# BeagleBone_Black_egl.net
KiCad netlist of a schematic drawn in EAGLE
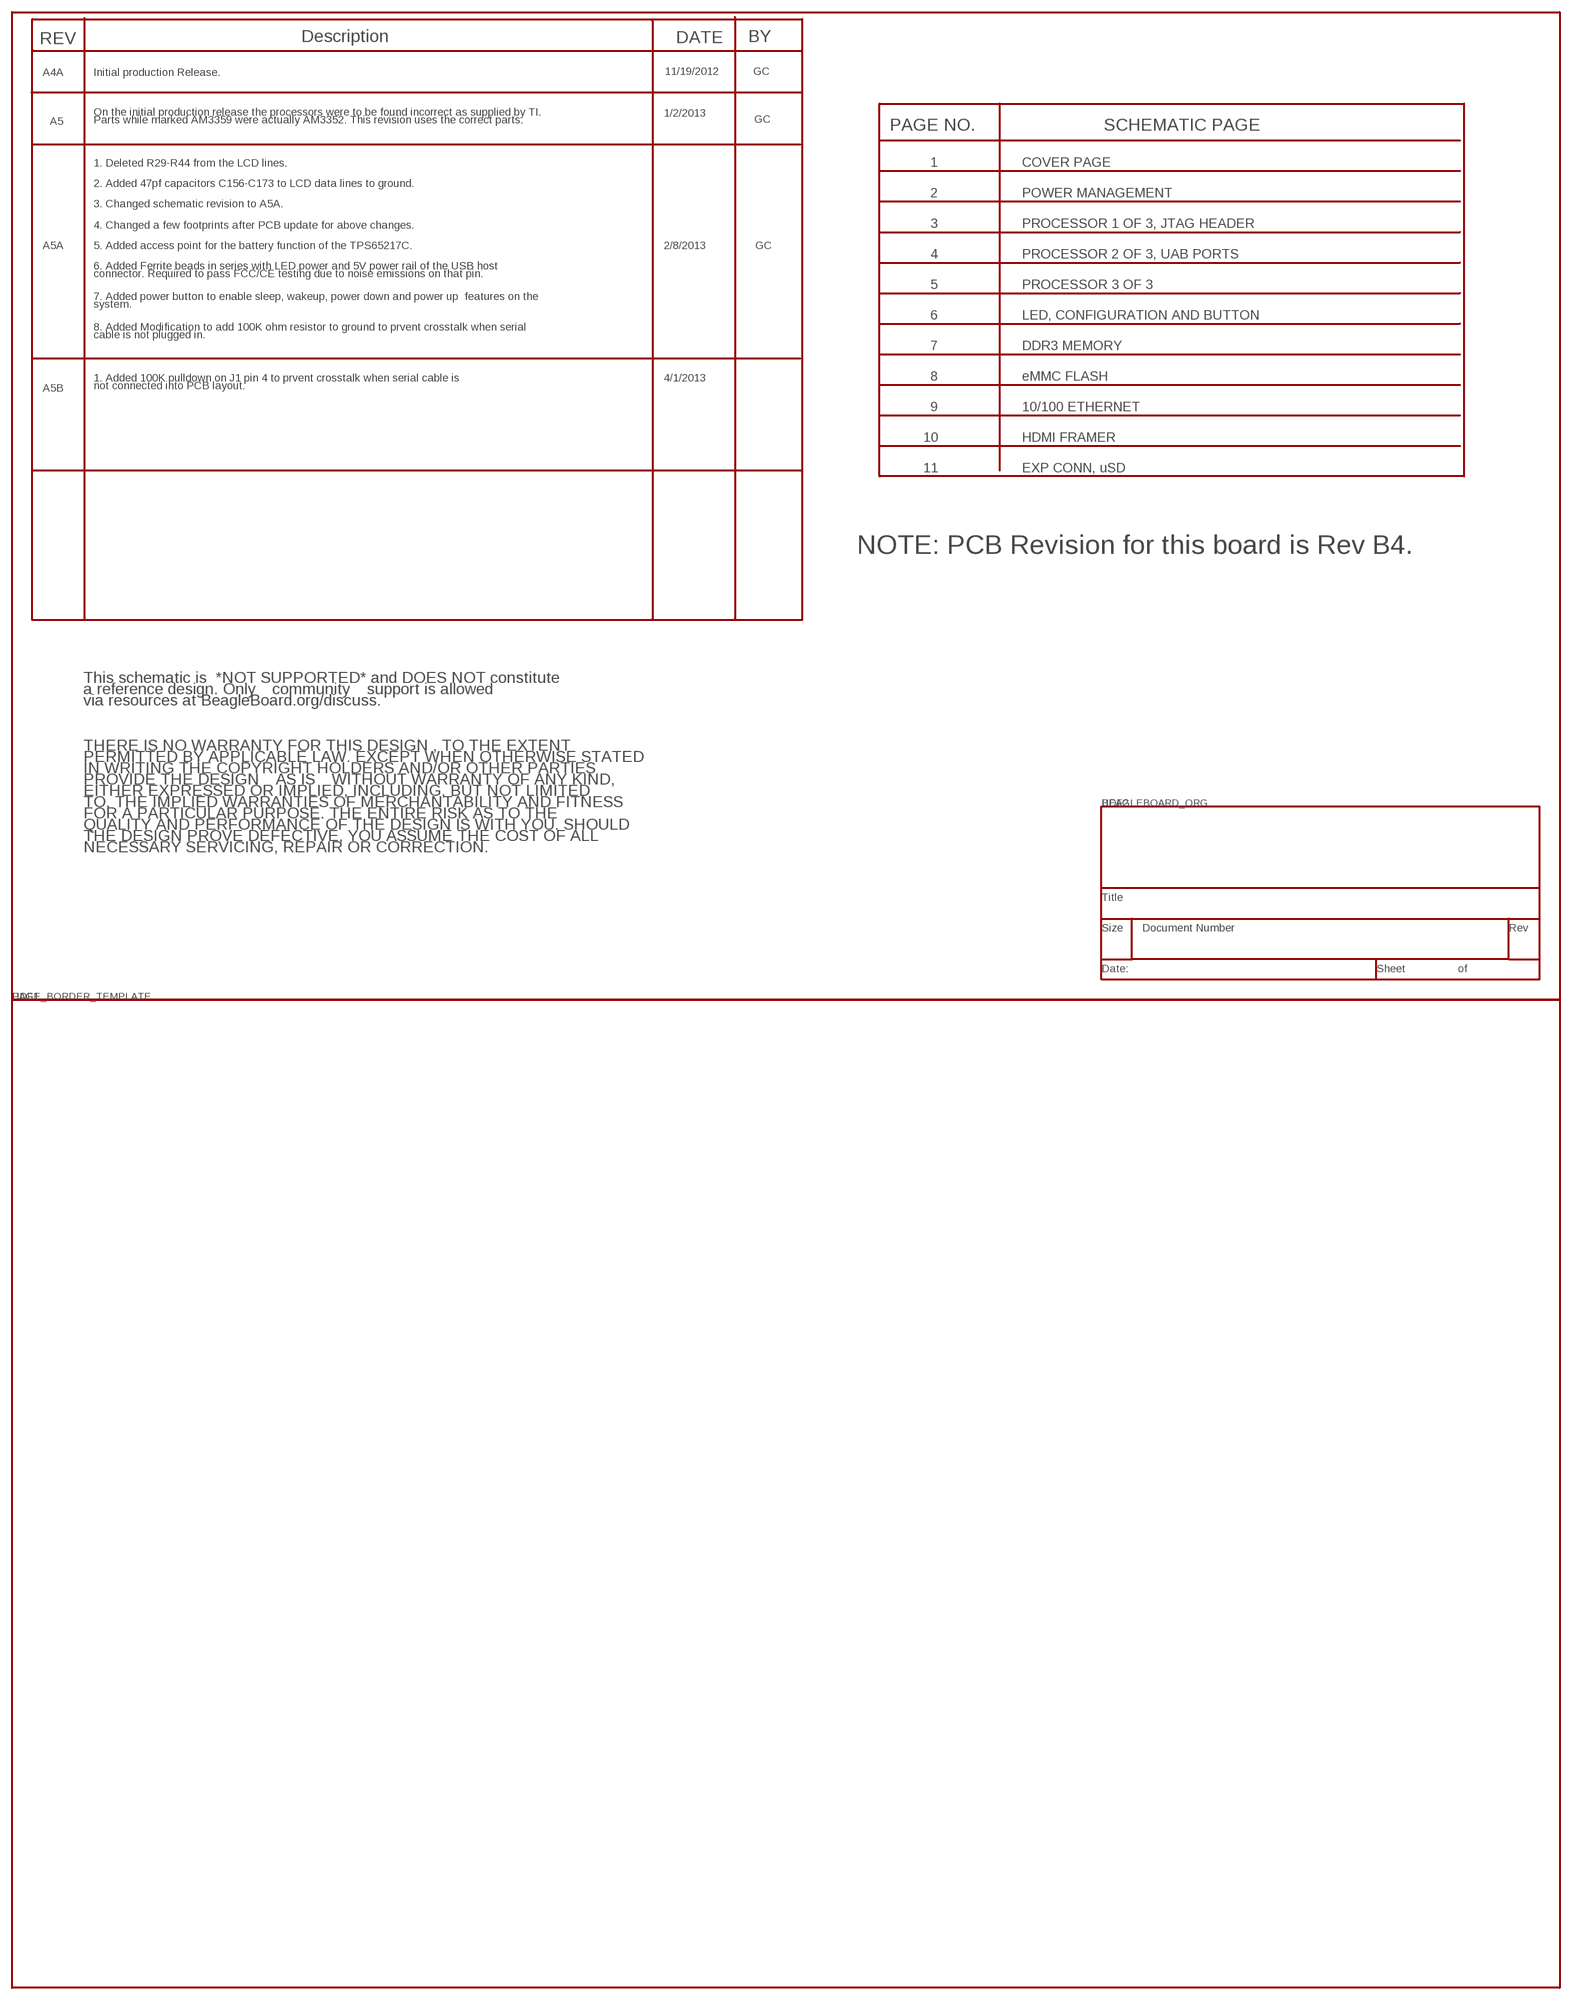
[diagram p0: schematic, sheet 1]
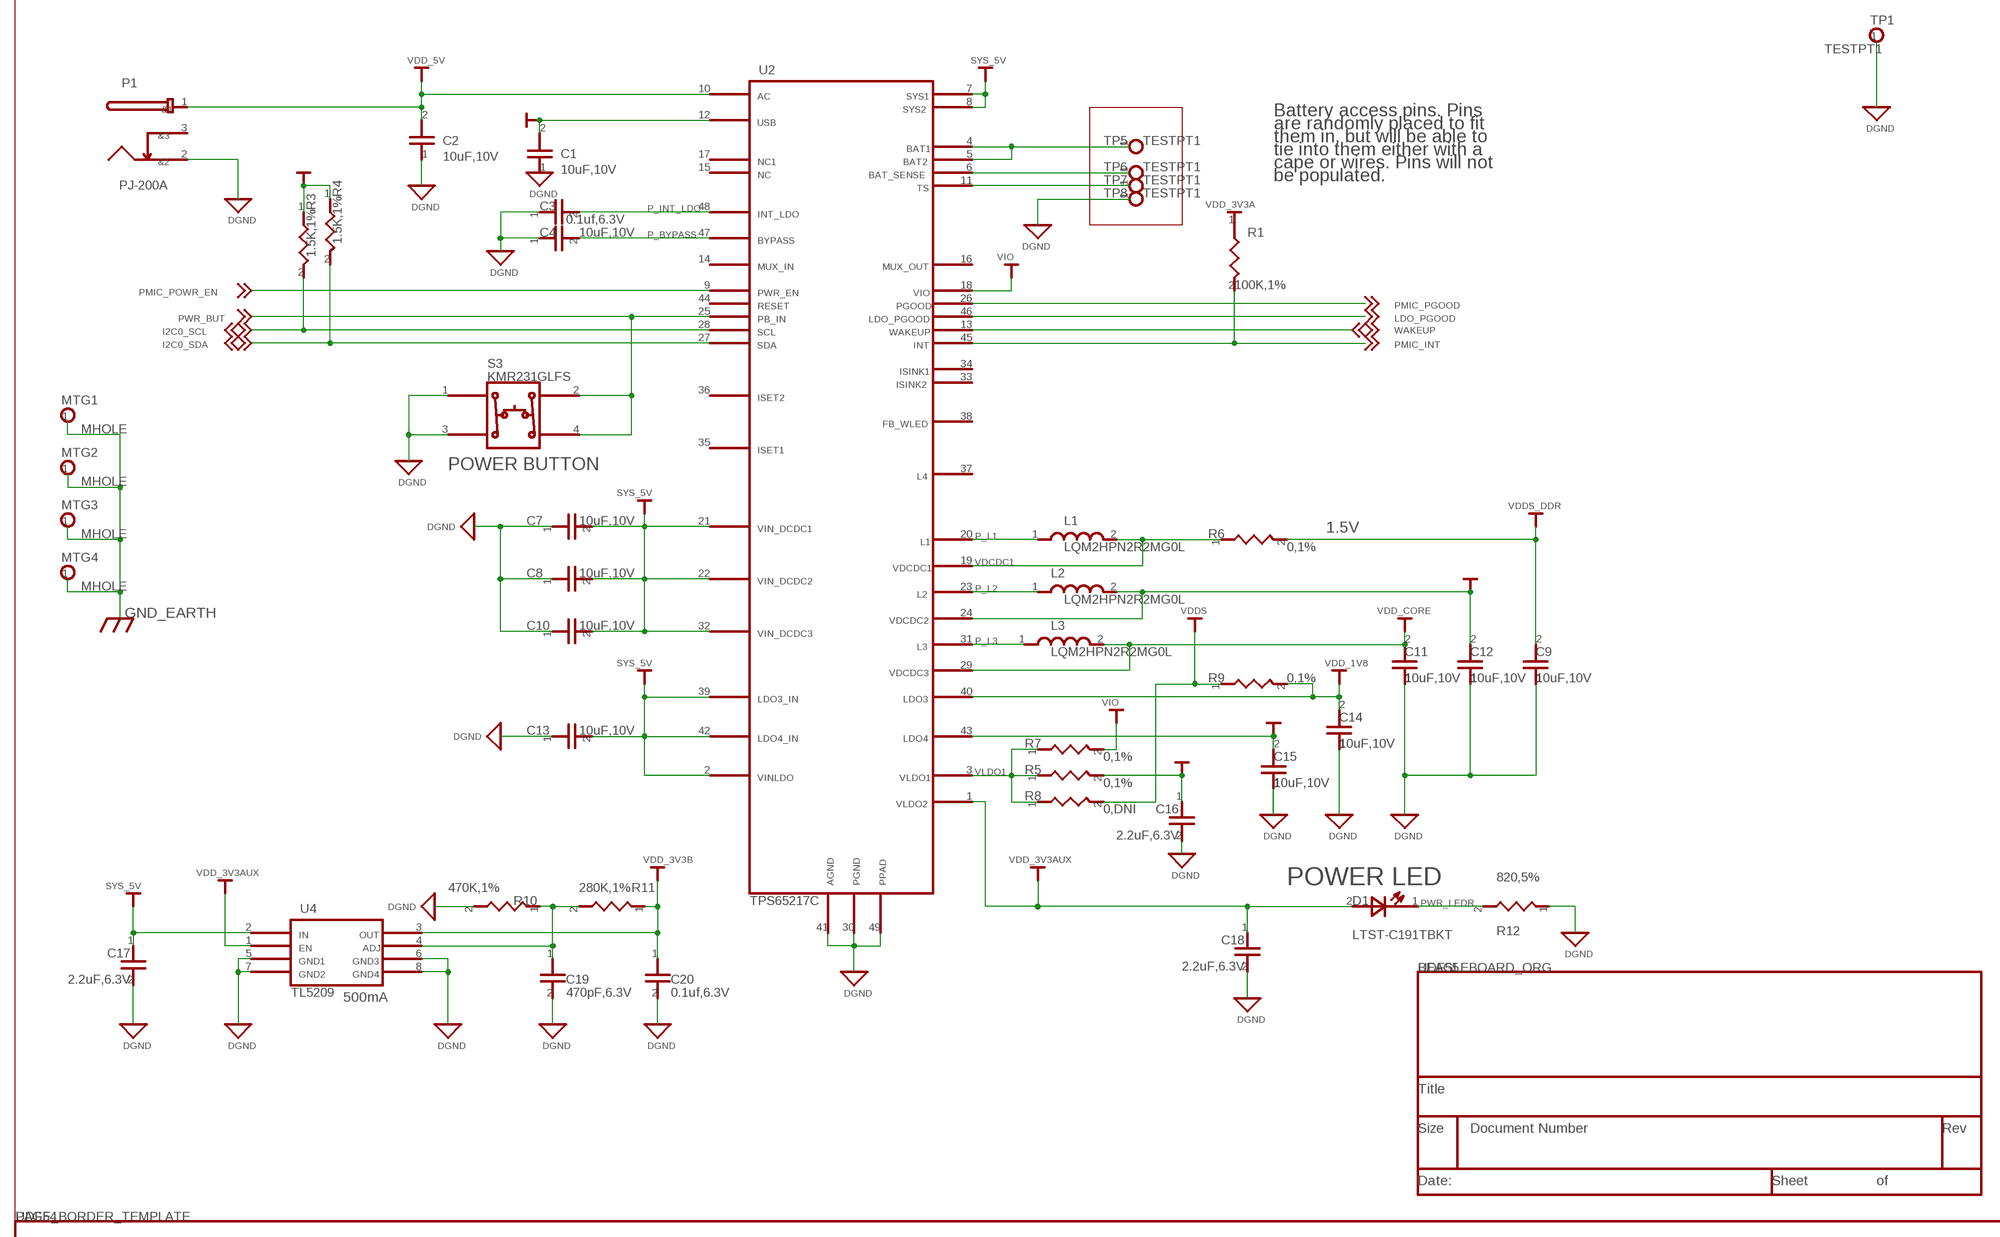
[diagram p1: schematic, sheet 2]
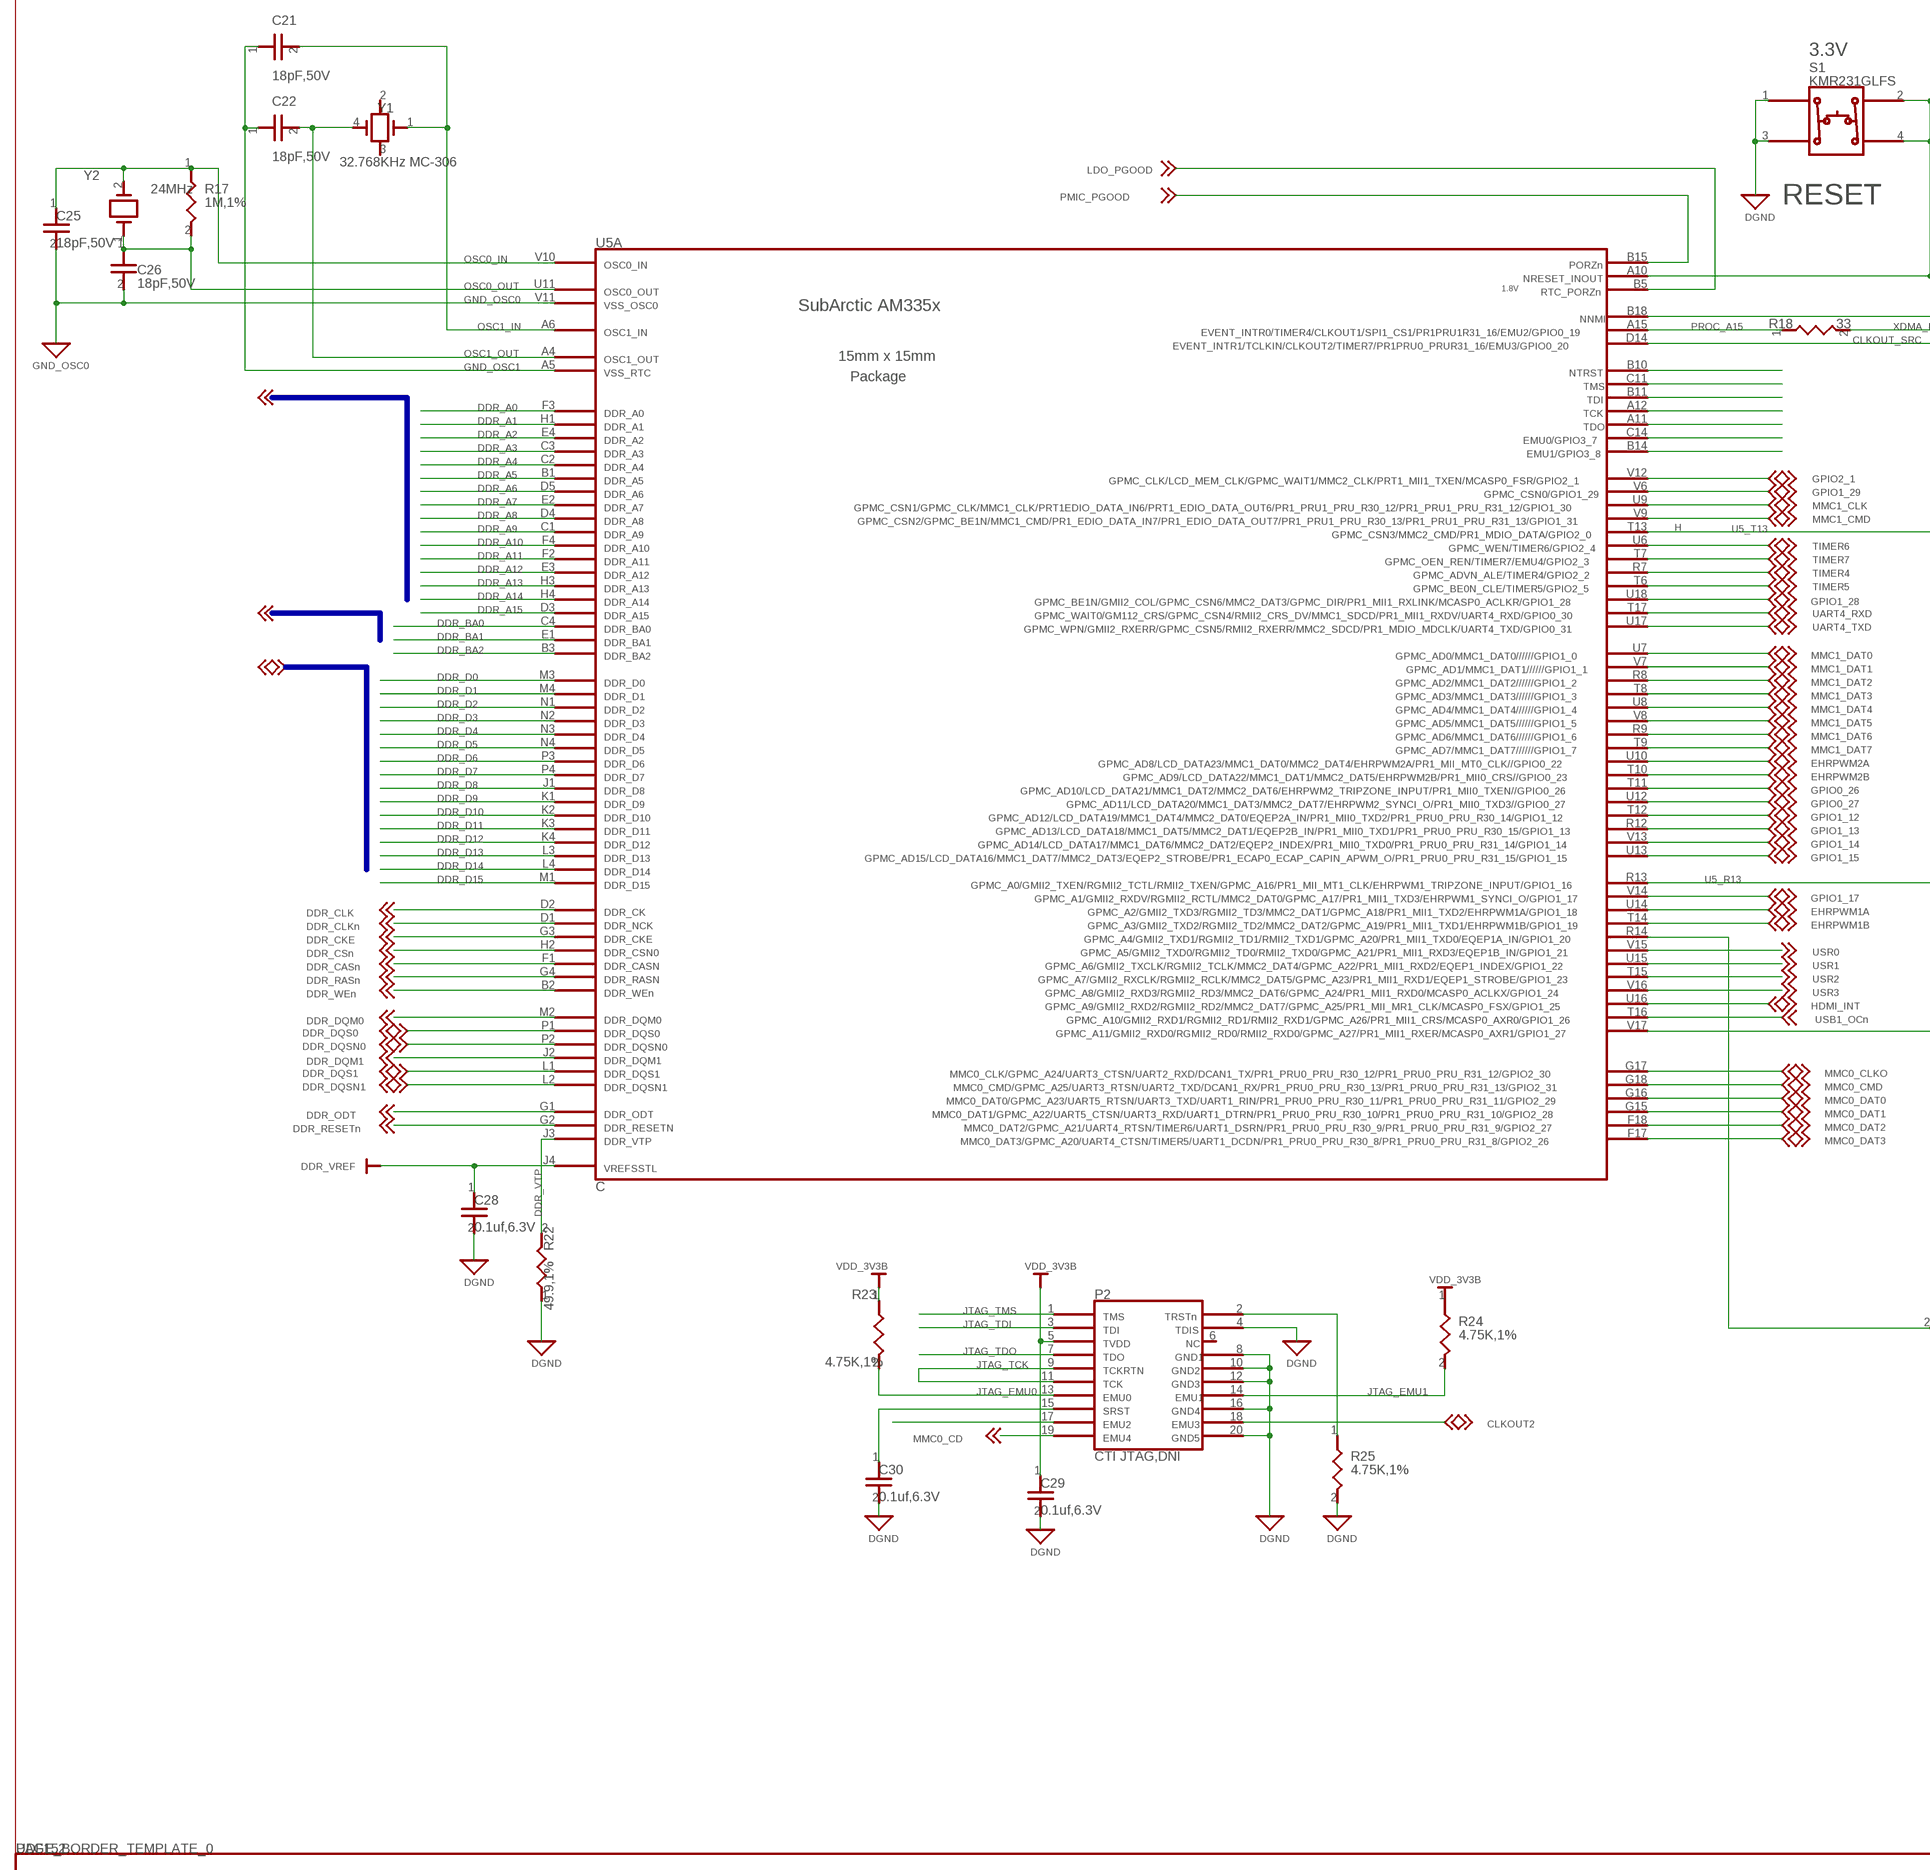
[diagram p2: schematic, sheet 3, part 1 of 2]
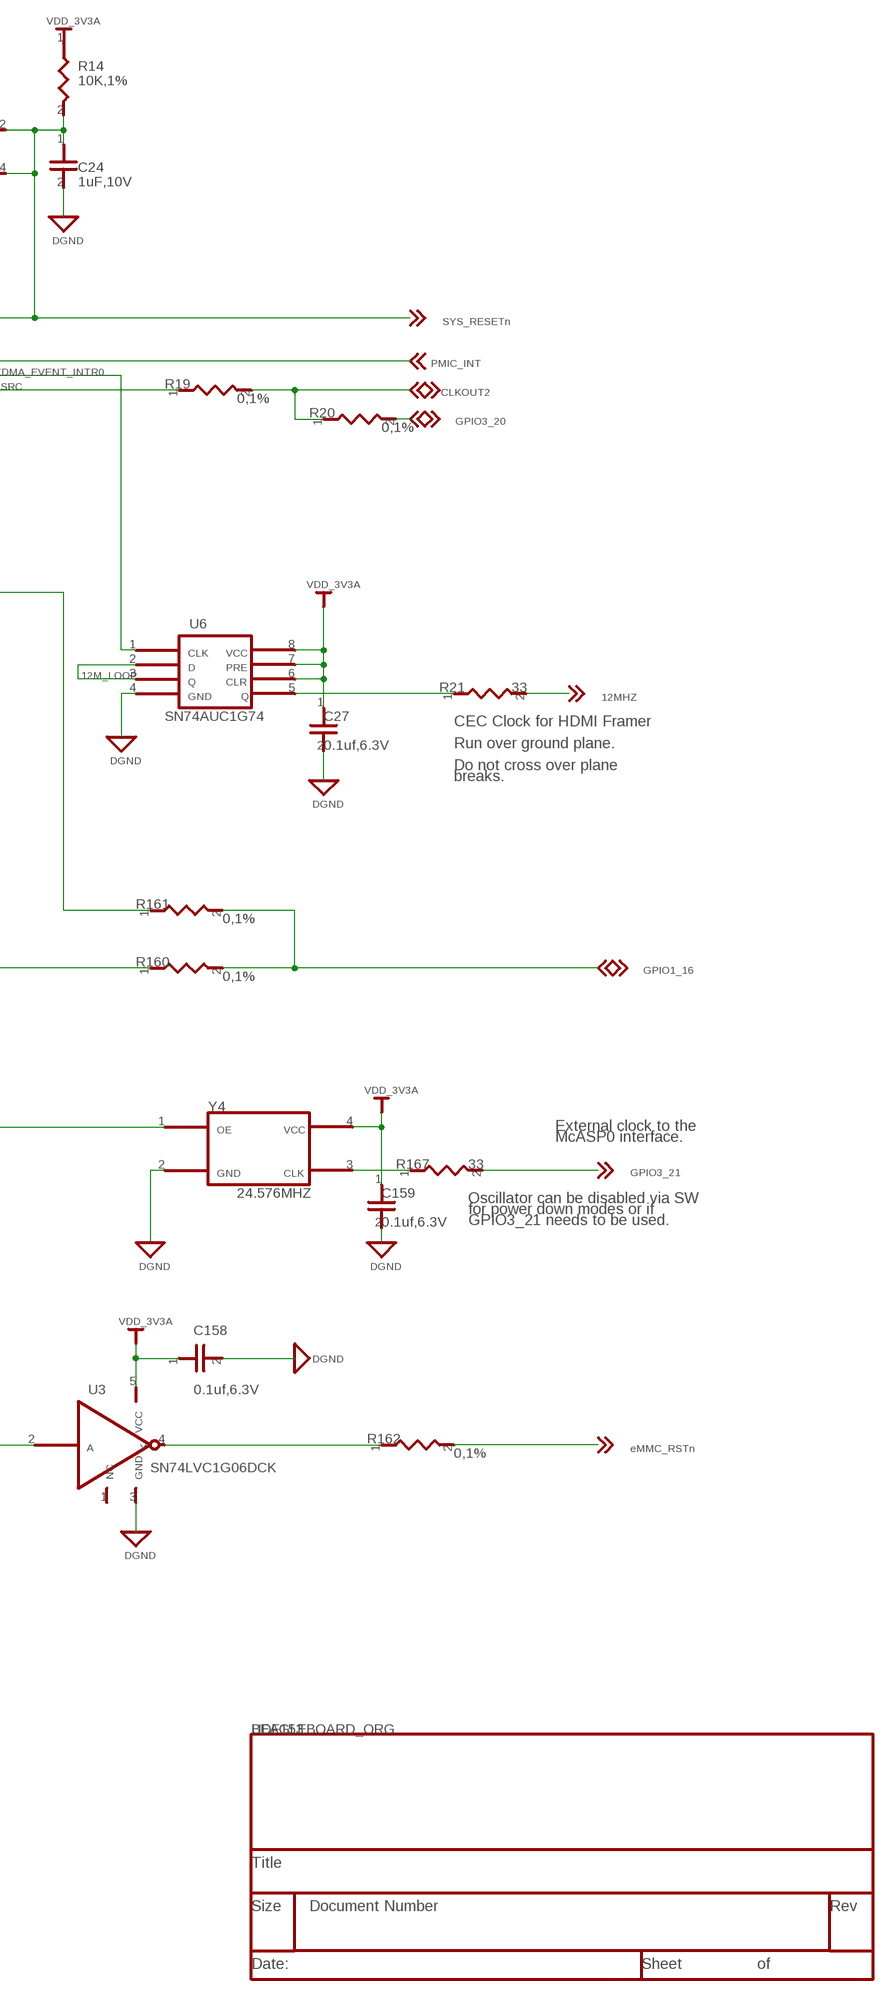
[diagram p3: schematic, sheet 3, part 2 of 2]
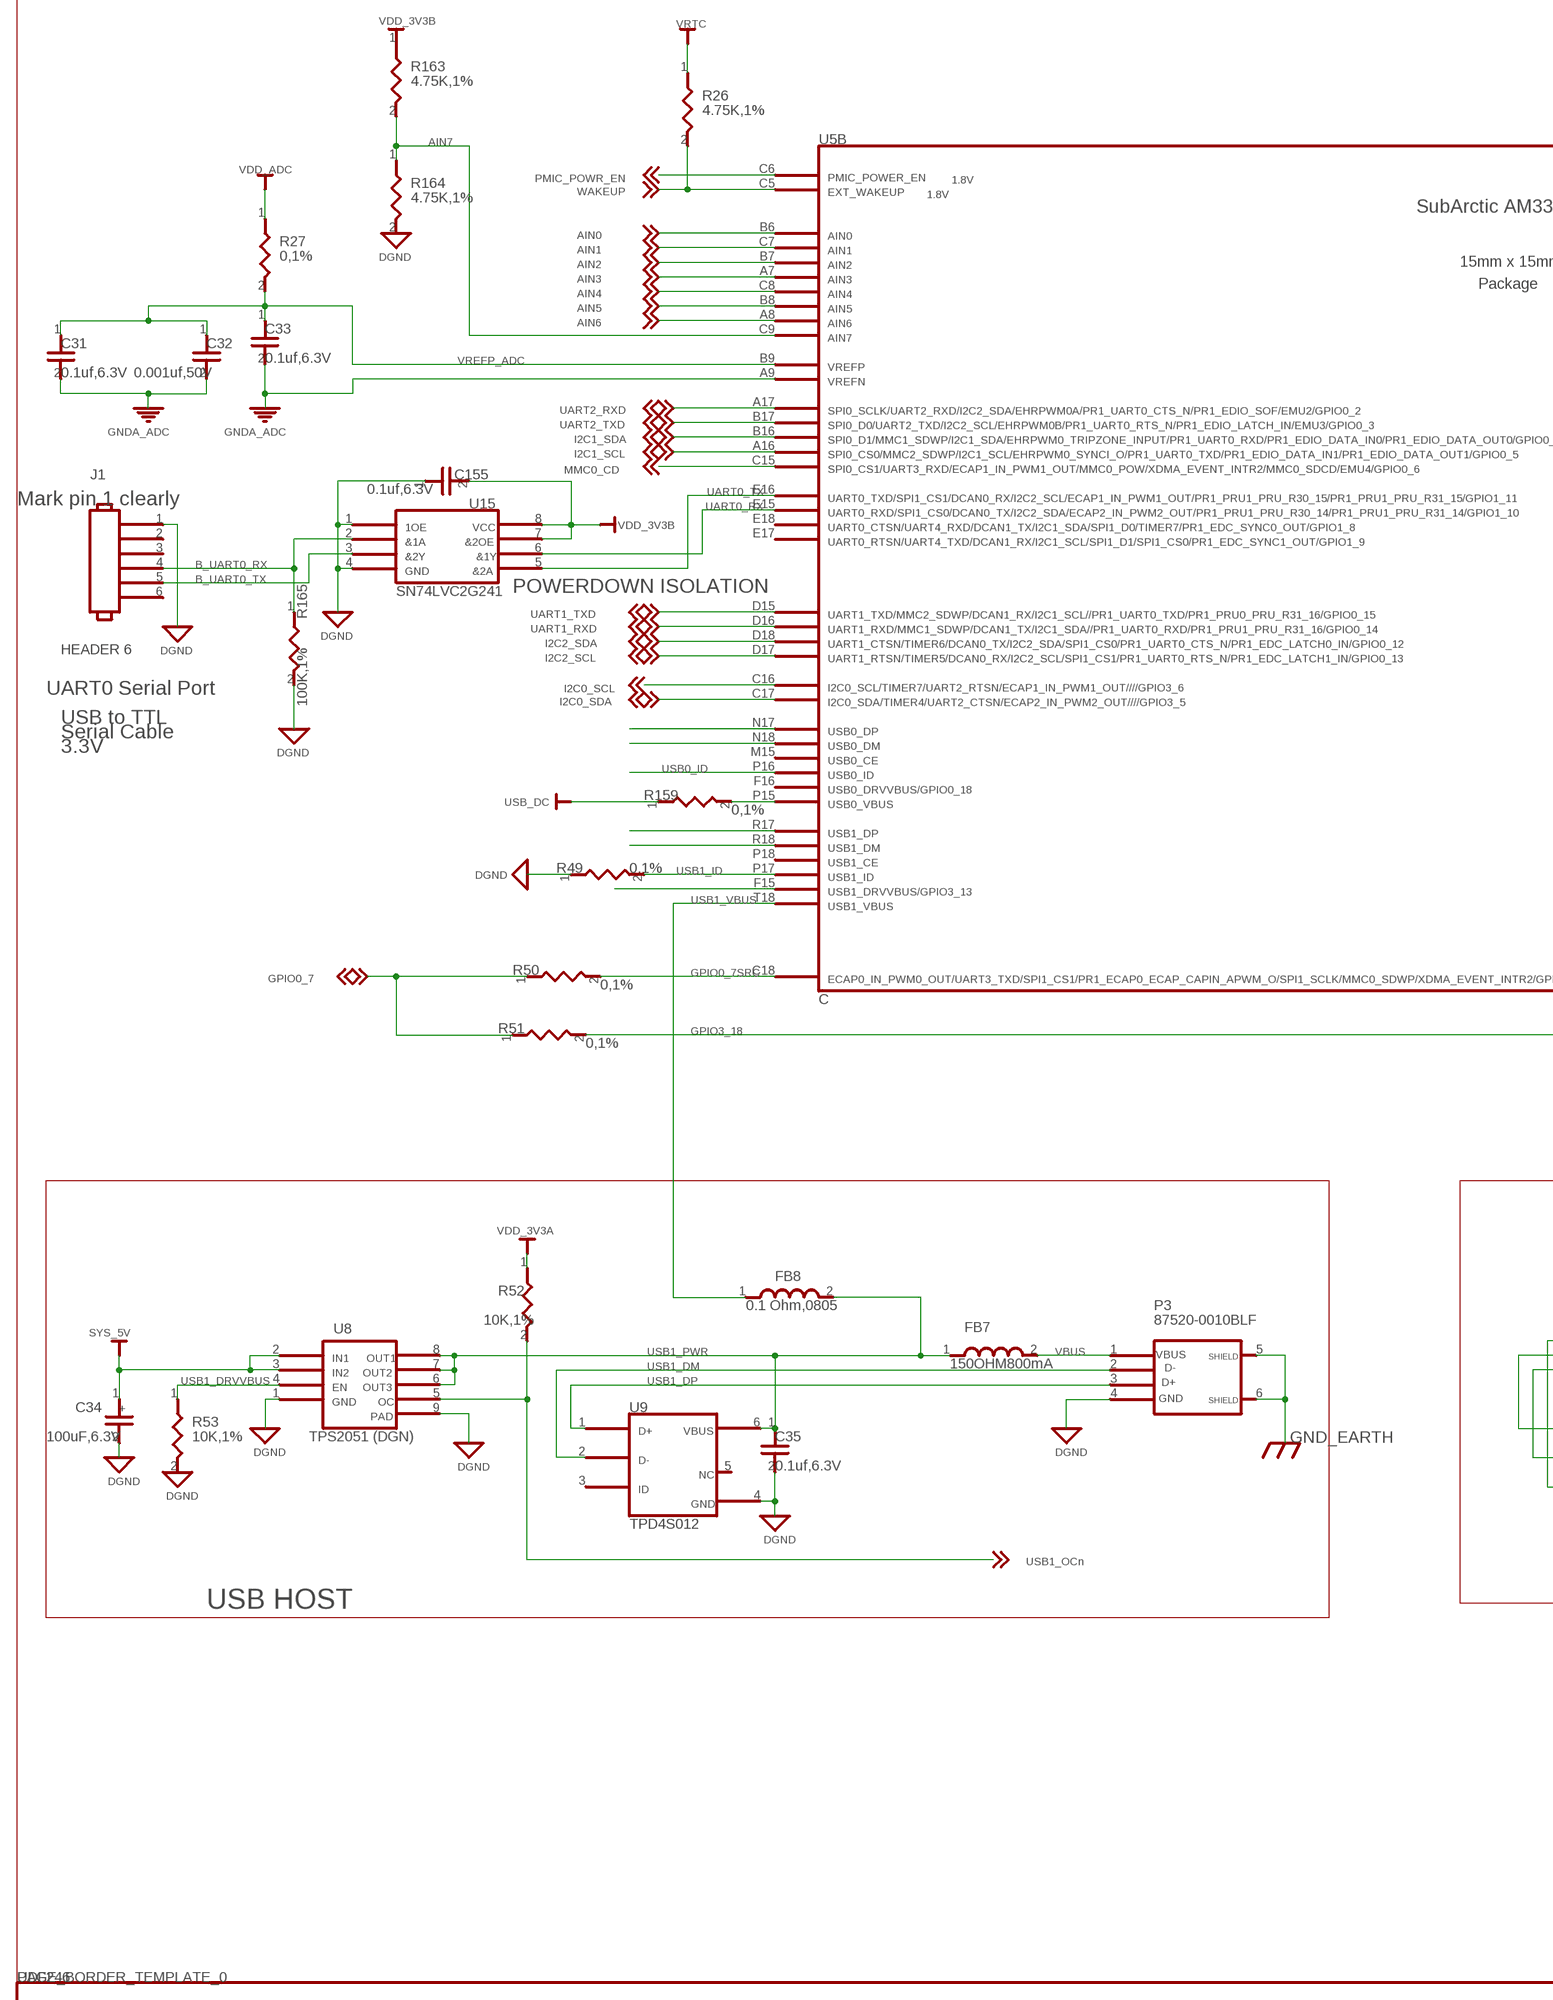
[diagram p4: schematic, sheet 4, part 1 of 2]
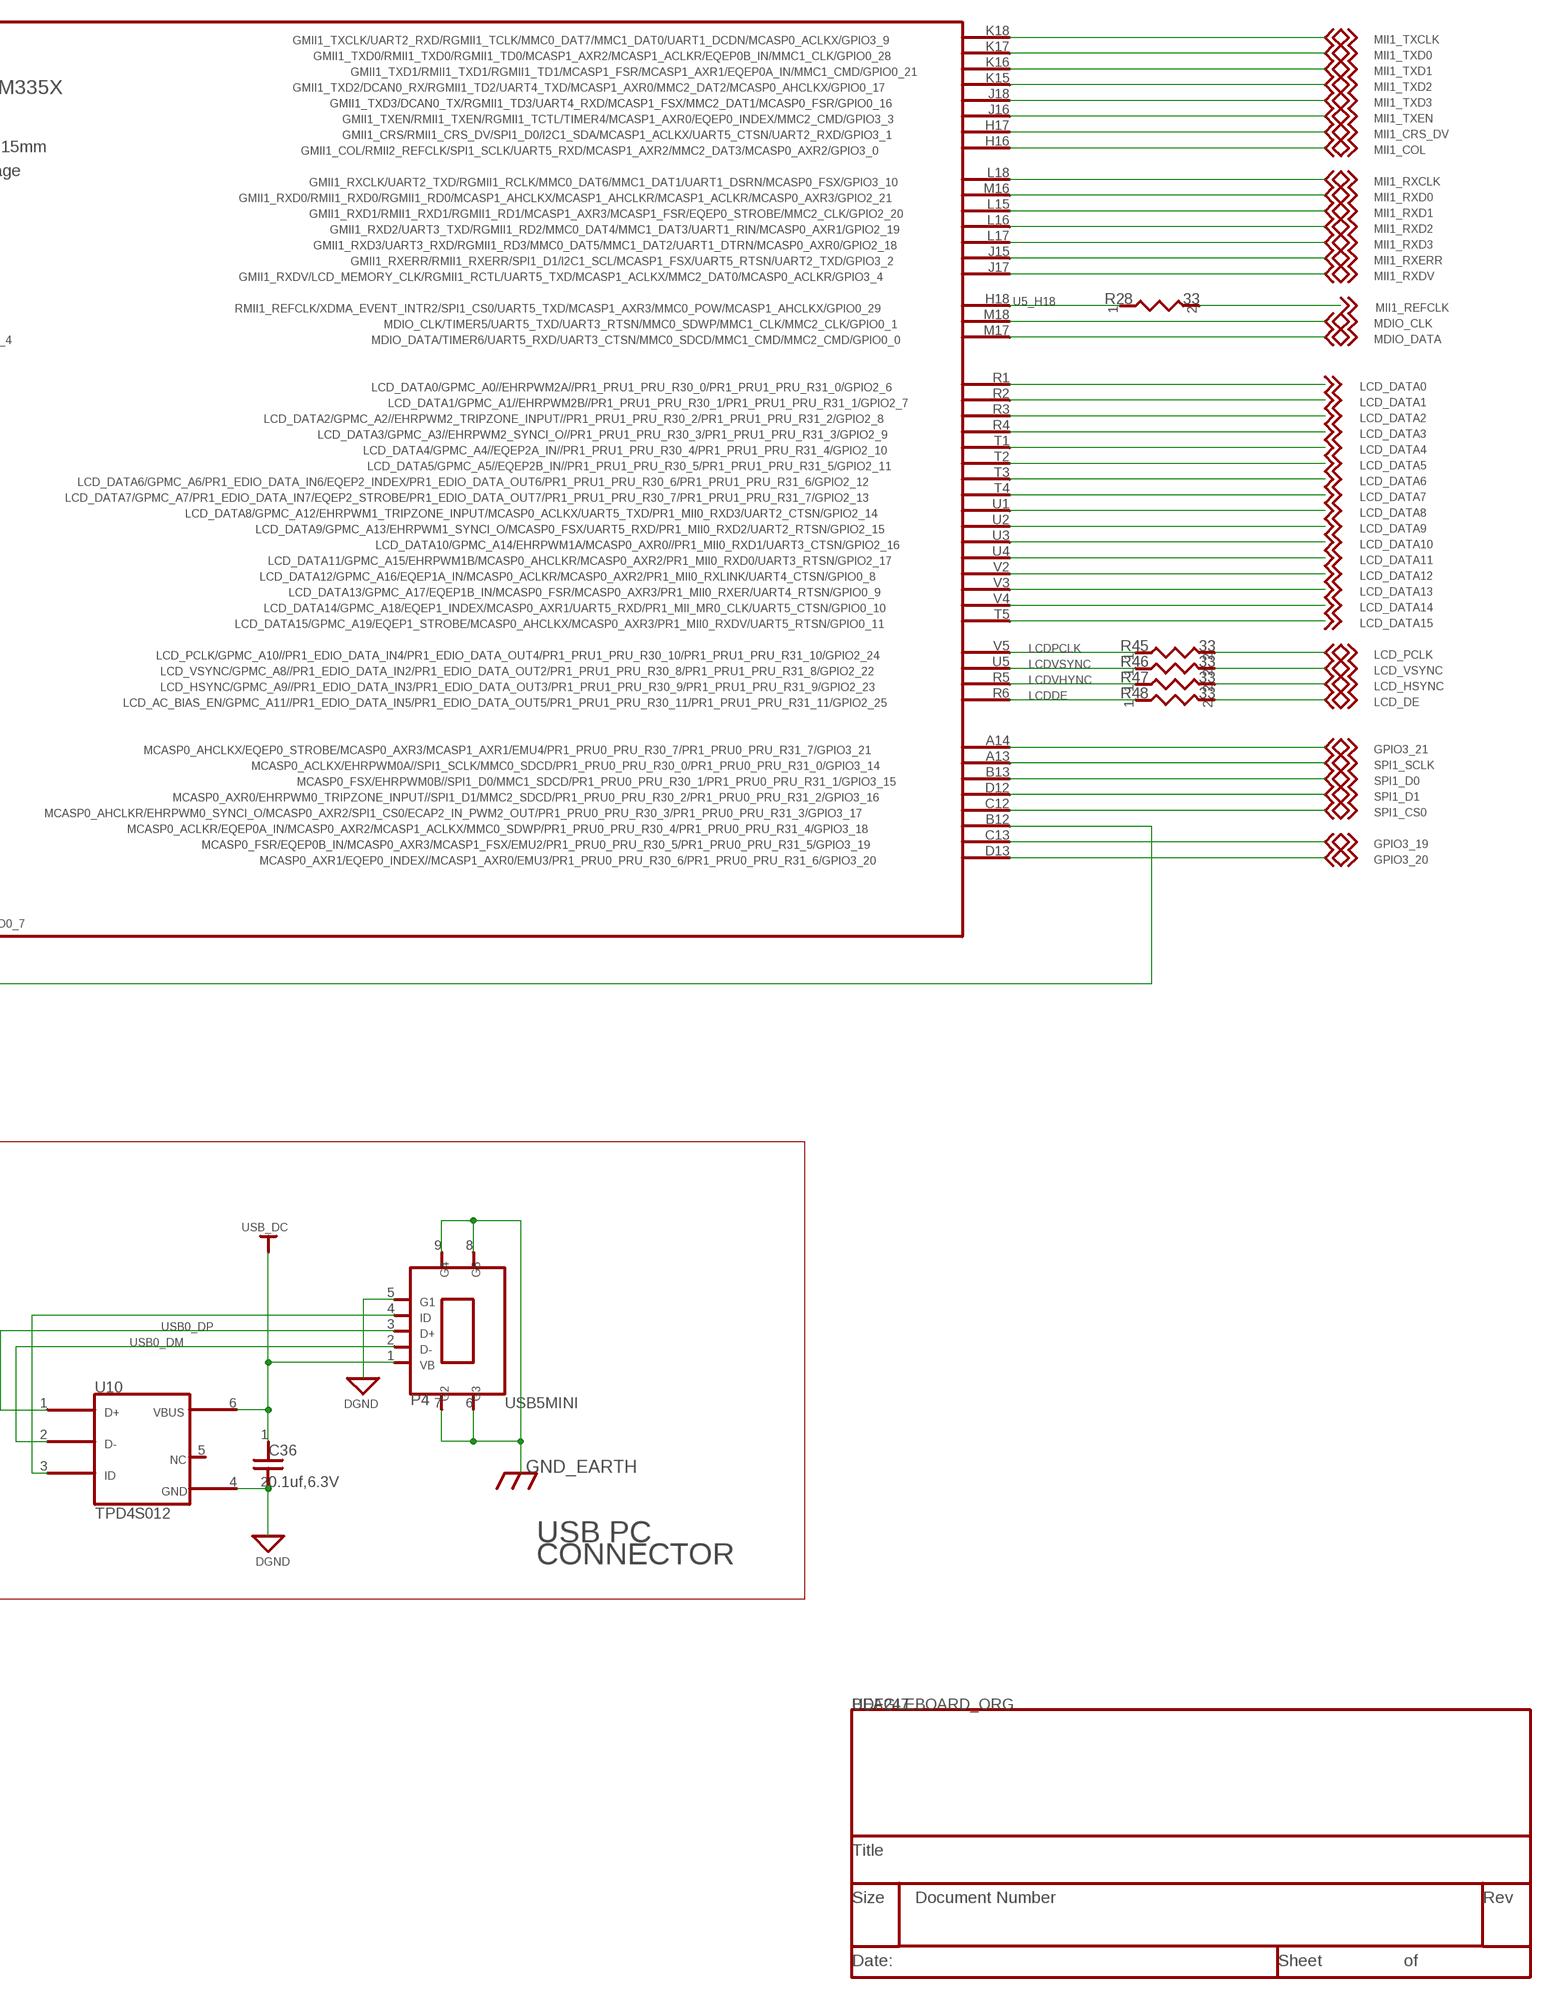
[diagram p5: schematic, sheet 4, part 2 of 2]
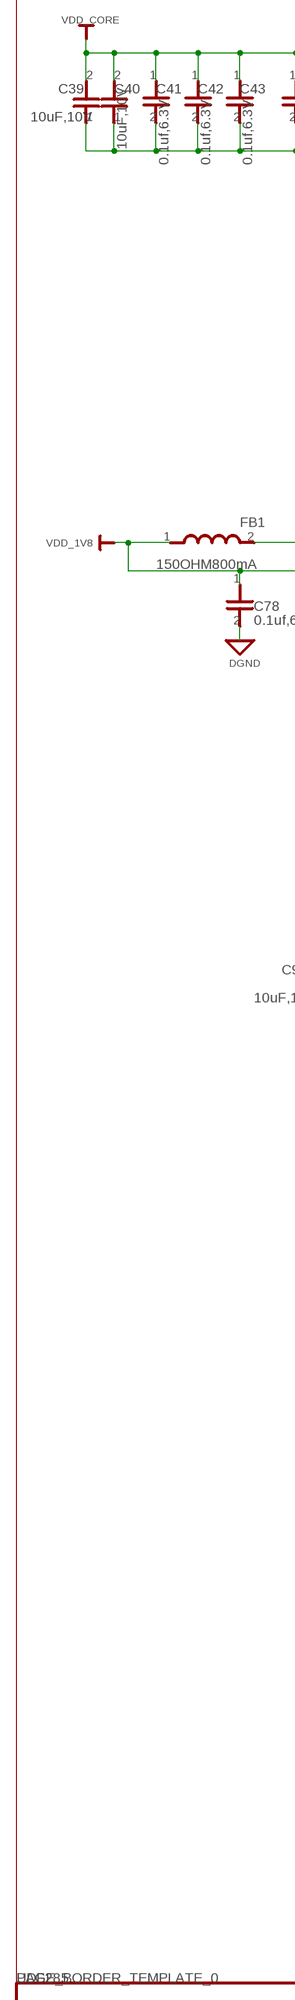
[diagram p6: schematic, sheet 5, part 1 of 2]
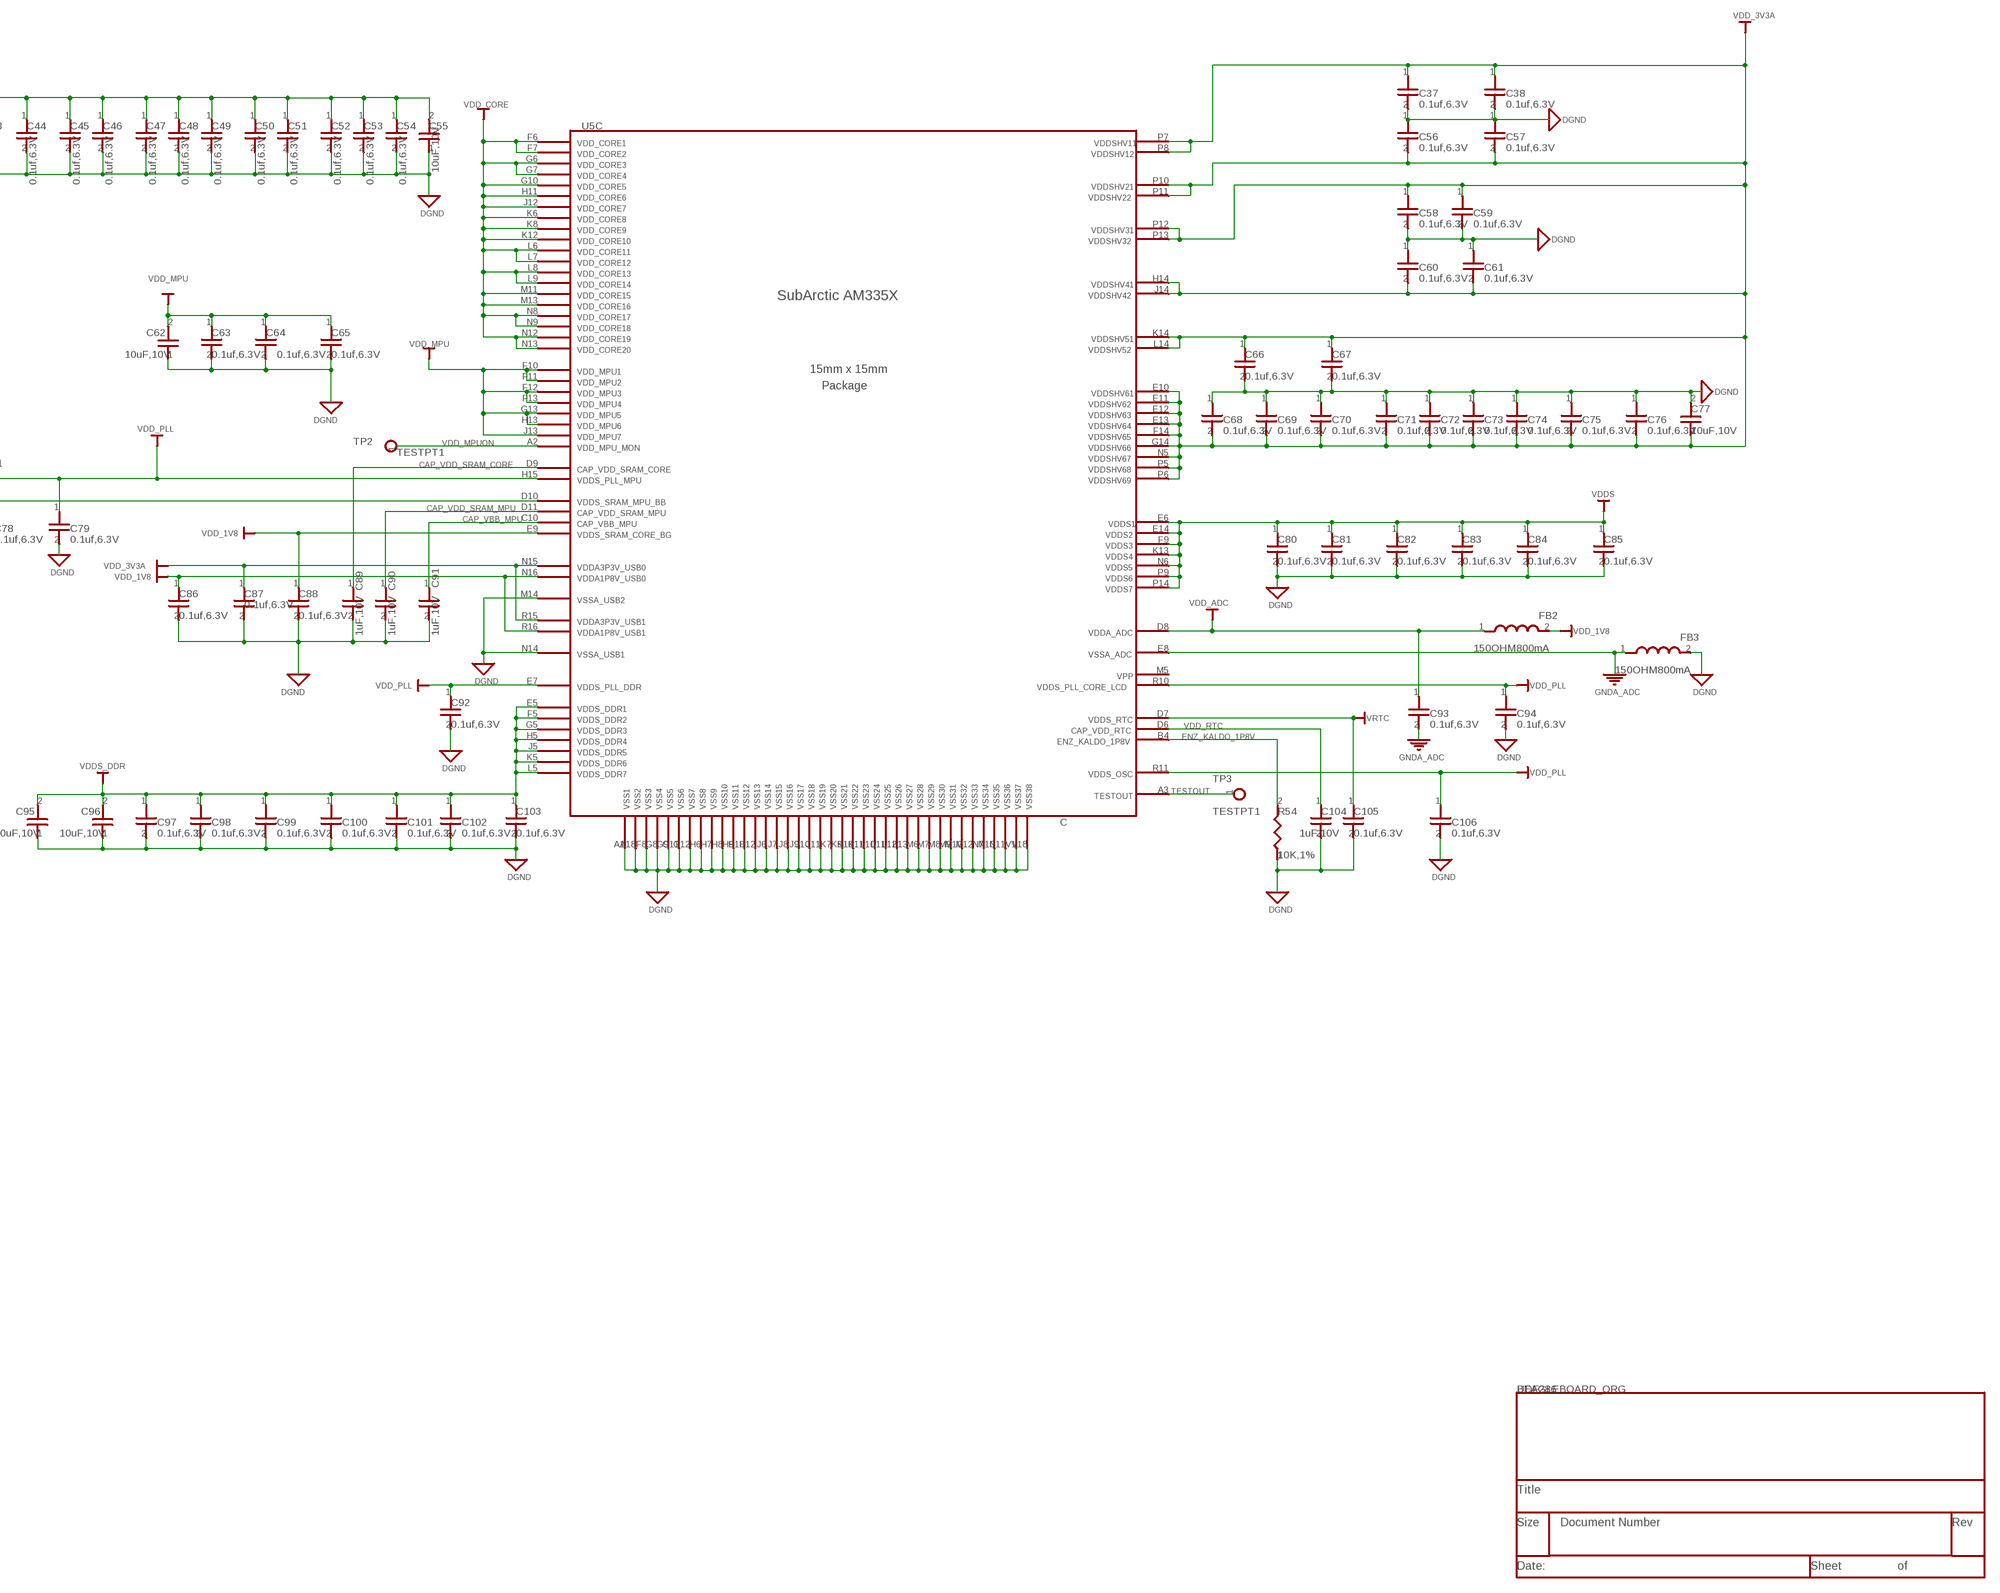
[diagram p7: schematic, sheet 5, part 2 of 2]
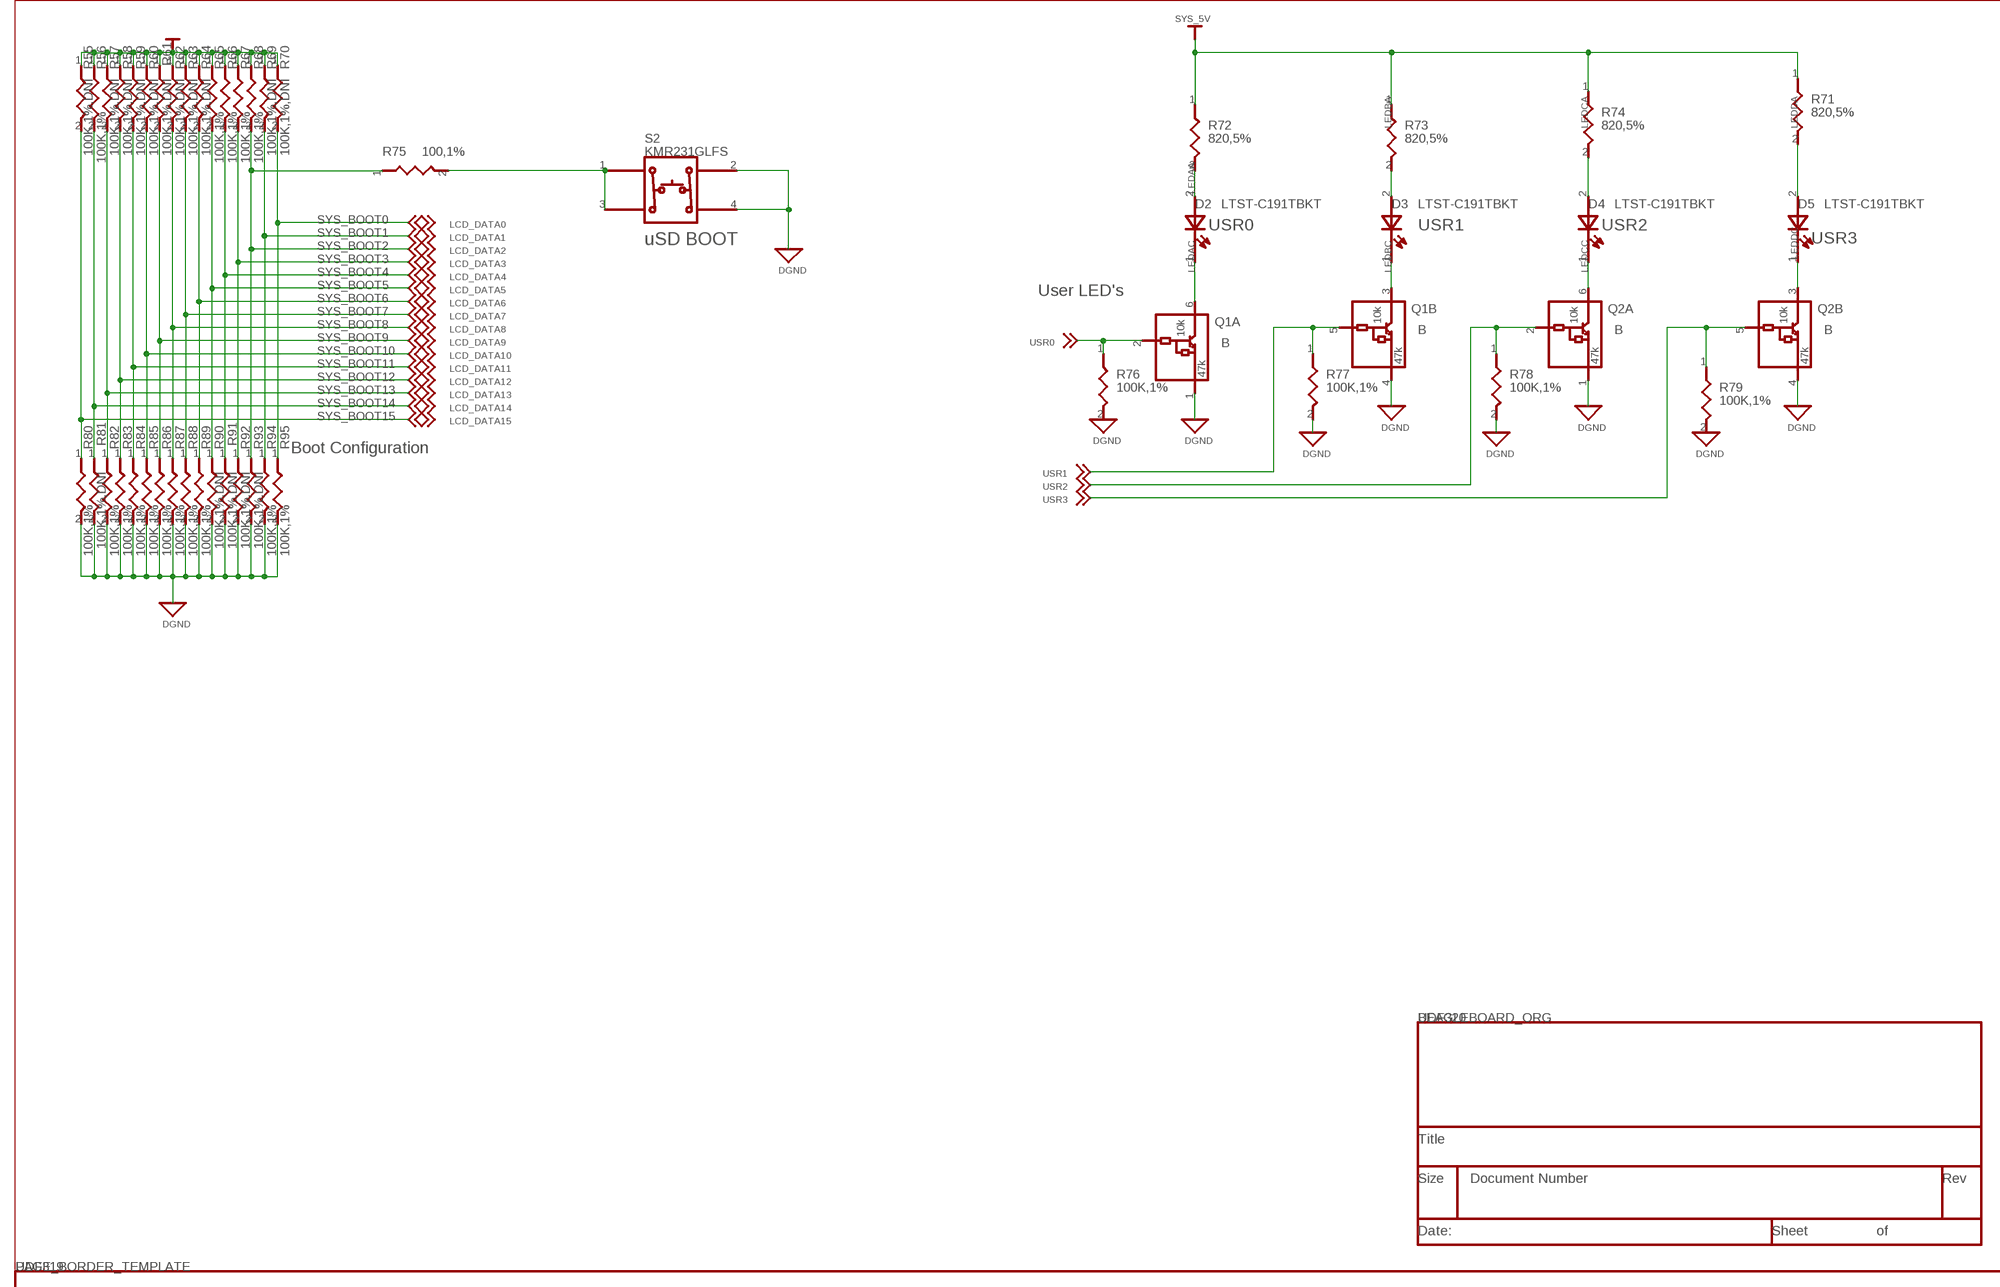
[diagram p8: schematic, sheet 6]
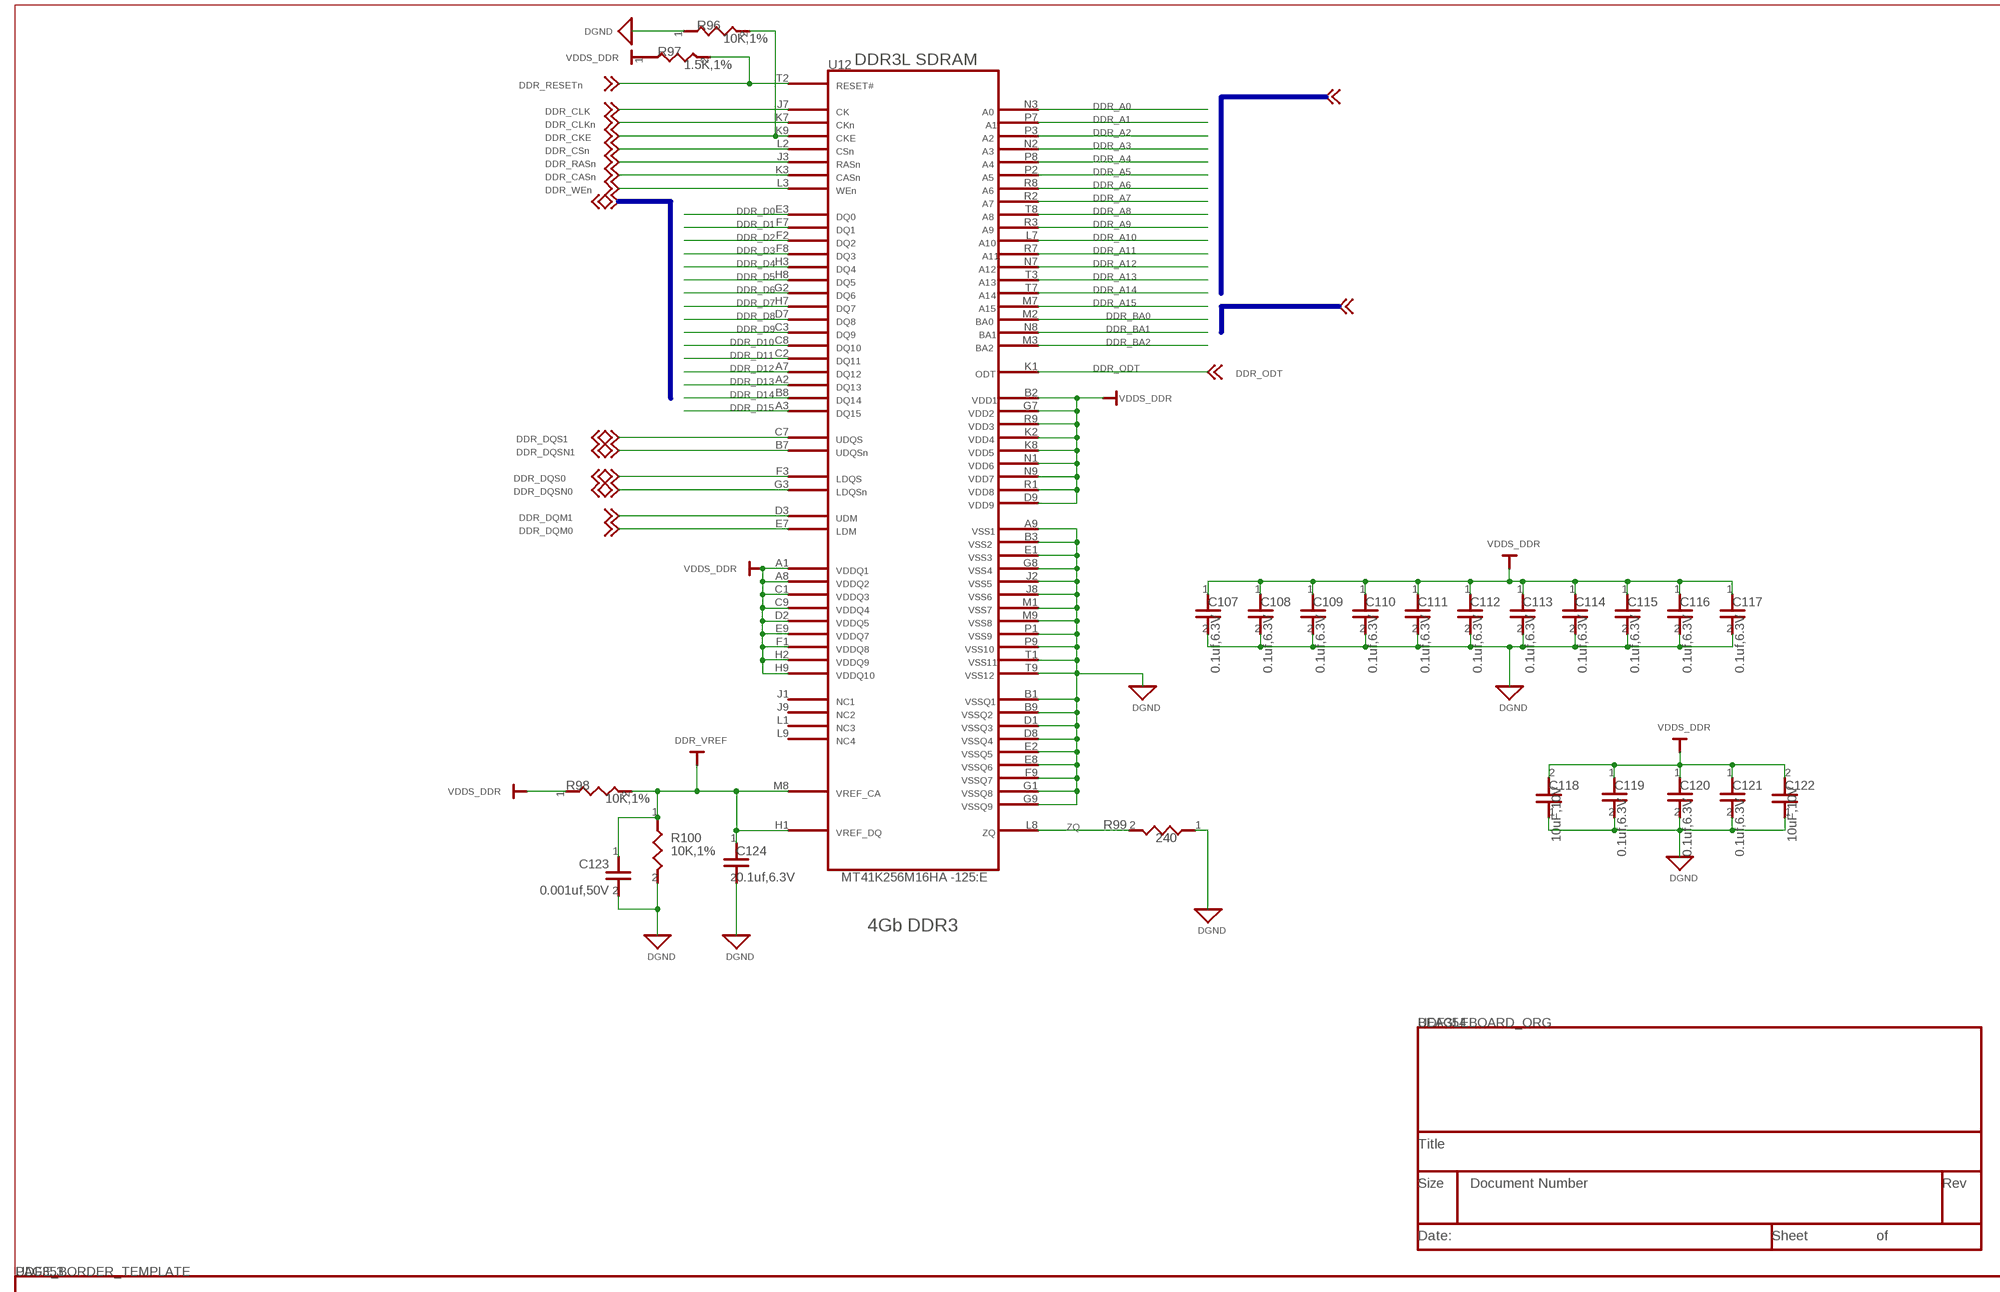
[diagram p9: schematic, sheet 7]
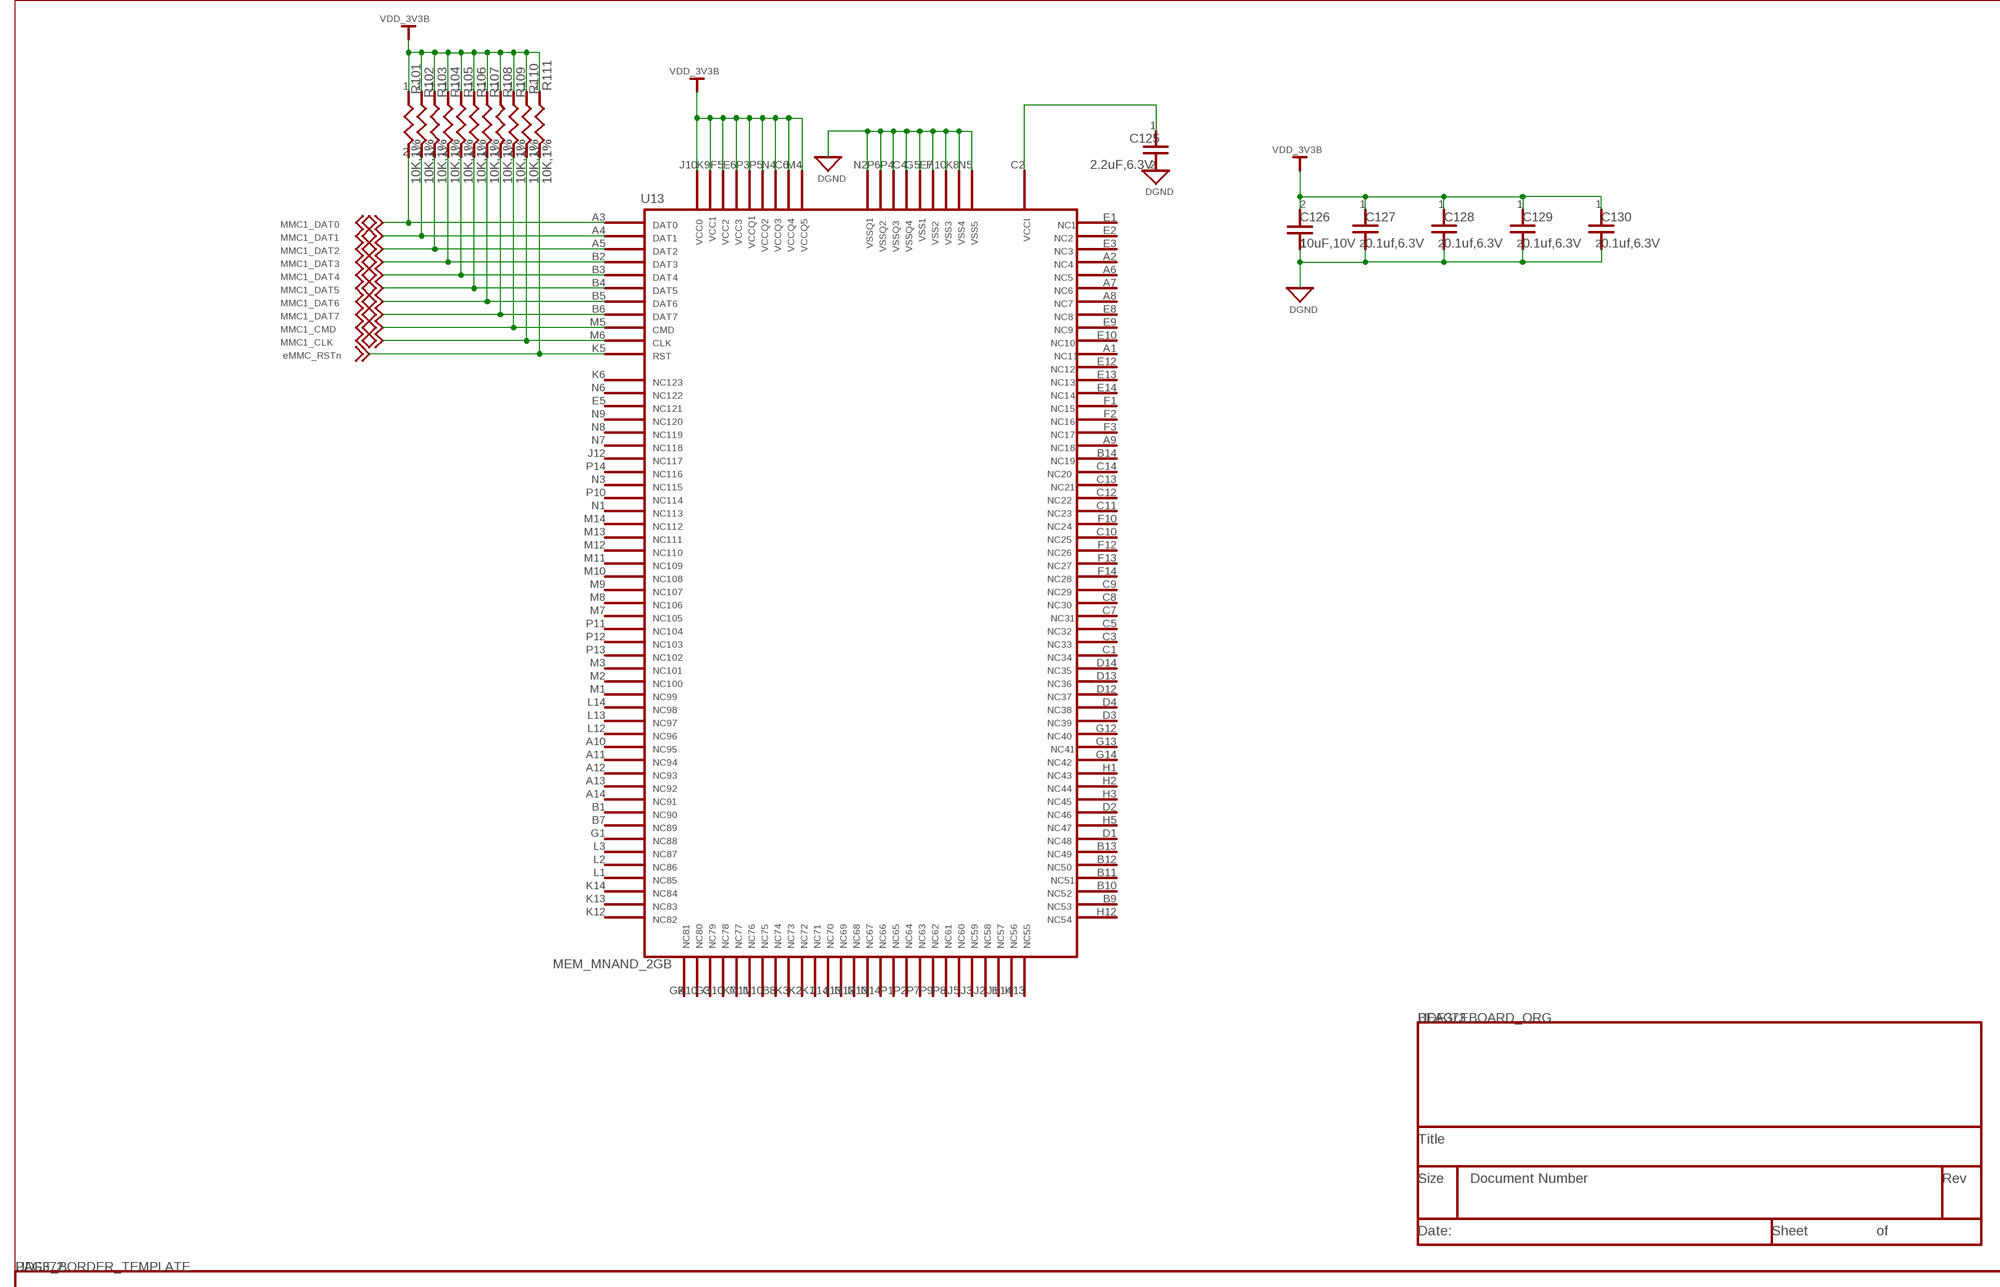
[diagram p10: schematic, sheet 8]
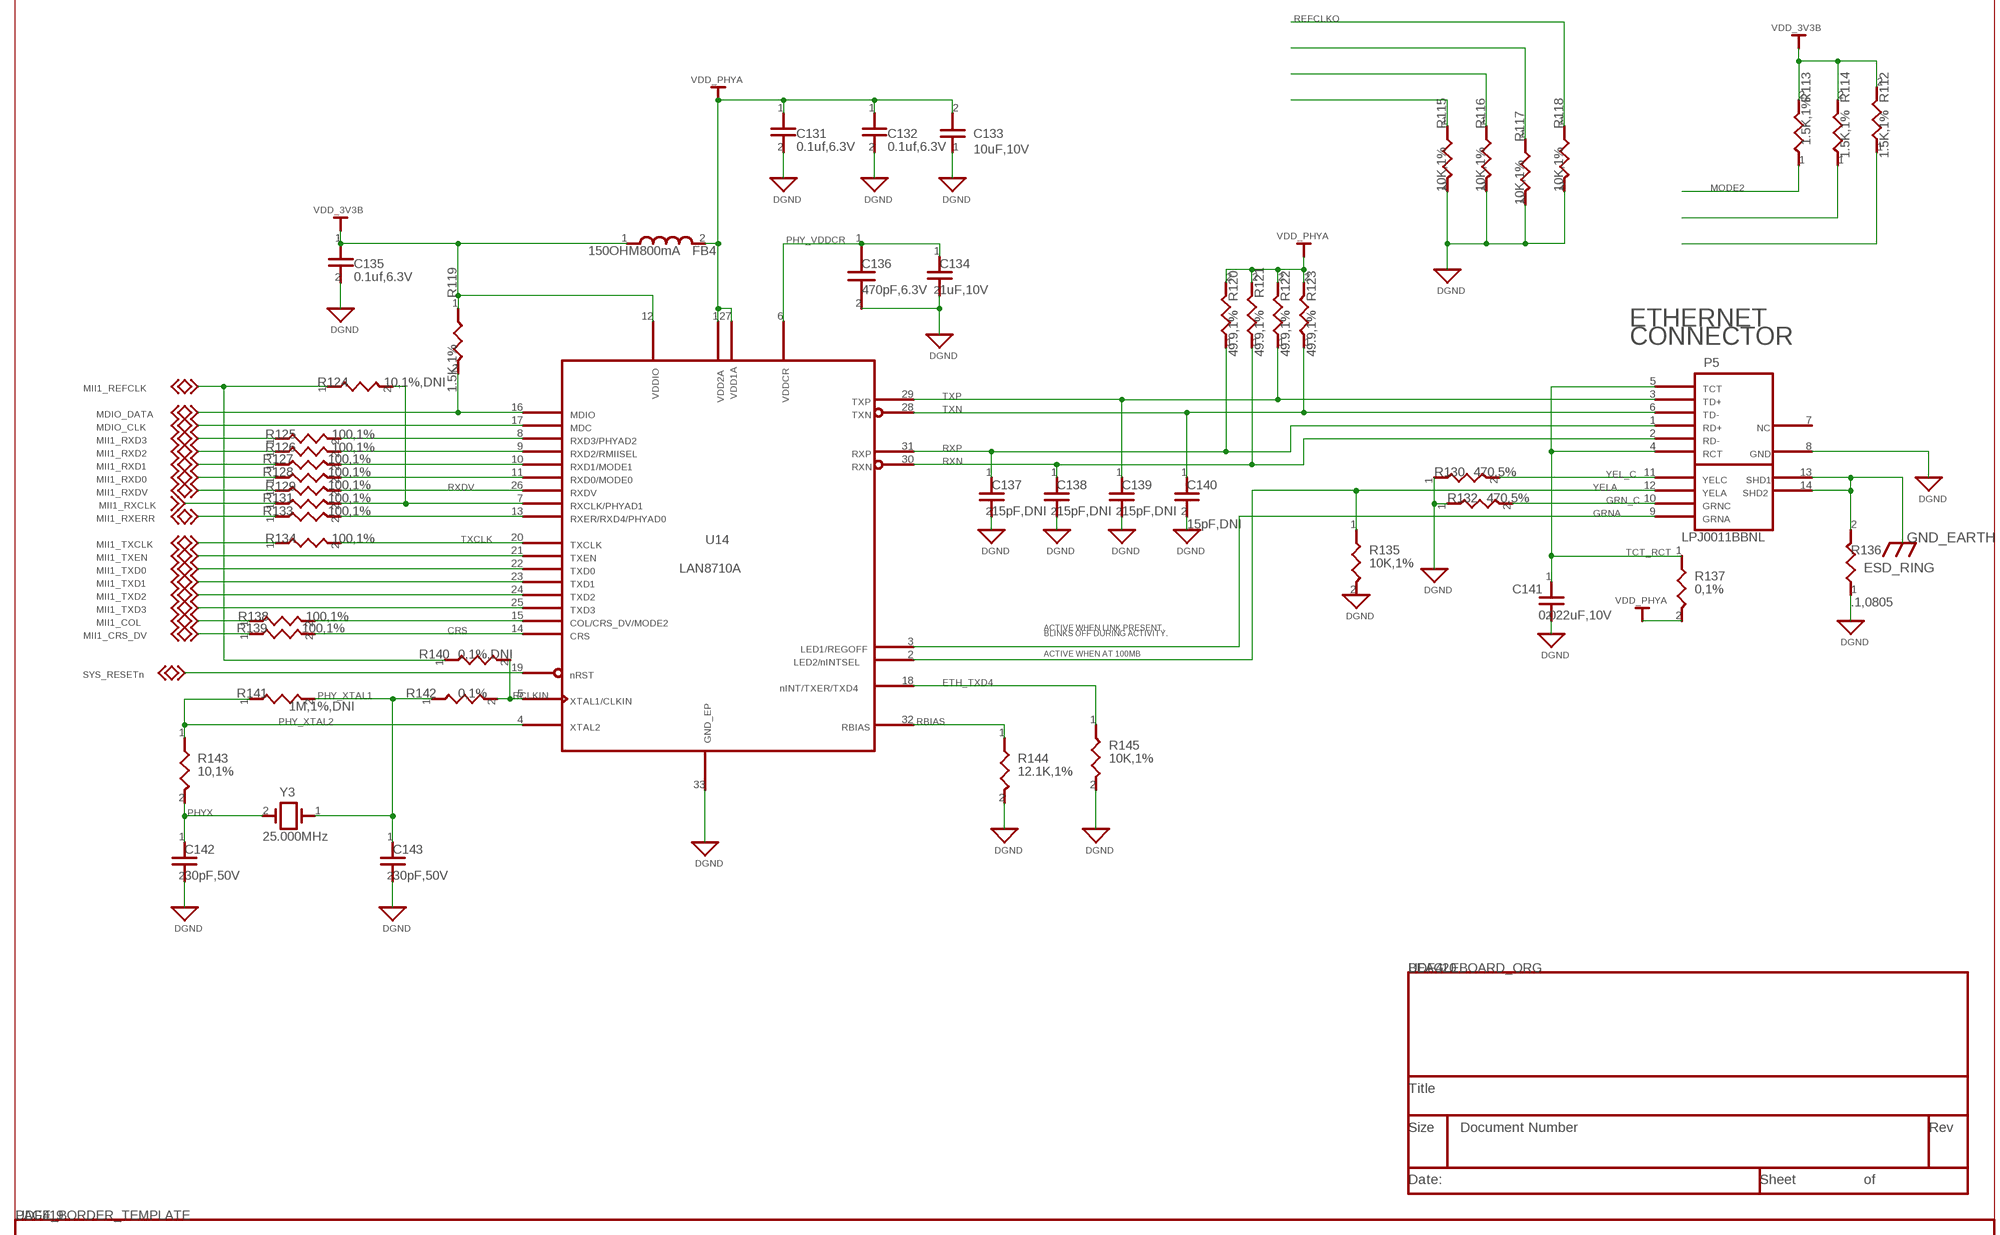
[diagram p11: schematic, sheet 9]
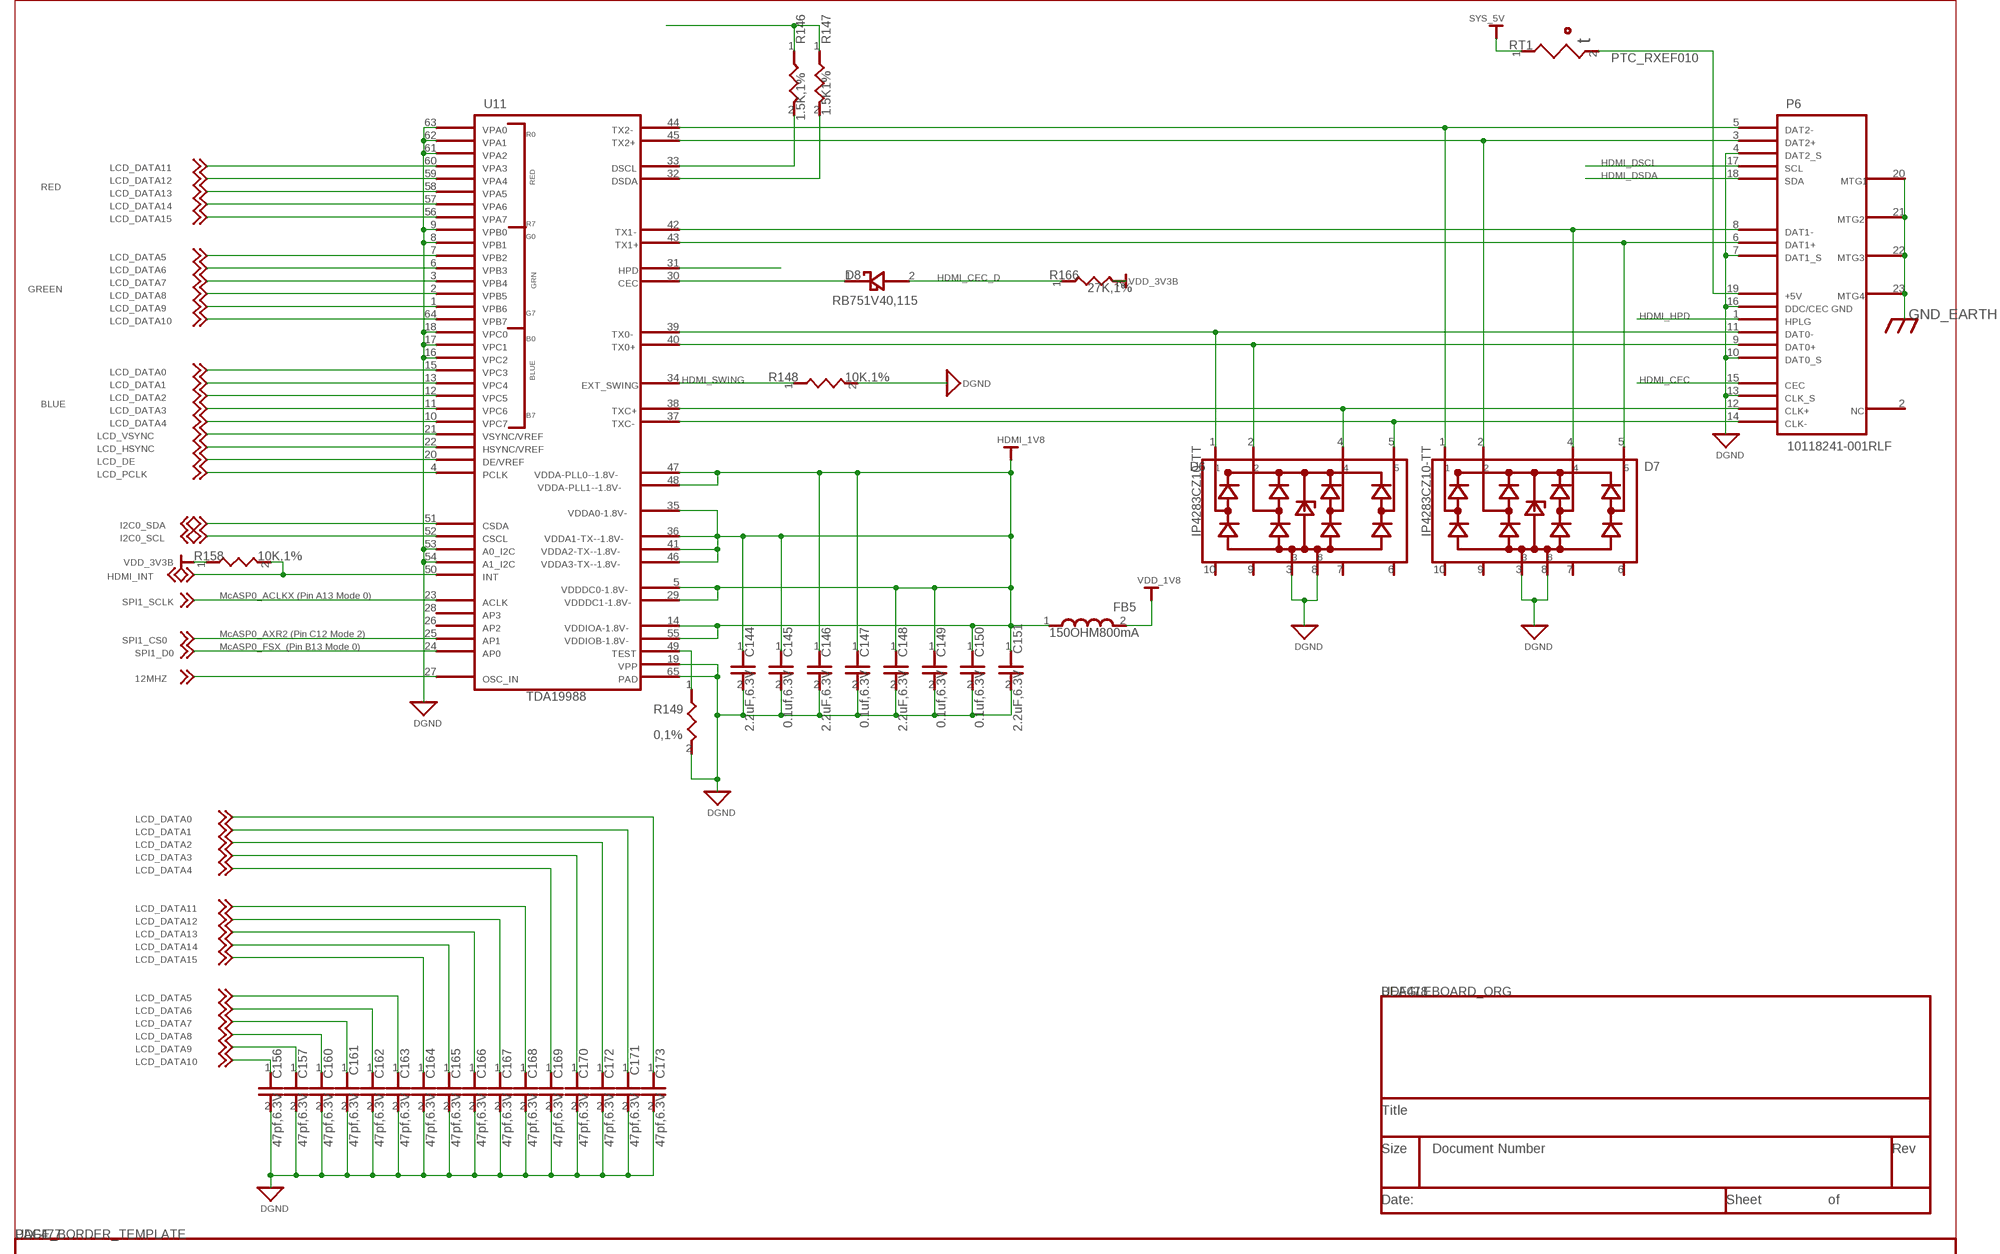
[diagram p12: schematic, sheet 10]
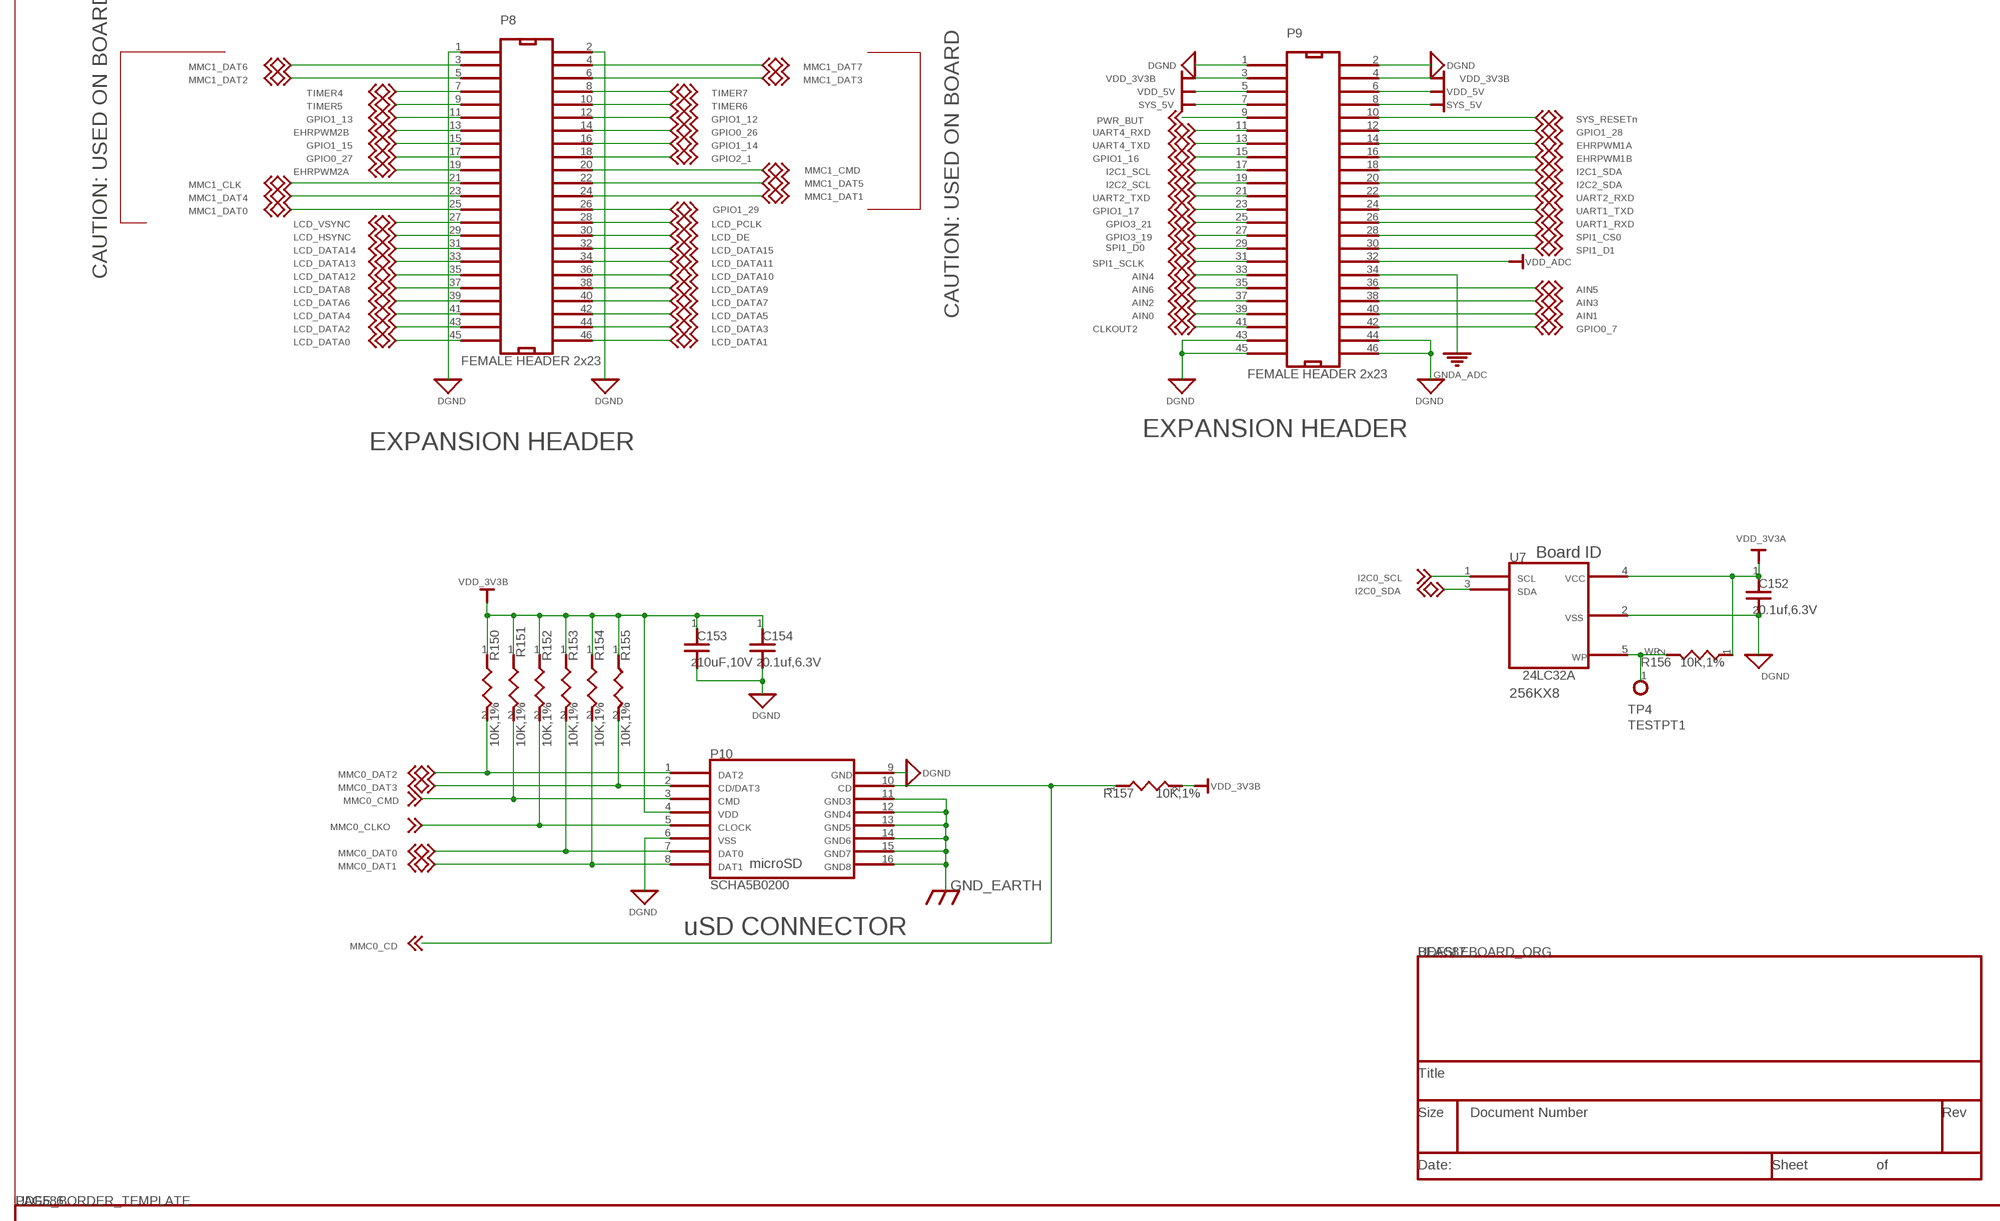
[diagram p13: schematic, sheet 11]

(export (version "E")
  (design (tool "Eeschema 10.0.6"))
  (components
    (comp (ref "C37")
      (value "0.1uf,6.3V")
      (footprint "eagle-import:402")
      (libsource (lib "eagle-import") (part "CAP_0.1UF_X5R_6.3V_20%_0201__40"))
    )
    (comp (ref "C38")
      (value "0.1uf,6.3V")
      (footprint "eagle-import:402")
      (libsource (lib "eagle-import") (part "CAP_0.1UF_X5R_6.3V_20%_0201__40"))
    )
    (comp (ref "C39")
      (value "10uF,10V")
      (footprint "eagle-import:805")
      (libsource (lib "eagle-import") (part "CAP_10UF_Y5V_10V_10%_0805_805_1"))
    )
    (comp (ref "C40")
      (value "10uF,10V")
      (footprint "eagle-import:805")
      (libsource (lib "eagle-import") (part "CAP_10UF_Y5V_10V_10%_0805_805_1"))
    )
    (comp (ref "C41")
      (value "0.1uf,6.3V")
      (footprint "eagle-import:402")
      (libsource (lib "eagle-import") (part "CAP_0.1UF_X5R_6.3V_20%_0201__40"))
    )
    (comp (ref "C42")
      (value "0.1uf,6.3V")
      (footprint "eagle-import:402")
      (libsource (lib "eagle-import") (part "CAP_0.1UF_X5R_6.3V_20%_0201__40"))
    )
    (comp (ref "C43")
      (value "0.1uf,6.3V")
      (footprint "eagle-import:402")
      (libsource (lib "eagle-import") (part "CAP_0.1UF_X5R_6.3V_20%_0201__40"))
    )
    (comp (ref "C44")
      (value "0.1uf,6.3V")
      (footprint "eagle-import:402")
      (libsource (lib "eagle-import") (part "CAP_0.1UF_X5R_6.3V_20%_0201__40"))
    )
    (comp (ref "C45")
      (value "0.1uf,6.3V")
      (footprint "eagle-import:402")
      (libsource (lib "eagle-import") (part "CAP_0.1UF_X5R_6.3V_20%_0201__40"))
    )
    (comp (ref "C46")
      (value "0.1uf,6.3V")
      (footprint "eagle-import:402")
      (libsource (lib "eagle-import") (part "CAP_0.1UF_X5R_6.3V_20%_0201__40"))
    )
    (comp (ref "C47")
      (value "0.1uf,6.3V")
      (footprint "eagle-import:402")
      (libsource (lib "eagle-import") (part "CAP_0.1UF_X5R_6.3V_20%_0201__40"))
    )
    (comp (ref "C48")
      (value "0.1uf,6.3V")
      (footprint "eagle-import:402")
      (libsource (lib "eagle-import") (part "CAP_0.1UF_X5R_6.3V_20%_0201__40"))
    )
    (comp (ref "C49")
      (value "0.1uf,6.3V")
      (footprint "eagle-import:402")
      (libsource (lib "eagle-import") (part "CAP_0.1UF_X5R_6.3V_20%_0201__40"))
    )
    (comp (ref "C50")
      (value "0.1uf,6.3V")
      (footprint "eagle-import:402")
      (libsource (lib "eagle-import") (part "CAP_0.1UF_X5R_6.3V_20%_0201__40"))
    )
    (comp (ref "C51")
      (value "0.1uf,6.3V")
      (footprint "eagle-import:402")
      (libsource (lib "eagle-import") (part "CAP_0.1UF_X5R_6.3V_20%_0201__40"))
    )
    (comp (ref "C52")
      (value "0.1uf,6.3V")
      (footprint "eagle-import:402")
      (libsource (lib "eagle-import") (part "CAP_0.1UF_X5R_6.3V_20%_0201__40"))
    )
    (comp (ref "C53")
      (value "0.1uf,6.3V")
      (footprint "eagle-import:402")
      (libsource (lib "eagle-import") (part "CAP_0.1UF_X5R_6.3V_20%_0201__40"))
    )
    (comp (ref "C54")
      (value "0.1uf,6.3V")
      (footprint "eagle-import:402")
      (libsource (lib "eagle-import") (part "CAP_0.1UF_X5R_6.3V_20%_0201__40"))
    )
    (comp (ref "C55")
      (value "10uF,10V")
      (footprint "eagle-import:805")
      (libsource (lib "eagle-import") (part "CAP_10UF_Y5V_10V_10%_0805_805_1"))
    )
    (comp (ref "C56")
      (value "0.1uf,6.3V")
      (footprint "eagle-import:402")
      (libsource (lib "eagle-import") (part "CAP_0.1UF_X5R_6.3V_20%_0201__40"))
    )
    (comp (ref "C57")
      (value "0.1uf,6.3V")
      (footprint "eagle-import:402")
      (libsource (lib "eagle-import") (part "CAP_0.1UF_X5R_6.3V_20%_0201__40"))
    )
    (comp (ref "C58")
      (value "0.1uf,6.3V")
      (footprint "eagle-import:402")
      (libsource (lib "eagle-import") (part "CAP_0.1UF_X5R_6.3V_20%_0201__40"))
    )
    (comp (ref "C59")
      (value "0.1uf,6.3V")
      (footprint "eagle-import:402")
      (libsource (lib "eagle-import") (part "CAP_0.1UF_X5R_6.3V_20%_0201__40"))
    )
    (comp (ref "C60")
      (value "0.1uf,6.3V")
      (footprint "eagle-import:402")
      (libsource (lib "eagle-import") (part "CAP_0.1UF_X5R_6.3V_20%_0201__40"))
    )
    (comp (ref "C61")
      (value "0.1uf,6.3V")
      (footprint "eagle-import:402")
      (libsource (lib "eagle-import") (part "CAP_0.1UF_X5R_6.3V_20%_0201__40"))
    )
    (comp (ref "C62")
      (value "10uF,10V")
      (footprint "eagle-import:805")
      (libsource (lib "eagle-import") (part "CAP_10UF_Y5V_10V_10%_0805_805_1"))
    )
    (comp (ref "C63")
      (value "0.1uf,6.3V")
      (footprint "eagle-import:402")
      (libsource (lib "eagle-import") (part "CAP_0.1UF_X5R_6.3V_20%_0201__40"))
    )
    (comp (ref "C64")
      (value "0.1uf,6.3V")
      (footprint "eagle-import:402")
      (libsource (lib "eagle-import") (part "CAP_0.1UF_X5R_6.3V_20%_0201__40"))
    )
    (comp (ref "C65")
      (value "0.1uf,6.3V")
      (footprint "eagle-import:402")
      (libsource (lib "eagle-import") (part "CAP_0.1UF_X5R_6.3V_20%_0201__40"))
    )
    (comp (ref "C66")
      (value "0.1uf,6.3V")
      (footprint "eagle-import:402")
      (libsource (lib "eagle-import") (part "CAP_0.1UF_X5R_6.3V_20%_0201__40"))
    )
    (comp (ref "C67")
      (value "0.1uf,6.3V")
      (footprint "eagle-import:402")
      (libsource (lib "eagle-import") (part "CAP_0.1UF_X5R_6.3V_20%_0201__40"))
    )
    (comp (ref "C68")
      (value "0.1uf,6.3V")
      (footprint "eagle-import:402")
      (libsource (lib "eagle-import") (part "CAP_0.1UF_X5R_6.3V_20%_0201__40"))
    )
    (comp (ref "C69")
      (value "0.1uf,6.3V")
      (footprint "eagle-import:402")
      (libsource (lib "eagle-import") (part "CAP_0.1UF_X5R_6.3V_20%_0201__40"))
    )
    (comp (ref "C70")
      (value "0.1uf,6.3V")
      (footprint "eagle-import:402")
      (libsource (lib "eagle-import") (part "CAP_0.1UF_X5R_6.3V_20%_0201__40"))
    )
    (comp (ref "C71")
      (value "0.1uf,6.3V")
      (footprint "eagle-import:402")
      (libsource (lib "eagle-import") (part "CAP_0.1UF_X5R_6.3V_20%_0201__40"))
    )
    (comp (ref "C72")
      (value "0.1uf,6.3V")
      (footprint "eagle-import:402")
      (libsource (lib "eagle-import") (part "CAP_0.1UF_X5R_6.3V_20%_0201__40"))
    )
    (comp (ref "C73")
      (value "0.1uf,6.3V")
      (footprint "eagle-import:402")
      (libsource (lib "eagle-import") (part "CAP_0.1UF_X5R_6.3V_20%_0201__40"))
    )
    (comp (ref "C74")
      (value "0.1uf,6.3V")
      (footprint "eagle-import:402")
      (libsource (lib "eagle-import") (part "CAP_0.1UF_X5R_6.3V_20%_0201__40"))
    )
    (comp (ref "C75")
      (value "0.1uf,6.3V")
      (footprint "eagle-import:402")
      (libsource (lib "eagle-import") (part "CAP_0.1UF_X5R_6.3V_20%_0201__40"))
    )
    (comp (ref "C76")
      (value "0.1uf,6.3V")
      (footprint "eagle-import:402")
      (libsource (lib "eagle-import") (part "CAP_0.1UF_X5R_6.3V_20%_0201__40"))
    )
    (comp (ref "C77")
      (value "10uF,10V")
      (footprint "eagle-import:805")
      (libsource (lib "eagle-import") (part "CAP_10UF_Y5V_10V_10%_0805_805_1"))
    )
    (comp (ref "C78")
      (value "0.1uf,6.3V")
      (footprint "eagle-import:402")
      (libsource (lib "eagle-import") (part "CAP_0.1UF_X5R_6.3V_20%_0201__40"))
    )
    (comp (ref "C79")
      (value "0.1uf,6.3V")
      (footprint "eagle-import:402")
      (libsource (lib "eagle-import") (part "CAP_0.1UF_X5R_6.3V_20%_0201__40"))
    )
    (comp (ref "C80")
      (value "0.1uf,6.3V")
      (footprint "eagle-import:402")
      (libsource (lib "eagle-import") (part "CAP_0.1UF_X5R_6.3V_20%_0201__40"))
    )
    (comp (ref "C81")
      (value "0.1uf,6.3V")
      (footprint "eagle-import:402")
      (libsource (lib "eagle-import") (part "CAP_0.1UF_X5R_6.3V_20%_0201__40"))
    )
    (comp (ref "C82")
      (value "0.1uf,6.3V")
      (footprint "eagle-import:402")
      (libsource (lib "eagle-import") (part "CAP_0.1UF_X5R_6.3V_20%_0201__40"))
    )
    (comp (ref "C83")
      (value "0.1uf,6.3V")
      (footprint "eagle-import:402")
      (libsource (lib "eagle-import") (part "CAP_0.1UF_X5R_6.3V_20%_0201__40"))
    )
    (comp (ref "C84")
      (value "0.1uf,6.3V")
      (footprint "eagle-import:402")
      (libsource (lib "eagle-import") (part "CAP_0.1UF_X5R_6.3V_20%_0201__40"))
    )
    (comp (ref "C85")
      (value "0.1uf,6.3V")
      (footprint "eagle-import:402")
      (libsource (lib "eagle-import") (part "CAP_0.1UF_X5R_6.3V_20%_0201__40"))
    )
    (comp (ref "C86")
      (value "0.1uf,6.3V")
      (footprint "eagle-import:402")
      (libsource (lib "eagle-import") (part "CAP_0.1UF_X5R_6.3V_20%_0201__40"))
    )
    (comp (ref "C87")
      (value "0.1uf,6.3V")
      (footprint "eagle-import:402")
      (libsource (lib "eagle-import") (part "CAP_0.1UF_X5R_6.3V_20%_0201__40"))
    )
    (comp (ref "C88")
      (value "0.1uf,6.3V")
      (footprint "eagle-import:402")
      (libsource (lib "eagle-import") (part "CAP_0.1UF_X5R_6.3V_20%_0201__40"))
    )
    (comp (ref "C89")
      (value "1uF,10V")
      (footprint "eagle-import:402")
      (libsource (lib "eagle-import") (part "CAP_1.0UF_X5R_10V_10%_0402_402_"))
    )
    (comp (ref "C90")
      (value "1uF,10V")
      (footprint "eagle-import:402")
      (libsource (lib "eagle-import") (part "CAP_1.0UF_X5R_10V_10%_0402_402_"))
    )
    (comp (ref "C91")
      (value "1uF,10V")
      (footprint "eagle-import:402")
      (libsource (lib "eagle-import") (part "CAP_1.0UF_X5R_10V_10%_0402_402_"))
    )
    (comp (ref "C92")
      (value "0.1uf,6.3V")
      (footprint "eagle-import:402")
      (libsource (lib "eagle-import") (part "CAP_0.1UF_X5R_6.3V_20%_0201__40"))
    )
    (comp (ref "C93")
      (value "0.1uf,6.3V")
      (footprint "eagle-import:402")
      (libsource (lib "eagle-import") (part "CAP_0.1UF_X5R_6.3V_20%_0201__40"))
    )
    (comp (ref "C94")
      (value "0.1uf,6.3V")
      (footprint "eagle-import:402")
      (libsource (lib "eagle-import") (part "CAP_0.1UF_X5R_6.3V_20%_0201__40"))
    )
    (comp (ref "C95")
      (value "10uF,10V")
      (footprint "eagle-import:805")
      (libsource (lib "eagle-import") (part "CAP_10UF_Y5V_10V_10%_0805_805_1"))
    )
    (comp (ref "C96")
      (value "10uF,10V")
      (footprint "eagle-import:805")
      (libsource (lib "eagle-import") (part "CAP_10UF_Y5V_10V_10%_0805_805_1"))
    )
    (comp (ref "C97")
      (value "0.1uf,6.3V")
      (footprint "eagle-import:402")
      (libsource (lib "eagle-import") (part "CAP_0.1UF_X5R_6.3V_20%_0201__40"))
    )
    (comp (ref "C98")
      (value "0.1uf,6.3V")
      (footprint "eagle-import:402")
      (libsource (lib "eagle-import") (part "CAP_0.1UF_X5R_6.3V_20%_0201__40"))
    )
    (comp (ref "C99")
      (value "0.1uf,6.3V")
      (footprint "eagle-import:402")
      (libsource (lib "eagle-import") (part "CAP_0.1UF_X5R_6.3V_20%_0201__40"))
    )
    (comp (ref "C100")
      (value "0.1uf,6.3V")
      (footprint "eagle-import:402")
      (libsource (lib "eagle-import") (part "CAP_0.1UF_X5R_6.3V_20%_0201__40"))
    )
    (comp (ref "C101")
      (value "0.1uf,6.3V")
      (footprint "eagle-import:402")
      (libsource (lib "eagle-import") (part "CAP_0.1UF_X5R_6.3V_20%_0201__40"))
    )
    (comp (ref "C102")
      (value "0.1uf,6.3V")
      (footprint "eagle-import:402")
      (libsource (lib "eagle-import") (part "CAP_0.1UF_X5R_6.3V_20%_0201__40"))
    )
    (comp (ref "C103")
      (value "0.1uf,6.3V")
      (footprint "eagle-import:402")
      (libsource (lib "eagle-import") (part "CAP_0.1UF_X5R_6.3V_20%_0201__40"))
    )
    (comp (ref "C104")
      (value "1uF,10V")
      (footprint "eagle-import:402")
      (libsource (lib "eagle-import") (part "CAP_1.0UF_X5R_10V_10%_0402_402_"))
    )
    (comp (ref "C105")
      (value "0.1uf,6.3V")
      (footprint "eagle-import:402")
      (libsource (lib "eagle-import") (part "CAP_0.1UF_X5R_6.3V_20%_0201__40"))
    )
    (comp (ref "C106")
      (value "0.1uf,6.3V")
      (footprint "eagle-import:402")
      (libsource (lib "eagle-import") (part "CAP_0.1UF_X5R_6.3V_20%_0201__40"))
    )
    (comp (ref "FB1")
      (value "150OHM800mA")
      (footprint "eagle-import:SM-7351-IND-0805")
      (libsource (lib "eagle-import") (part "FER_180_200_0_SM-7351-IND-0805_"))
    )
    (comp (ref "FB2")
      (value "150OHM800mA")
      (footprint "eagle-import:SM-7351-IND-0805")
      (libsource (lib "eagle-import") (part "FER_180_200_0_SM-7351-IND-0805_"))
    )
    (comp (ref "FB3")
      (value "150OHM800mA")
      (footprint "eagle-import:SM-7351-IND-0805")
      (libsource (lib "eagle-import") (part "FER_180_200_0_SM-7351-IND-0805_"))
    )
    (comp (ref "R54")
      (value "10K,1%")
      (footprint "eagle-import:402")
      (libsource (lib "eagle-import") (part "RES_10K_1/16W_1%_0402_402_10K_1"))
    )
    (comp (ref "TP2")
      (value "TESTPT1")
      (footprint "eagle-import:TP60C_SMD")
      (libsource (lib "eagle-import") (part "TESTPT1_TP60C_SMD"))
    )
    (comp (ref "TP3")
      (value "TESTPT1")
      (footprint "eagle-import:TP60C_SMD")
      (libsource (lib "eagle-import") (part "TESTPT1_TP60C_SMD"))
    )
    (comp (ref "U5")
      (value "C")
      (footprint "eagle-import:AM33XX_15X15")
      (libsource (lib "eagle-import") (part "IC_AM335X_ZCZ_AM33XX_15X15_XAM3"))
    )
    (comp (ref "D2")
      (value "LTST-C191TBKT")
      (footprint "eagle-import:LED_0603")
      (libsource (lib "eagle-import") (part "LED_LTST-C150GKT_0_LED_0603_DIS"))
    )
    (comp (ref "D3")
      (value "LTST-C191TBKT")
      (footprint "eagle-import:LED_0603")
      (libsource (lib "eagle-import") (part "LED_LTST-C150GKT_0_LED_0603_DIS"))
    )
    (comp (ref "D4")
      (value "LTST-C191TBKT")
      (footprint "eagle-import:LED_0603")
      (libsource (lib "eagle-import") (part "LED_LTST-C150GKT_0_LED_0603_DIS"))
    )
    (comp (ref "D5")
      (value "LTST-C191TBKT")
      (footprint "eagle-import:LED_0603")
      (libsource (lib "eagle-import") (part "LED_LTST-C150GKT_0_LED_0603_DIS"))
    )
    (comp (ref "Q1")
      (value "B")
      (footprint "eagle-import:SMINI6-F3-B")
      (libsource (lib "eagle-import") (part "RN1907_SMINI6-F3-B_DMC56404"))
    )
    (comp (ref "Q2")
      (value "B")
      (footprint "eagle-import:SMINI6-F3-B")
      (libsource (lib "eagle-import") (part "RN1907_SMINI6-F3-B_DMC56404"))
    )
    (comp (ref "R55")
      (value "100K,1%,DNI")
      (footprint "eagle-import:402")
      (libsource (lib "eagle-import") (part "RES_100K_1/16W_1%_0402_402_10_1"))
    )
    (comp (ref "R56")
      (value "100K,1%")
      (footprint "eagle-import:402")
      (libsource (lib "eagle-import") (part "RES_100K_1/16W_1%_0402_402_100K"))
    )
    (comp (ref "R57")
      (value "100K,1%,DNI")
      (footprint "eagle-import:402")
      (libsource (lib "eagle-import") (part "RES_100K_1/16W_1%_0402_402_10_1"))
    )
    (comp (ref "R58")
      (value "100K,1%,DNI")
      (footprint "eagle-import:402")
      (libsource (lib "eagle-import") (part "RES_100K_1/16W_1%_0402_402_10_1"))
    )
    (comp (ref "R59")
      (value "100K,1%,DNI")
      (footprint "eagle-import:402")
      (libsource (lib "eagle-import") (part "RES_100K_1/16W_1%_0402_402_10_1"))
    )
    (comp (ref "R60")
      (value "100K,1%,DNI")
      (footprint "eagle-import:402")
      (libsource (lib "eagle-import") (part "RES_100K_1/16W_1%_0402_402_10_1"))
    )
    (comp (ref "R61")
      (value "100K,1%,DNI")
      (footprint "eagle-import:402")
      (libsource (lib "eagle-import") (part "RES_100K_1/16W_1%_0402_402_10_1"))
    )
    (comp (ref "R62")
      (value "100K,1%,DNI")
      (footprint "eagle-import:402")
      (libsource (lib "eagle-import") (part "RES_100K_1/16W_1%_0402_402_10_1"))
    )
    (comp (ref "R63")
      (value "100K,1%,DNI")
      (footprint "eagle-import:402")
      (libsource (lib "eagle-import") (part "RES_100K_1/16W_1%_0402_402_10_1"))
    )
    (comp (ref "R64")
      (value "100K,1%,DNI")
      (footprint "eagle-import:402")
      (libsource (lib "eagle-import") (part "RES_100K_1/16W_1%_0402_402_10_1"))
    )
    (comp (ref "R65")
      (value "100K,1%")
      (footprint "eagle-import:402")
      (libsource (lib "eagle-import") (part "RES_100K_1/16W_1%_0402_402_100K"))
    )
    (comp (ref "R66")
      (value "100K,1%")
      (footprint "eagle-import:402")
      (libsource (lib "eagle-import") (part "RES_100K_1/16W_1%_0402_402_100K"))
    )
    (comp (ref "R67")
      (value "100K,1%")
      (footprint "eagle-import:402")
      (libsource (lib "eagle-import") (part "RES_100K_1/16W_1%_0402_402_100K"))
    )
    (comp (ref "R68")
      (value "100K,1%")
      (footprint "eagle-import:402")
      (libsource (lib "eagle-import") (part "RES_100K_1/16W_1%_0402_402_100K"))
    )
    (comp (ref "R69")
      (value "100K,1%,DNI")
      (footprint "eagle-import:402")
      (libsource (lib "eagle-import") (part "RES_100K_1/16W_1%_0402_402_10_1"))
    )
    (comp (ref "R70")
      (value "100K,1%,DNI")
      (footprint "eagle-import:402")
      (libsource (lib "eagle-import") (part "RES_100K_1/16W_1%_0402_402_10_1"))
    )
    (comp (ref "R71")
      (value "820,5%")
      (footprint "eagle-import:402")
      (libsource (lib "eagle-import") (part "RES_470_1/10W_5%_0402_402_820_5"))
    )
    (comp (ref "R72")
      (value "820,5%")
      (footprint "eagle-import:402")
      (libsource (lib "eagle-import") (part "RES_470_1/10W_5%_0402_402_820_5"))
    )
    (comp (ref "R73")
      (value "820,5%")
      (footprint "eagle-import:402")
      (libsource (lib "eagle-import") (part "RES_470_1/10W_5%_0402_402_820_5"))
    )
    (comp (ref "R74")
      (value "820,5%")
      (footprint "eagle-import:402")
      (libsource (lib "eagle-import") (part "RES_470_1/10W_5%_0402_402_820_5"))
    )
    (comp (ref "R75")
      (value "100,1%")
      (footprint "eagle-import:402")
      (libsource (lib "eagle-import") (part "RES_100K_1/16W_1%_0402_402_100_"))
    )
    (comp (ref "R76")
      (value "100K,1%")
      (footprint "eagle-import:402")
      (libsource (lib "eagle-import") (part "RES_100K_1/16W_1%_0402_402_100K"))
    )
    (comp (ref "R77")
      (value "100K,1%")
      (footprint "eagle-import:402")
      (libsource (lib "eagle-import") (part "RES_100K_1/16W_1%_0402_402_100K"))
    )
    (comp (ref "R78")
      (value "100K,1%")
      (footprint "eagle-import:402")
      (libsource (lib "eagle-import") (part "RES_100K_1/16W_1%_0402_402_100K"))
    )
    (comp (ref "R79")
      (value "100K,1%")
      (footprint "eagle-import:402")
      (libsource (lib "eagle-import") (part "RES_100K_1/16W_1%_0402_402_100K"))
    )
    (comp (ref "R80")
      (value "100K,1%")
      (footprint "eagle-import:402")
      (libsource (lib "eagle-import") (part "RES_100K_1/16W_1%_0402_402_100K"))
    )
    (comp (ref "R81")
      (value "100K,1%,DNI")
      (footprint "eagle-import:402")
      (libsource (lib "eagle-import") (part "RES_100K_1/16W_1%_0402_402_10_1"))
    )
    (comp (ref "R82")
      (value "100K,1%")
      (footprint "eagle-import:402")
      (libsource (lib "eagle-import") (part "RES_100K_1/16W_1%_0402_402_100K"))
    )
    (comp (ref "R83")
      (value "100K,1%")
      (footprint "eagle-import:402")
      (libsource (lib "eagle-import") (part "RES_100K_1/16W_1%_0402_402_100K"))
    )
    (comp (ref "R84")
      (value "100K,1%")
      (footprint "eagle-import:402")
      (libsource (lib "eagle-import") (part "RES_100K_1/16W_1%_0402_402_100K"))
    )
    (comp (ref "R85")
      (value "100K,1%")
      (footprint "eagle-import:402")
      (libsource (lib "eagle-import") (part "RES_100K_1/16W_1%_0402_402_100K"))
    )
    (comp (ref "R86")
      (value "100K,1%")
      (footprint "eagle-import:402")
      (libsource (lib "eagle-import") (part "RES_100K_1/16W_1%_0402_402_100K"))
    )
    (comp (ref "R87")
      (value "100K,1%")
      (footprint "eagle-import:402")
      (libsource (lib "eagle-import") (part "RES_100K_1/16W_1%_0402_402_100K"))
    )
    (comp (ref "R88")
      (value "100K,1%")
      (footprint "eagle-import:402")
      (libsource (lib "eagle-import") (part "RES_100K_1/16W_1%_0402_402_100K"))
    )
    (comp (ref "R89")
      (value "100K,1%")
      (footprint "eagle-import:402")
      (libsource (lib "eagle-import") (part "RES_100K_1/16W_1%_0402_402_100K"))
    )
    (comp (ref "R90")
      (value "100K,1%,DNI")
      (footprint "eagle-import:402")
      (libsource (lib "eagle-import") (part "RES_100K_1/16W_1%_0402_402_10_1"))
    )
    (comp (ref "R91")
      (value "100K,1%,DNI")
      (footprint "eagle-import:402")
      (libsource (lib "eagle-import") (part "RES_100K_1/16W_1%_0402_402_10_1"))
    )
    (comp (ref "R92")
      (value "100K,1%,DNI")
      (footprint "eagle-import:402")
      (libsource (lib "eagle-import") (part "RES_100K_1/16W_1%_0402_402_10_1"))
    )
    (comp (ref "R93")
      (value "100K,1%,DNI")
      (footprint "eagle-import:402")
      (libsource (lib "eagle-import") (part "RES_100K_1/16W_1%_0402_402_10_1"))
    )
    (comp (ref "R94")
      (value "100K,1%")
      (footprint "eagle-import:402")
      (libsource (lib "eagle-import") (part "RES_100K_1/16W_1%_0402_402_100K"))
    )
    (comp (ref "R95")
      (value "100K,1%")
      (footprint "eagle-import:402")
      (libsource (lib "eagle-import") (part "RES_100K_1/16W_1%_0402_402_100K"))
    )
    (comp (ref "S2")
      (value "KMR231GLFS")
      (footprint "eagle-import:SW4SMD_63X161LS")
      (libsource (lib "eagle-import") (part "SW_KT11P2JM_1_SW4SMD_63X161LS_D"))
    )
    (comp (ref "C131")
      (value "0.1uf,6.3V")
      (footprint "eagle-import:402")
      (libsource (lib "eagle-import") (part "CAP_0.1UF_X5R_6.3V_20%_0201__40"))
    )
    (comp (ref "C132")
      (value "0.1uf,6.3V")
      (footprint "eagle-import:402")
      (libsource (lib "eagle-import") (part "CAP_0.1UF_X5R_6.3V_20%_0201__40"))
    )
    (comp (ref "C133")
      (value "10uF,10V")
      (footprint "eagle-import:805")
      (libsource (lib "eagle-import") (part "CAP_10UF_Y5V_10V_10%_0805_805_1"))
    )
    (comp (ref "C134")
      (value "1uF,10V")
      (footprint "eagle-import:402")
      (libsource (lib "eagle-import") (part "CAP_1.0UF_X5R_10V_10%_0402_402_"))
    )
    (comp (ref "C135")
      (value "0.1uf,6.3V")
      (footprint "eagle-import:402")
      (libsource (lib "eagle-import") (part "CAP_0.1UF_X5R_6.3V_20%_0201__40"))
    )
    (comp (ref "C136")
      (value "470pF,6.3V")
      (footprint "eagle-import:0402")
      (libsource (lib "eagle-import") (part "470PF/5%/50V/C0G/0603_0_0402_47"))
    )
    (comp (ref "C137")
      (value "15pF,DNI")
      (footprint "eagle-import:402")
      (libsource (lib "eagle-import") (part "CAP_0402_100PF_COG_50V_402_15PF"))
    )
    (comp (ref "C138")
      (value "15pF,DNI")
      (footprint "eagle-import:402")
      (libsource (lib "eagle-import") (part "CAP_0402_100PF_COG_50V_402_15PF"))
    )
    (comp (ref "C139")
      (value "15pF,DNI")
      (footprint "eagle-import:402")
      (libsource (lib "eagle-import") (part "CAP_0402_100PF_COG_50V_402_15PF"))
    )
    (comp (ref "C140")
      (value "15pF,DNI")
      (footprint "eagle-import:402")
      (libsource (lib "eagle-import") (part "CAP_0402_100PF_COG_50V_402_15PF"))
    )
    (comp (ref "C141")
      (value "0.022uF,10V")
      (footprint "eagle-import:402")
      (libsource (lib "eagle-import") (part "CAP_0402_0.1UF_X5R_10V_402_0.02"))
    )
    (comp (ref "C142")
      (value "30pF,50V")
      (footprint "eagle-import:402")
      (libsource (lib "eagle-import") (part "CAP_30PF_COG_50V_5%_0402_402_30"))
    )
    (comp (ref "C143")
      (value "30pF,50V")
      (footprint "eagle-import:402")
      (libsource (lib "eagle-import") (part "CAP_30PF_COG_50V_5%_0402_402_30"))
    )
    (comp (ref "FB4")
      (value "150OHM800mA")
      (footprint "eagle-import:SM-7351-IND-0805")
      (libsource (lib "eagle-import") (part "FER_180_200_0_SM-7351-IND-0805_"))
    )
    (comp (ref "P5")
      (value "LPJ0011BBNL")
      (footprint "eagle-import:RJ45-7499010211A")
      (libsource (lib "eagle-import") (part "CONN_RJ45_MAG_WE_0_RJ45-7499010"))
    )
    (comp (ref "R112")
      (value "1.5K,1%")
      (footprint "eagle-import:402")
      (libsource (lib "eagle-import") (part "RES_4.75K_1/16W_1%_0402_402_1.5"))
    )
    (comp (ref "R113")
      (value "1.5K,1%")
      (footprint "eagle-import:402")
      (libsource (lib "eagle-import") (part "RES_4.75K_1/16W_1%_0402_402_1.5"))
    )
    (comp (ref "R114")
      (value "1.5K,1%")
      (footprint "eagle-import:402")
      (libsource (lib "eagle-import") (part "RES_4.75K_1/16W_1%_0402_402_1.5"))
    )
    (comp (ref "R115")
      (value "10K,1%")
      (footprint "eagle-import:402")
      (libsource (lib "eagle-import") (part "RES_4.75K_1/16W_1%_0402_402_10K"))
    )
    (comp (ref "R116")
      (value "10K,1%")
      (footprint "eagle-import:402")
      (libsource (lib "eagle-import") (part "RES_4.75K_1/16W_1%_0402_402_10K"))
    )
    (comp (ref "R117")
      (value "10K,1%")
      (footprint "eagle-import:402")
      (libsource (lib "eagle-import") (part "RES_4.75K_1/16W_1%_0402_402_10K"))
    )
    (comp (ref "R118")
      (value "10K,1%")
      (footprint "eagle-import:402")
      (libsource (lib "eagle-import") (part "RES_4.75K_1/16W_1%_0402_402_10K"))
    )
    (comp (ref "R119")
      (value "1.5K,1%")
      (footprint "eagle-import:402")
      (libsource (lib "eagle-import") (part "RES_1.5K_1/16W_5%_0402_402_1.5K"))
    )
    (comp (ref "R120")
      (value "49.9,1%")
      (footprint "eagle-import:402")
      (libsource (lib "eagle-import") (part "RES_4.7K_0402_402_49.9_1%"))
    )
    (comp (ref "R121")
      (value "49.9,1%")
      (footprint "eagle-import:402")
      (libsource (lib "eagle-import") (part "RES_4.7K_0402_402_49.9_1%"))
    )
    (comp (ref "R122")
      (value "49.9,1%")
      (footprint "eagle-import:402")
      (libsource (lib "eagle-import") (part "RES_4.7K_0402_402_49.9_1%"))
    )
    (comp (ref "R123")
      (value "49.9,1%")
      (footprint "eagle-import:402")
      (libsource (lib "eagle-import") (part "RES_4.7K_0402_402_49.9_1%"))
    )
    (comp (ref "R124")
      (value "10,1%,DNI")
      (footprint "eagle-import:402")
      (libsource (lib "eagle-import") (part "100-1/10W-1%-0603_4_402_10_1%_D"))
    )
    (comp (ref "R125")
      (value "100,1%")
      (footprint "eagle-import:402")
      (libsource (lib "eagle-import") (part "100-1/10W-1%-0603_4_402_100_1%"))
    )
    (comp (ref "R126")
      (value "100,1%")
      (footprint "eagle-import:402")
      (libsource (lib "eagle-import") (part "100-1/10W-1%-0603_4_402_100_1%"))
    )
    (comp (ref "R127")
      (value "100,1%")
      (footprint "eagle-import:402")
      (libsource (lib "eagle-import") (part "RES_100_1/10W_5%_0402_402_100_1"))
    )
    (comp (ref "R128")
      (value "100,1%")
      (footprint "eagle-import:402")
      (libsource (lib "eagle-import") (part "RES_100_1/10W_5%_0402_402_100_1"))
    )
    (comp (ref "R129")
      (value "100,1%")
      (footprint "eagle-import:402")
      (libsource (lib "eagle-import") (part "100-1/10W-1%-0603_4_402_100_1%"))
    )
    (comp (ref "R130")
      (value "470,5%")
      (footprint "eagle-import:402")
      (libsource (lib "eagle-import") (part "RES_470_1/10W_5%_0402_402_470_5"))
    )
    (comp (ref "R131")
      (value "100,1%")
      (footprint "eagle-import:402")
      (libsource (lib "eagle-import") (part "RES_100_1/10W_5%_0402_402_100_1"))
    )
    (comp (ref "R132")
      (value "470,5%")
      (footprint "eagle-import:402")
      (libsource (lib "eagle-import") (part "RES_470_1/10W_5%_0402_402_470_5"))
    )
    (comp (ref "R133")
      (value "100,1%")
      (footprint "eagle-import:402")
      (libsource (lib "eagle-import") (part "RES_100_1/10W_5%_0402_402_100_1"))
    )
    (comp (ref "R134")
      (value "100,1%")
      (footprint "eagle-import:402")
      (libsource (lib "eagle-import") (part "100-1/10W-1%-0603_4_402_100_1%"))
    )
    (comp (ref "R135")
      (value "10K,1%")
      (footprint "eagle-import:402")
      (libsource (lib "eagle-import") (part "RES_10K_1/16W_1%_0402_402_10K_1"))
    )
    (comp (ref "R136")
      (value ".1,0805")
      (footprint "eagle-import:805")
      (libsource (lib "eagle-import") (part "RES_0.1_0805_805_.1_0805"))
    )
    (comp (ref "R137")
      (value "0,1%")
      (footprint "eagle-import:402")
      (libsource (lib "eagle-import") (part "RES_10K_1/16W_1%_0402_402_0_1%"))
    )
    (comp (ref "R138")
      (value "100,1%")
      (footprint "eagle-import:402")
      (libsource (lib "eagle-import") (part "100-1/10W-1%-0603_4_402_100_1%"))
    )
    (comp (ref "R139")
      (value "100,1%")
      (footprint "eagle-import:402")
      (libsource (lib "eagle-import") (part "RES_100_1/10W_5%_0402_402_100_1"))
    )
    (comp (ref "R140")
      (value "0,1%,DNI")
      (footprint "eagle-import:402")
      (libsource (lib "eagle-import") (part "RES_0_1/16W_1%_0402_402_0_1%_DN"))
    )
    (comp (ref "R141")
      (value "1M,1%,DNI")
      (footprint "eagle-import:402")
      (libsource (lib "eagle-import") (part "RES_1M_1/16W_1%_0402_402_1M_1%_"))
    )
    (comp (ref "R142")
      (value "0,1%")
      (footprint "eagle-import:402")
      (libsource (lib "eagle-import") (part "RES_0_1/16W_1%_0402_402_0_1%"))
    )
    (comp (ref "R143")
      (value "10,1%")
      (footprint "eagle-import:402")
      (libsource (lib "eagle-import") (part "RES_10K_1/16W_1%_0402_402_10_1%"))
    )
    (comp (ref "R144")
      (value "12.1K,1%")
      (footprint "eagle-import:402")
      (libsource (lib "eagle-import") (part "RES_12.1K_1/16W_1%_0402_402_12."))
    )
    (comp (ref "R145")
      (value "10K,1%")
      (footprint "eagle-import:402")
      (libsource (lib "eagle-import") (part "RES_10K_1/16W_1%_0402_402_10K_1"))
    )
    (comp (ref "U14")
      (value "LAN8710A")
      (footprint "eagle-import:QFN32_5X5MM_EP3P3MM")
      (libsource (lib "eagle-import") (part "LAN8710_QFN32_1_QFN32_5X5MM_EP3"))
    )
    (comp (ref "Y3")
      (value "25.000MHz")
      (footprint "eagle-import:XTAL150SMD_125X196")
      (libsource (lib "eagle-import") (part "SUNTSU_ITEMP_25MHZ__0.005%_20PF"))
    )
    (comp (ref "C152")
      (value "0.1uf,6.3V")
      (footprint "eagle-import:402")
      (libsource (lib "eagle-import") (part "CAP_0.1UF_X5R_6.3V_20%_0201__40"))
    )
    (comp (ref "C153")
      (value "10uF,10V")
      (footprint "eagle-import:805")
      (libsource (lib "eagle-import") (part "CAP_10UF_Y5V_10V_10%_0805_805_1"))
    )
    (comp (ref "C154")
      (value "0.1uf,6.3V")
      (footprint "eagle-import:402")
      (libsource (lib "eagle-import") (part "CAP_0.1UF_X5R_6.3V_20%_0201__40"))
    )
    (comp (ref "P8")
      (value "FEMALE HEADER 2x23")
      (footprint "eagle-import:HEADER23X2")
      (libsource (lib "eagle-import") (part "HDR_46_F_2_0.1_0.1_HEADER23X2_F"))
    )
    (comp (ref "P9")
      (value "FEMALE HEADER 2x23")
      (footprint "eagle-import:HEADER23X2")
      (libsource (lib "eagle-import") (part "HDR_46_F_2_0.1_0.1_HEADER23X2_F"))
    )
    (comp (ref "P10")
      (value "SCHA5B0200")
      (footprint "eagle-import:SD-MICRO-SCHA5B0300")
      (libsource (lib "eagle-import") (part "MICROSD_CONN_8_SD-MICRO-SCHA5B0"))
    )
    (comp (ref "R150")
      (value "10K,1%")
      (footprint "eagle-import:402")
      (libsource (lib "eagle-import") (part "RES_10K_1/16W_1%_0402_402_10K_1"))
    )
    (comp (ref "R151")
      (value "10K,1%")
      (footprint "eagle-import:402")
      (libsource (lib "eagle-import") (part "RES_10K_1/16W_1%_0402_402_10K_1"))
    )
    (comp (ref "R152")
      (value "10K,1%")
      (footprint "eagle-import:402")
      (libsource (lib "eagle-import") (part "RES_10K_1/16W_1%_0402_402_10K_1"))
    )
    (comp (ref "R153")
      (value "10K,1%")
      (footprint "eagle-import:402")
      (libsource (lib "eagle-import") (part "RES_10K_1/16W_1%_0402_402_10K_1"))
    )
    (comp (ref "R154")
      (value "10K,1%")
      (footprint "eagle-import:402")
      (libsource (lib "eagle-import") (part "RES_10K_1/16W_1%_0402_402_10K_1"))
    )
    (comp (ref "R155")
      (value "10K,1%")
      (footprint "eagle-import:402")
      (libsource (lib "eagle-import") (part "RES_10K_1/16W_1%_0402_402_10K_1"))
    )
    (comp (ref "R156")
      (value "10K,1%")
      (footprint "eagle-import:402")
      (libsource (lib "eagle-import") (part "RES_0_1/16W_1%_0402_402_10K_1%"))
    )
    (comp (ref "R157")
      (value "10K,1%")
      (footprint "eagle-import:402")
      (libsource (lib "eagle-import") (part "RES_10K_1/16W_1%_0402_402_10K_1"))
    )
    (comp (ref "TP4")
      (value "TESTPT1")
      (footprint "eagle-import:TP1-8040")
      (libsource (lib "eagle-import") (part "TESTPT1_TP1-8040"))
    )
    (comp (ref "U7")
      (value "24LC32A")
      (footprint "eagle-import:SOT23-5")
      (libsource (lib "eagle-import") (part "MEM_24LC32_SOT23-5_SOT23-5_24LC"))
    )
    (comp (ref "C1")
      (value "10uF,10V")
      (footprint "eagle-import:805")
      (libsource (lib "eagle-import") (part "CAP_10UF_Y5V_10V_10%_0805_805_1"))
    )
    (comp (ref "C2")
      (value "10uF,10V")
      (footprint "eagle-import:805")
      (libsource (lib "eagle-import") (part "CAP_10UF_Y5V_10V_10%_0805_805_1"))
    )
    (comp (ref "C3")
      (value "0.1uf,6.3V")
      (footprint "eagle-import:402")
      (libsource (lib "eagle-import") (part "CAP_0.1UF_X5R_6.3V_20%_0201__40"))
    )
    (comp (ref "C4")
      (value "10uF,10V")
      (footprint "eagle-import:805")
      (libsource (lib "eagle-import") (part "CAP_10UF_Y5V_10V_10%_0805_805_1"))
    )
    (comp (ref "C7")
      (value "10uF,10V")
      (footprint "eagle-import:805")
      (libsource (lib "eagle-import") (part "CAP_10UF_Y5V_10V_10%_0805_805_1"))
    )
    (comp (ref "C8")
      (value "10uF,10V")
      (footprint "eagle-import:805")
      (libsource (lib "eagle-import") (part "CAP_10UF_Y5V_10V_10%_0805_805_1"))
    )
    (comp (ref "C9")
      (value "10uF,10V")
      (footprint "eagle-import:805")
      (libsource (lib "eagle-import") (part "CAP_10UF_Y5V_10V_10%_0805_805_1"))
    )
    (comp (ref "C10")
      (value "10uF,10V")
      (footprint "eagle-import:805")
      (libsource (lib "eagle-import") (part "CAP_10UF_Y5V_10V_10%_0805_805_1"))
    )
    (comp (ref "C11")
      (value "10uF,10V")
      (footprint "eagle-import:805")
      (libsource (lib "eagle-import") (part "CAP_10UF_Y5V_10V_10%_0805_805_1"))
    )
    (comp (ref "C12")
      (value "10uF,10V")
      (footprint "eagle-import:805")
      (libsource (lib "eagle-import") (part "CAP_10UF_Y5V_10V_10%_0805_805_1"))
    )
    (comp (ref "C13")
      (value "10uF,10V")
      (footprint "eagle-import:805")
      (libsource (lib "eagle-import") (part "CAP_10UF_Y5V_10V_10%_0805_805_1"))
    )
    (comp (ref "C14")
      (value "10uF,10V")
      (footprint "eagle-import:805")
      (libsource (lib "eagle-import") (part "CAP_10UF_Y5V_10V_10%_0805_805_1"))
    )
    (comp (ref "C15")
      (value "10uF,10V")
      (footprint "eagle-import:805")
      (libsource (lib "eagle-import") (part "CAP_10UF_Y5V_10V_10%_0805_805_1"))
    )
    (comp (ref "C16")
      (value "2.2uF,6.3V")
      (footprint "eagle-import:402")
      (libsource (lib "eagle-import") (part "CAP_2.2UF_X5R_6.3V_10%_0402_402"))
    )
    (comp (ref "C17")
      (value "2.2uF,6.3V")
      (footprint "eagle-import:402")
      (libsource (lib "eagle-import") (part "CAP_2.2UF_X5R_6.3V_10%_0402_402"))
    )
    (comp (ref "C18")
      (value "2.2uF,6.3V")
      (footprint "eagle-import:402")
      (libsource (lib "eagle-import") (part "CAP_2.2UF_X5R_6.3V_10%_0402_402"))
    )
    (comp (ref "C19")
      (value "470pF,6.3V")
      (footprint "eagle-import:402")
      (libsource (lib "eagle-import") (part "CAP_470PF_X7R_25V_10%_0402_402_"))
    )
    (comp (ref "C20")
      (value "0.1uf,6.3V")
      (footprint "eagle-import:402")
      (libsource (lib "eagle-import") (part "CAP_0.1UF_X5R_6.3V_20%_0201__40"))
    )
    (comp (ref "D1")
      (value "LTST-C191TBKT")
      (footprint "eagle-import:LED_0603")
      (libsource (lib "eagle-import") (part "LED_LTST-C150GKT_0_LED_0603_DIS"))
    )
    (comp (ref "L1")
      (value "LQM2HPN2R2MG0L")
      (footprint "eagle-import:2520")
      (libsource (lib "eagle-import") (part "IND_2.2UH_2.6A_10%_SMD_2520_LQM"))
    )
    (comp (ref "L2")
      (value "LQM2HPN2R2MG0L")
      (footprint "eagle-import:2520")
      (libsource (lib "eagle-import") (part "IND_2.2UH_2.6A_10%_SMD_2520_LQM"))
    )
    (comp (ref "L3")
      (value "LQM2HPN2R2MG0L")
      (footprint "eagle-import:2520")
      (libsource (lib "eagle-import") (part "IND_2.2UH_2.6A_10%_SMD_2520_LQM"))
    )
    (comp (ref "MTG1")
      (value "MHOLE")
      (footprint "eagle-import:MTGH200C125D_PL")
      (libsource (lib "eagle-import") (part "MHOLE_MTGH200C125D_PL_MHOLE"))
    )
    (comp (ref "MTG2")
      (value "MHOLE")
      (footprint "eagle-import:MTGH200C125D_PL")
      (libsource (lib "eagle-import") (part "MHOLE_MTGH200C125D_PL_MHOLE"))
    )
    (comp (ref "MTG3")
      (value "MHOLE")
      (footprint "eagle-import:MTGH200C125D_PL")
      (libsource (lib "eagle-import") (part "MHOLE_MTGH200C125D_PL_MHOLE"))
    )
    (comp (ref "MTG4")
      (value "MHOLE")
      (footprint "eagle-import:MTGH200C125D_PL")
      (libsource (lib "eagle-import") (part "MHOLE_MTGH200C125D_PL_MHOLE"))
    )
    (comp (ref "P1")
      (value "PJ-200A")
      (footprint "eagle-import:CONN3-PWR-PJ102A")
      (libsource (lib "eagle-import") (part "POWER_JACK_CONN3-PWR-PJ102A_PJ-"))
    )
    (comp (ref "R1")
      (value "100K,1%")
      (footprint "eagle-import:402")
      (libsource (lib "eagle-import") (part "RES_100K_1/16W_1%_0402_402_100K"))
    )
    (comp (ref "R3")
      (value "1.5K,1%")
      (footprint "eagle-import:402")
      (libsource (lib "eagle-import") (part "RES_1.5K_1/16W_5%_0402_402_1.5K"))
    )
    (comp (ref "R4")
      (value "1.5K,1%")
      (footprint "eagle-import:402")
      (libsource (lib "eagle-import") (part "RES_1.5K_1/16W_5%_0402_402_1.5K"))
    )
    (comp (ref "R5")
      (value "0,1%")
      (footprint "eagle-import:402")
      (libsource (lib "eagle-import") (part "RES_4.75K_1/16W_1%_0402_402_0_1"))
    )
    (comp (ref "R6")
      (value "0,1%")
      (footprint "eagle-import:402")
      (libsource (lib "eagle-import") (part "RES_4.75K_1/16W_1%_0402_402_0_1"))
    )
    (comp (ref "R7")
      (value "0,1%")
      (footprint "eagle-import:402")
      (libsource (lib "eagle-import") (part "RES_4.75K_1/16W_1%_0402_402_0_1"))
    )
    (comp (ref "R8")
      (value "0,DNI")
      (footprint "eagle-import:402")
      (libsource (lib "eagle-import") (part "RES_4.75K_1/16W_1%_0402_402_0_D"))
    )
    (comp (ref "R9")
      (value "0,1%")
      (footprint "eagle-import:402")
      (libsource (lib "eagle-import") (part "RES_4.75K_1/16W_1%_0402_402_0_1"))
    )
    (comp (ref "R10")
      (value "470K,1%")
      (footprint "eagle-import:402")
      (libsource (lib "eagle-import") (part "RES_470_1/10W_5%_0402_402_470K_"))
    )
    (comp (ref "R11")
      (value "280K,1%")
      (footprint "eagle-import:402")
      (libsource (lib "eagle-import") (part "RES_470_1/10W_5%_0402_402_280K_"))
    )
    (comp (ref "R12")
      (value "820,5%")
      (footprint "eagle-import:402")
      (libsource (lib "eagle-import") (part "RES_470_1/10W_5%_0402_402_820_5_2"))
    )
    (comp (ref "S3")
      (value "KMR231GLFS")
      (footprint "eagle-import:SW4SMD_63X161LS")
      (libsource (lib "eagle-import") (part "SW_KT11P2JM_2_SW4SMD_63X161LS_D"))
    )
    (comp (ref "TP1")
      (value "TESTPT1")
      (footprint "eagle-import:TP1-8040")
      (libsource (lib "eagle-import") (part "TESTPT1_TP1-8040"))
    )
    (comp (ref "TP5")
      (value "TESTPT1")
      (footprint "eagle-import:TP60C33D")
      (libsource (lib "eagle-import") (part "TESTPT1_TP60C33D"))
    )
    (comp (ref "TP6")
      (value "TESTPT1")
      (footprint "eagle-import:TP60C33D")
      (libsource (lib "eagle-import") (part "TESTPT1_TP60C33D"))
    )
    (comp (ref "TP7")
      (value "TESTPT1")
      (footprint "eagle-import:TP60C33D")
      (libsource (lib "eagle-import") (part "TESTPT1_TP60C33D"))
    )
    (comp (ref "TP8")
      (value "TESTPT1")
      (footprint "eagle-import:TP60C33D")
      (libsource (lib "eagle-import") (part "TESTPT1_TP60C33D"))
    )
    (comp (ref "U2")
      (value "TPS65217C")
      (footprint "eagle-import:U_48_RSL")
      (libsource (lib "eagle-import") (part "PWR_TPS65217_2_U_48_RSL_TPS6521"))
    )
    (comp (ref "U4")
      (value "TL5209")
      (footprint "eagle-import:SO8-25X75")
      (libsource (lib "eagle-import") (part "PWR_TLV70233DBV_0_SO8-25X75_TL5"))
    )
    (comp (ref "C21")
      (value "18pF,50V")
      (footprint "eagle-import:402")
      (libsource (lib "eagle-import") (part "CAP_18PF_COG_50V_5%_0402_402_18"))
    )
    (comp (ref "C22")
      (value "18pF,50V")
      (footprint "eagle-import:402")
      (libsource (lib "eagle-import") (part "CAP_18PF_COG_50V_5%_0402_402_18"))
    )
    (comp (ref "C24")
      (value "1uF,10V")
      (footprint "eagle-import:402")
      (libsource (lib "eagle-import") (part "CAP_1.0UF_X5R_10V_10%_0402_402_"))
    )
    (comp (ref "C25")
      (value "18pF,50V")
      (footprint "eagle-import:402")
      (libsource (lib "eagle-import") (part "CAP_18PF_COG_50V_5%_0402_402_18"))
    )
    (comp (ref "C26")
      (value "18pF,50V")
      (footprint "eagle-import:402")
      (libsource (lib "eagle-import") (part "CAP_18PF_COG_50V_5%_0402_402_18"))
    )
    (comp (ref "C27")
      (value "0.1uf,6.3V")
      (footprint "eagle-import:402")
      (libsource (lib "eagle-import") (part "CAP_0.1UF_X5R_6.3V_20%_0201__40"))
    )
    (comp (ref "C28")
      (value "0.1uf,6.3V")
      (footprint "eagle-import:402")
      (libsource (lib "eagle-import") (part "CAP_0.1UF_X5R_6.3V_20%_0201__40"))
    )
    (comp (ref "C29")
      (value "0.1uf,6.3V")
      (footprint "eagle-import:402")
      (libsource (lib "eagle-import") (part "CAP_0.1UF_X5R_6.3V_20%_0201__40"))
    )
    (comp (ref "C30")
      (value "0.1uf,6.3V")
      (footprint "eagle-import:402")
      (libsource (lib "eagle-import") (part "CAP_0.1UF_X5R_6.3V_20%_0201__40"))
    )
    (comp (ref "C158")
      (value "0.1uf,6.3V")
      (footprint "eagle-import:402")
      (libsource (lib "eagle-import") (part "CAP_0.1UF_X5R_6.3V_20%_0201__40"))
    )
    (comp (ref "C159")
      (value "0.1uf,6.3V")
      (footprint "eagle-import:402")
      (libsource (lib "eagle-import") (part "CAP_0.1UF_X5R_6.3V_20%_0201__40"))
    )
    (comp (ref "P2")
      (value "CTI JTAG,DNI")
      (footprint "eagle-import:HEADER10X2_SMD")
      (libsource (lib "eagle-import") (part "HDR_10X2_CJTAG_0_HEADER10X2_SMD"))
    )
    (comp (ref "R14")
      (value "10K,1%")
      (footprint "eagle-import:402")
      (libsource (lib "eagle-import") (part "RES_10K_1/16W_1%_0402_402_10K_1"))
    )
    (comp (ref "R17")
      (value "1M,1%")
      (footprint "eagle-import:402")
      (libsource (lib "eagle-import") (part "RES_1M_1/16W_1%_0402_402_1M_1%"))
    )
    (comp (ref "R18")
      (value "33")
      (footprint "eagle-import:0402")
      (libsource (lib "eagle-import") (part "RES_33_0402_0402_33"))
    )
    (comp (ref "R19")
      (value "0,1%")
      (footprint "eagle-import:402")
      (libsource (lib "eagle-import") (part "RES_0_1/16W_1%_0402_402_0_1%"))
    )
    (comp (ref "R20")
      (value "0,1%")
      (footprint "eagle-import:402")
      (libsource (lib "eagle-import") (part "RES_0_1/16W_1%_0402_402_0_1%"))
    )
    (comp (ref "R21")
      (value "33")
      (footprint "eagle-import:0402")
      (libsource (lib "eagle-import") (part "RES_33_0402_0402_33"))
    )
    (comp (ref "R22")
      (value "49.9,1%")
      (footprint "eagle-import:402")
      (libsource (lib "eagle-import") (part "RES_4.7K_0402_402_49.9_1%"))
    )
    (comp (ref "R23")
      (value "4.75K,1%")
      (footprint "eagle-import:402")
      (libsource (lib "eagle-import") (part "RES_4.75K_1/16W_1%_0402_402_4.7"))
    )
    (comp (ref "R24")
      (value "4.75K,1%")
      (footprint "eagle-import:402")
      (libsource (lib "eagle-import") (part "RES_4.75K_1/16W_1%_0402_402_4.7"))
    )
    (comp (ref "R25")
      (value "4.75K,1%")
      (footprint "eagle-import:402")
      (libsource (lib "eagle-import") (part "RES_4.75K_1/16W_1%_0402_402_4.7"))
    )
    (comp (ref "R160")
      (value "0,1%")
      (footprint "eagle-import:402")
      (libsource (lib "eagle-import") (part "RES_4.75K_1/16W_1%_0402_402_0_1"))
    )
    (comp (ref "R161")
      (value "0,1%")
      (footprint "eagle-import:402")
      (libsource (lib "eagle-import") (part "RES_4.75K_1/16W_1%_0402_402_0_1"))
    )
    (comp (ref "R162")
      (value "0,1%")
      (footprint "eagle-import:402")
      (libsource (lib "eagle-import") (part "RES_4.75K_1/16W_1%_0402_402_0_1"))
    )
    (comp (ref "R167")
      (value "33")
      (footprint "eagle-import:0402")
      (libsource (lib "eagle-import") (part "RES_33_0402_0402_33"))
    )
    (comp (ref "S1")
      (value "KMR231GLFS")
      (footprint "eagle-import:SW4SMD_63X161LS")
      (libsource (lib "eagle-import") (part "SW_KT11P2JM_2_SW4SMD_63X161LS_D"))
    )
    (comp (ref "U3")
      (value "SN74LVC1G06DCK")
      (footprint "eagle-import:DCK5_2P15X1P4")
      (libsource (lib "eagle-import") (part "IC_SN74LVC1G06DCK_0_DCK5_2P15X1"))
    )
    (comp (ref "U6")
      (value "SN74AUC1G74")
      (footprint "eagle-import:SOP8_DCT")
      (libsource (lib "eagle-import") (part "IC_SN74AUC1G74_SOP8_DCT_SN74AUC"))
    )
    (comp (ref "Y1")
      (value "32.768KHz MC-306")
      (footprint "eagle-import:XTAL4_126-216SMD")
      (libsource (lib "eagle-import") (part "CRYS_32_768KHZ_SMD32_1_XTAL4_12"))
    )
    (comp (ref "Y2")
      (value "24MHz")
      (footprint "eagle-import:XTAL150SMD_125X196")
      (libsource (lib "eagle-import") (part "CRYS_24MHZ_SCC_0_XTAL150SMD_125"))
    )
    (comp (ref "Y4")
      (value "24.576MHZ")
      (footprint "eagle-import:OSC4_61X65LS_79X98SMD")
      (libsource (lib "eagle-import") (part "OSC_12MHZ_1.3V_OSC4_61X65LS_79X"))
    )
    (comp (ref "C144")
      (value "2.2uF,6.3V")
      (footprint "eagle-import:402")
      (libsource (lib "eagle-import") (part "CAP_2.2UF_X5R_6.3V_10%_0402_402"))
    )
    (comp (ref "C145")
      (value "0.1uf,6.3V")
      (footprint "eagle-import:402")
      (libsource (lib "eagle-import") (part "CAP_0.1UF_X5R_6.3V_20%_0201__40"))
    )
    (comp (ref "C146")
      (value "2.2uF,6.3V")
      (footprint "eagle-import:402")
      (libsource (lib "eagle-import") (part "CAP_2.2UF_X5R_6.3V_10%_0402_402"))
    )
    (comp (ref "C147")
      (value "0.1uf,6.3V")
      (footprint "eagle-import:402")
      (libsource (lib "eagle-import") (part "CAP_0.1UF_X5R_6.3V_20%_0201__40"))
    )
    (comp (ref "C148")
      (value "2.2uF,6.3V")
      (footprint "eagle-import:402")
      (libsource (lib "eagle-import") (part "CAP_2.2UF_X5R_6.3V_10%_0402_402"))
    )
    (comp (ref "C149")
      (value "0.1uf,6.3V")
      (footprint "eagle-import:402")
      (libsource (lib "eagle-import") (part "CAP_0.1UF_X5R_6.3V_20%_0201__40"))
    )
    (comp (ref "C150")
      (value "0.1uf,6.3V")
      (footprint "eagle-import:402")
      (libsource (lib "eagle-import") (part "CAP_0.1UF_X5R_6.3V_20%_0201__40"))
    )
    (comp (ref "C151")
      (value "2.2uF,6.3V")
      (footprint "eagle-import:402")
      (libsource (lib "eagle-import") (part "CAP_2.2UF_X5R_6.3V_10%_0402_402"))
    )
    (comp (ref "C156")
      (value "47pf,6.3V")
      (footprint "eagle-import:402")
      (libsource (lib "eagle-import") (part "CAP_0.1UF_X5R_6.3V_20%_0201_1"))
    )
    (comp (ref "C157")
      (value "47pf,6.3V")
      (footprint "eagle-import:402")
      (libsource (lib "eagle-import") (part "CAP_0.1UF_X5R_6.3V_20%_0201_1"))
    )
    (comp (ref "C160")
      (value "47pf,6.3V")
      (footprint "eagle-import:402")
      (libsource (lib "eagle-import") (part "CAP_0.1UF_X5R_6.3V_20%_0201_1"))
    )
    (comp (ref "C161")
      (value "47pf,6.3V")
      (footprint "eagle-import:402")
      (libsource (lib "eagle-import") (part "CAP_0.1UF_X5R_6.3V_20%_0201_1"))
    )
    (comp (ref "C162")
      (value "47pf,6.3V")
      (footprint "eagle-import:402")
      (libsource (lib "eagle-import") (part "CAP_0.1UF_X5R_6.3V_20%_0201_1"))
    )
    (comp (ref "C163")
      (value "47pf,6.3V")
      (footprint "eagle-import:402")
      (libsource (lib "eagle-import") (part "CAP_0.1UF_X5R_6.3V_20%_0201_1"))
    )
    (comp (ref "C164")
      (value "47pf,6.3V")
      (footprint "eagle-import:402")
      (libsource (lib "eagle-import") (part "CAP_0.1UF_X5R_6.3V_20%_0201_1"))
    )
    (comp (ref "C165")
      (value "47pf,6.3V")
      (footprint "eagle-import:402")
      (libsource (lib "eagle-import") (part "CAP_0.1UF_X5R_6.3V_20%_0201_1"))
    )
    (comp (ref "C166")
      (value "47pf,6.3V")
      (footprint "eagle-import:402")
      (libsource (lib "eagle-import") (part "CAP_0.1UF_X5R_6.3V_20%_0201_1"))
    )
    (comp (ref "C167")
      (value "47pf,6.3V")
      (footprint "eagle-import:402")
      (libsource (lib "eagle-import") (part "CAP_0.1UF_X5R_6.3V_20%_0201_1"))
    )
    (comp (ref "C168")
      (value "47pf,6.3V")
      (footprint "eagle-import:402")
      (libsource (lib "eagle-import") (part "CAP_0.1UF_X5R_6.3V_20%_0201_1"))
    )
    (comp (ref "C169")
      (value "47pf,6.3V")
      (footprint "eagle-import:402")
      (libsource (lib "eagle-import") (part "CAP_0.1UF_X5R_6.3V_20%_0201_1"))
    )
    (comp (ref "C170")
      (value "47pf,6.3V")
      (footprint "eagle-import:402")
      (libsource (lib "eagle-import") (part "CAP_0.1UF_X5R_6.3V_20%_0201_1"))
    )
    (comp (ref "C171")
      (value "47pf,6.3V")
      (footprint "eagle-import:402")
      (libsource (lib "eagle-import") (part "CAP_0.1UF_X5R_6.3V_20%_0201_1"))
    )
    (comp (ref "C172")
      (value "47pf,6.3V")
      (footprint "eagle-import:402")
      (libsource (lib "eagle-import") (part "CAP_0.1UF_X5R_6.3V_20%_0201_1"))
    )
    (comp (ref "C173")
      (value "47pf,6.3V")
      (footprint "eagle-import:402")
      (libsource (lib "eagle-import") (part "CAP_0.1UF_X5R_6.3V_20%_0201_1"))
    )
    (comp (ref "D6")
      (value "IP4283CZ10-TT")
      (footprint "eagle-import:TSSOP10")
      (libsource (lib "eagle-import") (part "32CTQ030/TO_1_TSSOP10_IP4283CZ1"))
    )
    (comp (ref "D7")
      (value "IP4283CZ10-TT")
      (footprint "eagle-import:TSSOP10")
      (libsource (lib "eagle-import") (part "32CTQ030/TO_1_TSSOP10_IP4283CZ1"))
    )
    (comp (ref "D8")
      (value "RB751V40,115")
      (footprint "eagle-import:SOD323")
      (libsource (lib "eagle-import") (part "DIO_SR305_TH_0_SOD323_RB751V40_"))
    )
    (comp (ref "FB5")
      (value "150OHM800mA")
      (footprint "eagle-import:SM-7351-IND-0805")
      (libsource (lib "eagle-import") (part "FER_180_200_0805_SM-7351-IND-08"))
    )
    (comp (ref "P6")
      (value "10118241-001RLF")
      (footprint "eagle-import:CONN19_HDMI")
      (libsource (lib "eagle-import") (part "CONN_HDMI_TYPED_CONN19_HDMI_101"))
    )
    (comp (ref "R146")
      (value "1.5K,1%")
      (footprint "eagle-import:402")
      (libsource (lib "eagle-import") (part "RES_1.5K_1/16W_5%_0402_402_1.5K_2"))
    )
    (comp (ref "R147")
      (value "1.5K1%")
      (footprint "eagle-import:402")
      (libsource (lib "eagle-import") (part "RES_1.5K_1/16W_5%_0402_402_1._1"))
    )
    (comp (ref "R148")
      (value "10K,1%")
      (footprint "eagle-import:402")
      (libsource (lib "eagle-import") (part "RES_10K_1/16W_1%_0402_402_10K_1_2"))
    )
    (comp (ref "R149")
      (value "0,1%")
      (footprint "eagle-import:402")
      (libsource (lib "eagle-import") (part "RES_0_1/16W_1%_0402_402_0_1%_2"))
    )
    (comp (ref "R158")
      (value "10K,1%")
      (footprint "eagle-import:402")
      (libsource (lib "eagle-import") (part "RES_10K_1/16W_1%_0402_402_10K_1_2"))
    )
    (comp (ref "R166")
      (value "27K,1%")
      (footprint "eagle-import:402")
      (libsource (lib "eagle-import") (part "RES_22.6K_1/16W_1%_0402_402_27K"))
    )
    (comp (ref "RT1")
      (value "PTC_RXEF010")
      (footprint "eagle-import:POLYSW200-5638-310")
      (libsource (lib "eagle-import") (part "PTC_RXEF010_POLYSW200-5638-310_"))
    )
    (comp (ref "U11")
      (value "TDA19988")
      (footprint "eagle-import:QFN64S9X9P5")
      (libsource (lib "eagle-import") (part "IC_TDA19988_HVQFN64_5_QFN64S9X9"))
    )
    (comp (ref "C31")
      (value "0.1uf,6.3V")
      (footprint "eagle-import:402")
      (libsource (lib "eagle-import") (part "CAP_0.1UF_X5R_6.3V_20%_0201__40"))
    )
    (comp (ref "C32")
      (value "0.001uf,50V")
      (footprint "eagle-import:402")
      (libsource (lib "eagle-import") (part "CAP_0.001_X7R_50V_5%_0402_402_0"))
    )
    (comp (ref "C33")
      (value "0.1uf,6.3V")
      (footprint "eagle-import:402")
      (libsource (lib "eagle-import") (part "CAP_0.1UF_X5R_6.3V_20%_0201__40"))
    )
    (comp (ref "C34")
      (value "100uF,6.3V")
      (footprint "eagle-import:RD205SMD_250D")
      (libsource (lib "eagle-import") (part "CAP_100UF_TANT_6.3V_3528-21_RD2"))
    )
    (comp (ref "C35")
      (value "0.1uf,6.3V")
      (footprint "eagle-import:402")
      (libsource (lib "eagle-import") (part "CAP_0.1UF_X5R_6.3V_20%_0201__40"))
    )
    (comp (ref "C36")
      (value "0.1uf,6.3V")
      (footprint "eagle-import:402")
      (libsource (lib "eagle-import") (part "CAP_0.1UF_X5R_6.3V_20%_0201__40"))
    )
    (comp (ref "C155")
      (value "0.1uf,6.3V")
      (footprint "eagle-import:402")
      (libsource (lib "eagle-import") (part "CAP_0.1UF_X5R_6.3V_20%_0201__40"))
    )
    (comp (ref "FB7")
      (value "150OHM800mA")
      (footprint "eagle-import:SM-7351-IND-0805")
      (libsource (lib "eagle-import") (part "FER_180_200_0_SM-7351-IND-0805_"))
    )
    (comp (ref "FB8")
      (value "0.1 Ohm,0805")
      (footprint "eagle-import:SM-7351-IND-0805")
      (libsource (lib "eagle-import") (part "FER_180_200_0_SM-7351-IND-080_1"))
    )
    (comp (ref "J1")
      (value "HEADER 6")
      (footprint "eagle-import:SIP6")
      (libsource (lib "eagle-import") (part "HEADER_6_SIP6_HEADER_6"))
    )
    (comp (ref "P3")
      (value "87520-0010BLF")
      (footprint "eagle-import:USB_A_SH")
      (libsource (lib "eagle-import") (part "CONN_54819-0578_2_USB_A_SH_IO_8"))
    )
    (comp (ref "P4")
      (value "USB5MINI")
      (footprint "eagle-import:USB5MINI_4SHIELDED_SMD-5")
      (libsource (lib "eagle-import") (part "MINI-USB-AB-SOCKET_USB5MINI_4SH"))
    )
    (comp (ref "R26")
      (value "4.75K,1%")
      (footprint "eagle-import:402")
      (libsource (lib "eagle-import") (part "RES_4.75K_1/16W_1%_0402_402_4.7"))
    )
    (comp (ref "R27")
      (value "0,1%")
      (footprint "eagle-import:402")
      (libsource (lib "eagle-import") (part "RES_0_1/16W_1%_0402_402_0_1%"))
    )
    (comp (ref "R28")
      (value "33")
      (footprint "eagle-import:0402")
      (libsource (lib "eagle-import") (part "RES_33_0402_0402_33"))
    )
    (comp (ref "R45")
      (value "33")
      (footprint "eagle-import:0402")
      (libsource (lib "eagle-import") (part "RES_33_0402_0402_33"))
    )
    (comp (ref "R46")
      (value "33")
      (footprint "eagle-import:0402")
      (libsource (lib "eagle-import") (part "RES_33_0402_0402_33"))
    )
    (comp (ref "R47")
      (value "33")
      (footprint "eagle-import:0402")
      (libsource (lib "eagle-import") (part "RES_33_0402_0402_33"))
    )
    (comp (ref "R48")
      (value "33")
      (footprint "eagle-import:0402")
      (libsource (lib "eagle-import") (part "RES_33_0402_0402_33"))
    )
    (comp (ref "R49")
      (value "0,1%")
      (footprint "eagle-import:402")
      (libsource (lib "eagle-import") (part "RES_100K_1/16W_1%_0402_402_0_1%"))
    )
    (comp (ref "R50")
      (value "0,1%")
      (footprint "eagle-import:402")
      (libsource (lib "eagle-import") (part "RES_4.75K_1/16W_1%_0402_402_0_1"))
    )
    (comp (ref "R51")
      (value "0,1%")
      (footprint "eagle-import:402")
      (libsource (lib "eagle-import") (part "RES_4.75K_1/16W_1%_0402_402_0_1"))
    )
    (comp (ref "R52")
      (value "10K,1%")
      (footprint "eagle-import:402")
      (libsource (lib "eagle-import") (part "RES_10K_1/16W_1%_0402_402_10K_1"))
    )
    (comp (ref "R53")
      (value "10K,1%")
      (footprint "eagle-import:402")
      (libsource (lib "eagle-import") (part "RES_10K_1/16W_1%_0402_402_10K_1"))
    )
    (comp (ref "R159")
      (value "0,1%")
      (footprint "eagle-import:402")
      (libsource (lib "eagle-import") (part "RES_4.75K_1/16W_1%_0402_402_0_1"))
    )
    (comp (ref "R163")
      (value "4.75K,1%")
      (footprint "eagle-import:402")
      (libsource (lib "eagle-import") (part "RES_4.75K_1/16W_1%_0402_402_4.7"))
    )
    (comp (ref "R164")
      (value "4.75K,1%")
      (footprint "eagle-import:402")
      (libsource (lib "eagle-import") (part "RES_4.75K_1/16W_1%_0402_402_4.7"))
    )
    (comp (ref "R165")
      (value "100K,1%")
      (footprint "eagle-import:402")
      (libsource (lib "eagle-import") (part "RES_100K_1/16W_1%_0402_402_100K"))
    )
    (comp (ref "U8")
      (value "TPS2051 (DGN)")
      (footprint "eagle-import:DGN-16X60")
      (libsource (lib "eagle-import") (part "TPS2061_1_DGN-16X60_TPS2051__DG"))
    )
    (comp (ref "U9")
      (value "TPD4S012")
      (footprint "eagle-import:U_6_DRY")
      (libsource (lib "eagle-import") (part "PROT_TPD4S012_U_6_DRY_TPD4S012"))
    )
    (comp (ref "U10")
      (value "TPD4S012")
      (footprint "eagle-import:U_6_DRY")
      (libsource (lib "eagle-import") (part "PROT_TPD4S012_U_6_DRY_TPD4S012"))
    )
    (comp (ref "U15")
      (value "SN74LVC2G241")
      (footprint "eagle-import:U_8_DCU")
      (libsource (lib "eagle-import") (part "IC_SN74LVC2G241_1_U_8_DCU_SN74L"))
    )
    (comp (ref "C125")
      (value "2.2uF,6.3V")
      (footprint "eagle-import:402")
      (libsource (lib "eagle-import") (part "CAP_2.2UF_X5R_6.3V_10%_0402_402"))
    )
    (comp (ref "C126")
      (value "10uF,10V")
      (footprint "eagle-import:805")
      (libsource (lib "eagle-import") (part "CAP_10UF_Y5V_10V_10%_0805_805_1"))
    )
    (comp (ref "C127")
      (value "0.1uf,6.3V")
      (footprint "eagle-import:402")
      (libsource (lib "eagle-import") (part "CAP_0.1UF_X5R_6.3V_20%_0201__40"))
    )
    (comp (ref "C128")
      (value "0.1uf,6.3V")
      (footprint "eagle-import:402")
      (libsource (lib "eagle-import") (part "CAP_0.1UF_X5R_6.3V_20%_0201__40"))
    )
    (comp (ref "C129")
      (value "0.1uf,6.3V")
      (footprint "eagle-import:402")
      (libsource (lib "eagle-import") (part "CAP_0.1UF_X5R_6.3V_20%_0201__40"))
    )
    (comp (ref "C130")
      (value "0.1uf,6.3V")
      (footprint "eagle-import:402")
      (libsource (lib "eagle-import") (part "CAP_0.1UF_X5R_6.3V_20%_0201__40"))
    )
    (comp (ref "R101")
      (value "10K,1%")
      (footprint "eagle-import:402")
      (libsource (lib "eagle-import") (part "RES_10K_1/16W_1%_0402_402_10K_1"))
    )
    (comp (ref "R102")
      (value "10K,1%")
      (footprint "eagle-import:402")
      (libsource (lib "eagle-import") (part "RES_10K_1/16W_1%_0402_402_10K_1"))
    )
    (comp (ref "R103")
      (value "10K,1%")
      (footprint "eagle-import:402")
      (libsource (lib "eagle-import") (part "RES_10K_1/16W_1%_0402_402_10K_1"))
    )
    (comp (ref "R104")
      (value "10K,1%")
      (footprint "eagle-import:402")
      (libsource (lib "eagle-import") (part "RES_10K_1/16W_1%_0402_402_10K_1"))
    )
    (comp (ref "R105")
      (value "10K,1%")
      (footprint "eagle-import:402")
      (libsource (lib "eagle-import") (part "RES_10K_1/16W_1%_0402_402_10K_1"))
    )
    (comp (ref "R106")
      (value "10K,1%")
      (footprint "eagle-import:402")
      (libsource (lib "eagle-import") (part "RES_10K_1/16W_1%_0402_402_10K_1"))
    )
    (comp (ref "R107")
      (value "10K,1%")
      (footprint "eagle-import:402")
      (libsource (lib "eagle-import") (part "RES_10K_1/16W_1%_0402_402_10K_1"))
    )
    (comp (ref "R108")
      (value "10K,1%")
      (footprint "eagle-import:402")
      (libsource (lib "eagle-import") (part "RES_10K_1/16W_1%_0402_402_10K_1"))
    )
    (comp (ref "R109")
      (value "10K,1%")
      (footprint "eagle-import:402")
      (libsource (lib "eagle-import") (part "RES_10K_1/16W_1%_0402_402_10K_1"))
    )
    (comp (ref "R110")
      (value "10K,1%")
      (footprint "eagle-import:402")
      (libsource (lib "eagle-import") (part "RES_10K_1/16W_1%_0402_402_10K_1"))
    )
    (comp (ref "R111")
      (value "10K,1%")
      (footprint "eagle-import:402")
      (libsource (lib "eagle-import") (part "RES_10K_1/16W_1%_0402_402_10K_1"))
    )
    (comp (ref "U13")
      (value "MEM_MNAND_2GB")
      (footprint "eagle-import:BGA153_P14_P5_11P5X13")
      (libsource (lib "eagle-import") (part "MEM_MNAND_2GB_BGA153_P14_P5_11P"))
    )
    (comp (ref "C107")
      (value "0.1uf,6.3V")
      (footprint "eagle-import:402")
      (libsource (lib "eagle-import") (part "CAP_0.1UF_X5R_6.3V_20%_0201__40"))
    )
    (comp (ref "C108")
      (value "0.1uf,6.3V")
      (footprint "eagle-import:402")
      (libsource (lib "eagle-import") (part "CAP_0.1UF_X5R_6.3V_20%_0201__40"))
    )
    (comp (ref "C109")
      (value "0.1uf,6.3V")
      (footprint "eagle-import:402")
      (libsource (lib "eagle-import") (part "CAP_0.1UF_X5R_6.3V_20%_0201__40"))
    )
    (comp (ref "C110")
      (value "0.1uf,6.3V")
      (footprint "eagle-import:402")
      (libsource (lib "eagle-import") (part "CAP_0.1UF_X5R_6.3V_20%_0201__40"))
    )
    (comp (ref "C111")
      (value "0.1uf,6.3V")
      (footprint "eagle-import:402")
      (libsource (lib "eagle-import") (part "CAP_0.1UF_X5R_6.3V_20%_0201__40"))
    )
    (comp (ref "C112")
      (value "0.1uf,6.3V")
      (footprint "eagle-import:402")
      (libsource (lib "eagle-import") (part "CAP_0.1UF_X5R_6.3V_20%_0201__40"))
    )
    (comp (ref "C113")
      (value "0.1uf,6.3V")
      (footprint "eagle-import:402")
      (libsource (lib "eagle-import") (part "CAP_0.1UF_X5R_6.3V_20%_0201__40"))
    )
    (comp (ref "C114")
      (value "0.1uf,6.3V")
      (footprint "eagle-import:402")
      (libsource (lib "eagle-import") (part "CAP_0.1UF_X5R_6.3V_20%_0201__40"))
    )
    (comp (ref "C115")
      (value "0.1uf,6.3V")
      (footprint "eagle-import:402")
      (libsource (lib "eagle-import") (part "CAP_0.1UF_X5R_6.3V_20%_0201__40"))
    )
    (comp (ref "C116")
      (value "0.1uf,6.3V")
      (footprint "eagle-import:402")
      (libsource (lib "eagle-import") (part "CAP_0.1UF_X5R_6.3V_20%_0201__40"))
    )
    (comp (ref "C117")
      (value "0.1uf,6.3V")
      (footprint "eagle-import:402")
      (libsource (lib "eagle-import") (part "CAP_0.1UF_X5R_6.3V_20%_0201__40"))
    )
    (comp (ref "C118")
      (value "10uF,10V")
      (footprint "eagle-import:805")
      (libsource (lib "eagle-import") (part "CAP_10UF_Y5V_10V_10%_0805_805_1"))
    )
    (comp (ref "C119")
      (value "0.1uf,6.3V")
      (footprint "eagle-import:402")
      (libsource (lib "eagle-import") (part "CAP_0.1UF_X5R_6.3V_20%_0201__40"))
    )
    (comp (ref "C120")
      (value "0.1uf,6.3V")
      (footprint "eagle-import:402")
      (libsource (lib "eagle-import") (part "CAP_0.1UF_X5R_6.3V_20%_0201__40"))
    )
    (comp (ref "C121")
      (value "0.1uf,6.3V")
      (footprint "eagle-import:402")
      (libsource (lib "eagle-import") (part "CAP_0.1UF_X5R_6.3V_20%_0201__40"))
    )
    (comp (ref "C122")
      (value "10uF,10V")
      (footprint "eagle-import:805")
      (libsource (lib "eagle-import") (part "CAP_10UF_Y5V_10V_10%_0805_805_1"))
    )
    (comp (ref "C123")
      (value "0.001uf,50V")
      (footprint "eagle-import:402")
      (libsource (lib "eagle-import") (part "CAP_0.001_X7R_50V_5%_0402_402_0"))
    )
    (comp (ref "C124")
      (value "0.1uf,6.3V")
      (footprint "eagle-import:402")
      (libsource (lib "eagle-import") (part "CAP_0.1UF_X5R_6.3V_20%_0201__40"))
    )
    (comp (ref "R96")
      (value "10K,1%")
      (footprint "eagle-import:402")
      (libsource (lib "eagle-import") (part "RES_10K_1/16W_1%_0402_402_10K_1_2"))
    )
    (comp (ref "R97")
      (value "1.5K,1%")
      (footprint "eagle-import:402")
      (libsource (lib "eagle-import") (part "RES_10K_1/16W_1%_0402_402_1.5K_"))
    )
    (comp (ref "R98")
      (value "10K,1%")
      (footprint "eagle-import:402")
      (libsource (lib "eagle-import") (part "RES_10K_1/16W_1%_0402_402_10K_1"))
    )
    (comp (ref "R99")
      (value "240")
      (footprint "eagle-import:SM-7351-RES-0402")
      (libsource (lib "eagle-import") (part "RES_SM-7351-RES-0402_240"))
    )
    (comp (ref "R100")
      (value "10K,1%")
      (footprint "eagle-import:402")
      (libsource (lib "eagle-import") (part "RES_10K_1/16W_1%_0402_402_10K_1"))
    )
    (comp (ref "U12")
      (value "MT41K256M16HA -125:E")
      (footprint "eagle-import:BGA96_T9_P8_9X14")
      (libsource (lib "eagle-import") (part "MT47H256M8_7_BGA96_T9_P8_9X14_M"))
    )
  )
  (nets
    (net (code "1") (name "12MHZ") (class "Default")
      (node (ref "R21") (pin "2") (pinfunction "2_2") (pintype "bidirectional"))
      (node (ref "U11") (pin "27") (pinfunction "59_27") (pintype "bidirectional"))
    )
    (net (code "2") (name "AIN0") (class "Default")
      (node (ref "P9") (pin "39") (pinfunction "43_39") (pintype "bidirectional"))
      (node (ref "U5") (pin "B6") (pinfunction "1_B6") (pintype "bidirectional"))
    )
    (net (code "3") (name "AIN1") (class "Default")
      (node (ref "P9") (pin "40") (pinfunction "20_40") (pintype "bidirectional"))
      (node (ref "U5") (pin "C7") (pinfunction "2_C7") (pintype "bidirectional"))
    )
    (net (code "4") (name "AIN2") (class "Default")
      (node (ref "P9") (pin "37") (pinfunction "42_37") (pintype "bidirectional"))
      (node (ref "U5") (pin "B7") (pinfunction "3_B7") (pintype "bidirectional"))
    )
    (net (code "5") (name "AIN3") (class "Default")
      (node (ref "P9") (pin "38") (pinfunction "19_38") (pintype "bidirectional"))
      (node (ref "U5") (pin "A7") (pinfunction "4_A7") (pintype "bidirectional"))
    )
    (net (code "6") (name "AIN4") (class "Default")
      (node (ref "P9") (pin "33") (pinfunction "40_33") (pintype "bidirectional"))
      (node (ref "U5") (pin "C8") (pinfunction "5_C8") (pintype "bidirectional"))
    )
    (net (code "7") (name "AIN5") (class "Default")
      (node (ref "P9") (pin "36") (pinfunction "18_36") (pintype "bidirectional"))
      (node (ref "U5") (pin "B8") (pinfunction "6_B8") (pintype "bidirectional"))
    )
    (net (code "8") (name "AIN6") (class "Default")
      (node (ref "P9") (pin "35") (pinfunction "41_35") (pintype "bidirectional"))
      (node (ref "U5") (pin "A8") (pinfunction "7_A8") (pintype "bidirectional"))
    )
    (net (code "9") (name "CLKOUT2") (class "Default")
      (node (ref "P2") (pin "18") (pinfunction "19_18") (pintype "bidirectional"))
      (node (ref "P9") (pin "41") (pinfunction "44_41") (pintype "bidirectional"))
      (node (ref "R19") (pin "2") (pinfunction "2_2") (pintype "bidirectional"))
      (node (ref "R20") (pin "1") (pinfunction "1_1") (pintype "bidirectional"))
    )
    (net (code "10") (name "DDR_A0") (class "Default")
      (node (ref "U12") (pin "N3") (pinfunction "8_N3") (pintype "bidirectional"))
      (node (ref "U5") (pin "F3") (pinfunction "61_F3") (pintype "bidirectional"))
    )
    (net (code "11") (name "DDR_A1") (class "Default")
      (node (ref "U12") (pin "P7") (pinfunction "9_P7") (pintype "bidirectional"))
      (node (ref "U5") (pin "H1") (pinfunction "62_H1") (pintype "bidirectional"))
    )
    (net (code "12") (name "DDR_A2") (class "Default")
      (node (ref "U12") (pin "P3") (pinfunction "10_P3") (pintype "bidirectional"))
      (node (ref "U5") (pin "E4") (pinfunction "63_E4") (pintype "bidirectional"))
    )
    (net (code "13") (name "DDR_A3") (class "Default")
      (node (ref "U12") (pin "N2") (pinfunction "11_N2") (pintype "bidirectional"))
      (node (ref "U5") (pin "C3") (pinfunction "64_C3") (pintype "bidirectional"))
    )
    (net (code "14") (name "DDR_A4") (class "Default")
      (node (ref "U12") (pin "P8") (pinfunction "12_P8") (pintype "bidirectional"))
      (node (ref "U5") (pin "C2") (pinfunction "65_C2") (pintype "bidirectional"))
    )
    (net (code "15") (name "DDR_A5") (class "Default")
      (node (ref "U12") (pin "P2") (pinfunction "13_P2") (pintype "bidirectional"))
      (node (ref "U5") (pin "B1") (pinfunction "66_B1") (pintype "bidirectional"))
    )
    (net (code "16") (name "DDR_A6") (class "Default")
      (node (ref "U12") (pin "R8") (pinfunction "14_R8") (pintype "bidirectional"))
      (node (ref "U5") (pin "D5") (pinfunction "67_D5") (pintype "bidirectional"))
    )
    (net (code "17") (name "DDR_A7") (class "Default")
      (node (ref "U12") (pin "R2") (pinfunction "15_R2") (pintype "bidirectional"))
      (node (ref "U5") (pin "E2") (pinfunction "68_E2") (pintype "bidirectional"))
    )
    (net (code "18") (name "DDR_A8") (class "Default")
      (node (ref "U12") (pin "T8") (pinfunction "16_T8") (pintype "bidirectional"))
      (node (ref "U5") (pin "D4") (pinfunction "69_D4") (pintype "bidirectional"))
    )
    (net (code "19") (name "DDR_A9") (class "Default")
      (node (ref "U12") (pin "R3") (pinfunction "17_R3") (pintype "bidirectional"))
      (node (ref "U5") (pin "C1") (pinfunction "70_C1") (pintype "bidirectional"))
    )
    (net (code "20") (name "DDR_A10") (class "Default")
      (node (ref "U12") (pin "L7") (pinfunction "18_L7") (pintype "bidirectional"))
      (node (ref "U5") (pin "F4") (pinfunction "71_F4") (pintype "bidirectional"))
    )
    (net (code "21") (name "DDR_A11") (class "Default")
      (node (ref "U12") (pin "R7") (pinfunction "19_R7") (pintype "bidirectional"))
      (node (ref "U5") (pin "F2") (pinfunction "72_F2") (pintype "bidirectional"))
    )
    (net (code "22") (name "DDR_A12") (class "Default")
      (node (ref "U12") (pin "N7") (pinfunction "20_N7") (pintype "bidirectional"))
      (node (ref "U5") (pin "E3") (pinfunction "73_E3") (pintype "bidirectional"))
    )
    (net (code "23") (name "DDR_A13") (class "Default")
      (node (ref "U12") (pin "T3") (pinfunction "21_T3") (pintype "bidirectional"))
      (node (ref "U5") (pin "H3") (pinfunction "74_H3") (pintype "bidirectional"))
    )
    (net (code "24") (name "DDR_A14") (class "Default")
      (node (ref "U12") (pin "T7") (pinfunction "22_T7") (pintype "bidirectional"))
      (node (ref "U5") (pin "H4") (pinfunction "75_H4") (pintype "bidirectional"))
    )
    (net (code "25") (name "DDR_A15") (class "Default")
      (node (ref "U12") (pin "M7") (pinfunction "84_M7") (pintype "bidirectional"))
      (node (ref "U5") (pin "D3") (pinfunction "115_D3") (pintype "bidirectional"))
    )
    (net (code "26") (name "DDR_BA0") (class "Default")
      (node (ref "U12") (pin "M2") (pinfunction "23_M2") (pintype "bidirectional"))
      (node (ref "U5") (pin "C4") (pinfunction "98_C4") (pintype "bidirectional"))
    )
    (net (code "27") (name "DDR_BA1") (class "Default")
      (node (ref "U12") (pin "N8") (pinfunction "24_N8") (pintype "bidirectional"))
      (node (ref "U5") (pin "E1") (pinfunction "99_E1") (pintype "bidirectional"))
    )
    (net (code "28") (name "DDR_BA2") (class "Default")
      (node (ref "U12") (pin "M3") (pinfunction "25_M3") (pintype "bidirectional"))
      (node (ref "U5") (pin "B3") (pinfunction "100_B3") (pintype "bidirectional"))
    )
    (net (code "29") (name "DDR_CASN") (class "Default")
      (node (ref "U12") (pin "K3") (pinfunction "6_K3") (pintype "bidirectional"))
      (node (ref "U5") (pin "F1") (pinfunction "95_F1") (pintype "bidirectional"))
    )
    (net (code "30") (name "DDR_CKE") (class "Default")
      (node (ref "R96") (pin "2") (pinfunction "2_2") (pintype "bidirectional"))
      (node (ref "U12") (pin "K9") (pinfunction "3_K9") (pintype "bidirectional"))
      (node (ref "U5") (pin "G3") (pinfunction "112_G3") (pintype "bidirectional"))
    )
    (net (code "31") (name "DDR_CLK") (class "Default")
      (node (ref "U12") (pin "J7") (pinfunction "1_J7") (pintype "bidirectional"))
      (node (ref "U5") (pin "D2") (pinfunction "92_D2") (pintype "bidirectional"))
    )
    (net (code "32") (name "DDR_CLKN") (class "Default")
      (node (ref "U12") (pin "K7") (pinfunction "2_K7") (pintype "bidirectional"))
      (node (ref "U5") (pin "D1") (pinfunction "93_D1") (pintype "bidirectional"))
    )
    (net (code "33") (name "DDR_CSN") (class "Default")
      (node (ref "U12") (pin "L2") (pinfunction "4_L2") (pintype "bidirectional"))
      (node (ref "U5") (pin "H2") (pinfunction "94_H2") (pintype "bidirectional"))
    )
    (net (code "34") (name "DDR_D0") (class "Default")
      (node (ref "U12") (pin "E3") (pinfunction "26_E3") (pintype "bidirectional"))
      (node (ref "U5") (pin "M3") (pinfunction "76_M3") (pintype "bidirectional"))
    )
    (net (code "35") (name "DDR_D1") (class "Default")
      (node (ref "U12") (pin "F7") (pinfunction "27_F7") (pintype "bidirectional"))
      (node (ref "U5") (pin "M4") (pinfunction "77_M4") (pintype "bidirectional"))
    )
    (net (code "36") (name "DDR_D2") (class "Default")
      (node (ref "U12") (pin "F2") (pinfunction "28_F2") (pintype "bidirectional"))
      (node (ref "U5") (pin "N1") (pinfunction "78_N1") (pintype "bidirectional"))
    )
    (net (code "37") (name "DDR_D3") (class "Default")
      (node (ref "U12") (pin "F8") (pinfunction "29_F8") (pintype "bidirectional"))
      (node (ref "U5") (pin "N2") (pinfunction "79_N2") (pintype "bidirectional"))
    )
    (net (code "38") (name "DDR_D4") (class "Default")
      (node (ref "U12") (pin "H3") (pinfunction "30_H3") (pintype "bidirectional"))
      (node (ref "U5") (pin "N3") (pinfunction "80_N3") (pintype "bidirectional"))
    )
    (net (code "39") (name "DDR_D5") (class "Default")
      (node (ref "U12") (pin "H8") (pinfunction "31_H8") (pintype "bidirectional"))
      (node (ref "U5") (pin "N4") (pinfunction "81_N4") (pintype "bidirectional"))
    )
    (net (code "40") (name "DDR_D6") (class "Default")
      (node (ref "U12") (pin "G2") (pinfunction "32_G2") (pintype "bidirectional"))
      (node (ref "U5") (pin "P3") (pinfunction "82_P3") (pintype "bidirectional"))
    )
    (net (code "41") (name "DDR_D7") (class "Default")
      (node (ref "U12") (pin "H7") (pinfunction "33_H7") (pintype "bidirectional"))
      (node (ref "U5") (pin "P4") (pinfunction "83_P4") (pintype "bidirectional"))
    )
    (net (code "42") (name "DDR_D8") (class "Default")
      (node (ref "U12") (pin "D7") (pinfunction "57_D7") (pintype "bidirectional"))
      (node (ref "U5") (pin "J1") (pinfunction "84_J1") (pintype "bidirectional"))
    )
    (net (code "43") (name "DDR_D9") (class "Default")
      (node (ref "U12") (pin "C3") (pinfunction "96_C3") (pintype "bidirectional"))
      (node (ref "U5") (pin "K1") (pinfunction "85_K1") (pintype "bidirectional"))
    )
    (net (code "44") (name "DDR_D10") (class "Default")
      (node (ref "U12") (pin "C8") (pinfunction "58_C8") (pintype "bidirectional"))
      (node (ref "U5") (pin "K2") (pinfunction "86_K2") (pintype "bidirectional"))
    )
    (net (code "45") (name "DDR_D11") (class "Default")
      (node (ref "U12") (pin "C2") (pinfunction "59_C2") (pintype "bidirectional"))
      (node (ref "U5") (pin "K3") (pinfunction "87_K3") (pintype "bidirectional"))
    )
    (net (code "46") (name "DDR_D12") (class "Default")
      (node (ref "U12") (pin "A7") (pinfunction "61_A7") (pintype "bidirectional"))
      (node (ref "U5") (pin "K4") (pinfunction "88_K4") (pintype "bidirectional"))
    )
    (net (code "47") (name "DDR_D13") (class "Default")
      (node (ref "U12") (pin "A2") (pinfunction "63_A2") (pintype "bidirectional"))
      (node (ref "U5") (pin "L3") (pinfunction "89_L3") (pintype "bidirectional"))
    )
    (net (code "48") (name "DDR_D14") (class "Default")
      (node (ref "U12") (pin "B8") (pinfunction "60_B8") (pintype "bidirectional"))
      (node (ref "U5") (pin "L4") (pinfunction "90_L4") (pintype "bidirectional"))
    )
    (net (code "49") (name "DDR_D15") (class "Default")
      (node (ref "U12") (pin "A3") (pinfunction "62_A3") (pintype "bidirectional"))
      (node (ref "U5") (pin "M1") (pinfunction "91_M1") (pintype "bidirectional"))
    )
    (net (code "50") (name "DDR_DQM0") (class "Default")
      (node (ref "U12") (pin "E7") (pinfunction "53_E7") (pintype "bidirectional"))
      (node (ref "U5") (pin "M2") (pinfunction "101_M2") (pintype "bidirectional"))
    )
    (net (code "51") (name "DDR_DQM1") (class "Default")
      (node (ref "U12") (pin "D3") (pinfunction "52_D3") (pintype "bidirectional"))
      (node (ref "U5") (pin "J2") (pinfunction "104_J2") (pintype "bidirectional"))
    )
    (net (code "52") (name "DDR_DQS0") (class "Default")
      (node (ref "U12") (pin "F3") (pinfunction "56_F3") (pintype "bidirectional"))
      (node (ref "U5") (pin "P1") (pinfunction "102_P1") (pintype "bidirectional"))
    )
    (net (code "53") (name "DDR_DQS1") (class "Default")
      (node (ref "U12") (pin "C7") (pinfunction "55_C7") (pintype "bidirectional"))
      (node (ref "U5") (pin "L1") (pinfunction "105_L1") (pintype "bidirectional"))
    )
    (net (code "54") (name "DDR_DQSN0") (class "Default")
      (node (ref "U12") (pin "G3") (pinfunction "54_G3") (pintype "bidirectional"))
      (node (ref "U5") (pin "P2") (pinfunction "103_P2") (pintype "bidirectional"))
    )
    (net (code "55") (name "DDR_DQSN1") (class "Default")
      (node (ref "U12") (pin "B7") (pinfunction "51_B7") (pintype "bidirectional"))
      (node (ref "U5") (pin "L2") (pinfunction "106_L2") (pintype "bidirectional"))
    )
    (net (code "56") (name "DDR_ODT") (class "Default")
      (node (ref "U12") (pin "K1") (pinfunction "34_K1") (pintype "bidirectional"))
      (node (ref "U5") (pin "G1") (pinfunction "107_G1") (pintype "bidirectional"))
    )
    (net (code "57") (name "DDR_RASN") (class "Default")
      (node (ref "U12") (pin "J3") (pinfunction "5_J3") (pintype "bidirectional"))
      (node (ref "U5") (pin "G4") (pinfunction "96_G4") (pintype "bidirectional"))
    )
    (net (code "58") (name "DDR_RESETN") (class "Default")
      (node (ref "R97") (pin "2") (pinfunction "2_2") (pintype "bidirectional"))
      (node (ref "U12") (pin "T2") (pinfunction "94_T2") (pintype "bidirectional"))
      (node (ref "U5") (pin "G2") (pinfunction "113_G2") (pintype "bidirectional"))
    )
    (net (code "59") (name "DDR_VREF") (class "Default")
      (node (ref "C123") (pin "1") (pinfunction "1_1") (pintype "bidirectional"))
      (node (ref "C124") (pin "1") (pinfunction "1_1") (pintype "bidirectional"))
      (node (ref "C28") (pin "1") (pinfunction "1_1") (pintype "bidirectional"))
      (node (ref "R100") (pin "1") (pinfunction "1_1") (pintype "bidirectional"))
      (node (ref "R98") (pin "2") (pinfunction "2_2") (pintype "bidirectional"))
      (node (ref "U12") (pin "H1") (pinfunction "71_H1") (pintype "bidirectional"))
      (node (ref "U12") (pin "M8") (pinfunction "85_M8") (pintype "bidirectional"))
      (node (ref "U5") (pin "J4") (pinfunction "117_J4") (pintype "bidirectional"))
    )
    (net (code "60") (name "DDR_WEN") (class "Default")
      (node (ref "U12") (pin "L3") (pinfunction "7_L3") (pintype "bidirectional"))
      (node (ref "U5") (pin "B2") (pinfunction "97_B2") (pintype "bidirectional"))
    )
    (net (code "61") (name "DGND") (class "Default")
      (node (ref "C1") (pin "1") (pinfunction "1_1") (pintype "bidirectional"))
      (node (ref "C10") (pin "1") (pinfunction "1_1") (pintype "bidirectional"))
      (node (ref "C100") (pin "2") (pinfunction "2_2") (pintype "bidirectional"))
      (node (ref "C101") (pin "2") (pinfunction "2_2") (pintype "bidirectional"))
      (node (ref "C102") (pin "2") (pinfunction "2_2") (pintype "bidirectional"))
      (node (ref "C103") (pin "2") (pinfunction "2_2") (pintype "bidirectional"))
      (node (ref "C104") (pin "2") (pinfunction "2_2") (pintype "bidirectional"))
      (node (ref "C105") (pin "2") (pinfunction "2_2") (pintype "bidirectional"))
      (node (ref "C106") (pin "2") (pinfunction "2_2") (pintype "bidirectional"))
      (node (ref "C107") (pin "2") (pinfunction "2_2") (pintype "bidirectional"))
      (node (ref "C108") (pin "2") (pinfunction "2_2") (pintype "bidirectional"))
      (node (ref "C109") (pin "2") (pinfunction "2_2") (pintype "bidirectional"))
      (node (ref "C11") (pin "1") (pinfunction "1_1") (pintype "bidirectional"))
      (node (ref "C110") (pin "2") (pinfunction "2_2") (pintype "bidirectional"))
      (node (ref "C111") (pin "2") (pinfunction "2_2") (pintype "bidirectional"))
      (node (ref "C112") (pin "2") (pinfunction "2_2") (pintype "bidirectional"))
      (node (ref "C113") (pin "2") (pinfunction "2_2") (pintype "bidirectional"))
      (node (ref "C114") (pin "2") (pinfunction "2_2") (pintype "bidirectional"))
      (node (ref "C115") (pin "2") (pinfunction "2_2") (pintype "bidirectional"))
      (node (ref "C116") (pin "2") (pinfunction "2_2") (pintype "bidirectional"))
      (node (ref "C117") (pin "2") (pinfunction "2_2") (pintype "bidirectional"))
      (node (ref "C118") (pin "1") (pinfunction "1_1") (pintype "bidirectional"))
      (node (ref "C119") (pin "2") (pinfunction "2_2") (pintype "bidirectional"))
      (node (ref "C12") (pin "1") (pinfunction "1_1") (pintype "bidirectional"))
      (node (ref "C120") (pin "2") (pinfunction "2_2") (pintype "bidirectional"))
      (node (ref "C121") (pin "2") (pinfunction "2_2") (pintype "bidirectional"))
      (node (ref "C122") (pin "1") (pinfunction "1_1") (pintype "bidirectional"))
      (node (ref "C123") (pin "2") (pinfunction "2_2") (pintype "bidirectional"))
      (node (ref "C124") (pin "2") (pinfunction "2_2") (pintype "bidirectional"))
      (node (ref "C125") (pin "2") (pinfunction "2_2") (pintype "bidirectional"))
      (node (ref "C126") (pin "1") (pinfunction "1_1") (pintype "bidirectional"))
      (node (ref "C127") (pin "2") (pinfunction "2_2") (pintype "bidirectional"))
      (node (ref "C128") (pin "2") (pinfunction "2_2") (pintype "bidirectional"))
      (node (ref "C129") (pin "2") (pinfunction "2_2") (pintype "bidirectional"))
      (node (ref "C13") (pin "1") (pinfunction "1_1") (pintype "bidirectional"))
      (node (ref "C130") (pin "2") (pinfunction "2_2") (pintype "bidirectional"))
      (node (ref "C131") (pin "2") (pinfunction "2_2") (pintype "bidirectional"))
      (node (ref "C132") (pin "2") (pinfunction "2_2") (pintype "bidirectional"))
      (node (ref "C133") (pin "1") (pinfunction "1_1") (pintype "bidirectional"))
      (node (ref "C134") (pin "2") (pinfunction "2_2") (pintype "bidirectional"))
      (node (ref "C135") (pin "2") (pinfunction "2_2") (pintype "bidirectional"))
      (node (ref "C136") (pin "2") (pinfunction "2_2") (pintype "bidirectional"))
      (node (ref "C137") (pin "2") (pinfunction "2_2") (pintype "bidirectional"))
      (node (ref "C138") (pin "2") (pinfunction "2_2") (pintype "bidirectional"))
      (node (ref "C139") (pin "2") (pinfunction "2_2") (pintype "bidirectional"))
      (node (ref "C14") (pin "1") (pinfunction "1_1") (pintype "bidirectional"))
      (node (ref "C140") (pin "2") (pinfunction "2_2") (pintype "bidirectional"))
      (node (ref "C141") (pin "2") (pinfunction "2_2") (pintype "bidirectional"))
      (node (ref "C142") (pin "2") (pinfunction "2_2") (pintype "bidirectional"))
      (node (ref "C143") (pin "2") (pinfunction "2_2") (pintype "bidirectional"))
      (node (ref "C144") (pin "2") (pinfunction "2_2") (pintype "bidirectional"))
      (node (ref "C145") (pin "2") (pinfunction "2_2") (pintype "bidirectional"))
      (node (ref "C146") (pin "2") (pinfunction "2_2") (pintype "bidirectional"))
      (node (ref "C147") (pin "2") (pinfunction "2_2") (pintype "bidirectional"))
      (node (ref "C148") (pin "2") (pinfunction "2_2") (pintype "bidirectional"))
      (node (ref "C149") (pin "2") (pinfunction "2_2") (pintype "bidirectional"))
      (node (ref "C15") (pin "1") (pinfunction "1_1") (pintype "bidirectional"))
      (node (ref "C150") (pin "2") (pinfunction "2_2") (pintype "bidirectional"))
      (node (ref "C151") (pin "2") (pinfunction "2_2") (pintype "bidirectional"))
      (node (ref "C152") (pin "2") (pinfunction "2_2") (pintype "bidirectional"))
      (node (ref "C153") (pin "2") (pinfunction "2_2") (pintype "bidirectional"))
      (node (ref "C154") (pin "2") (pinfunction "2_2") (pintype "bidirectional"))
      (node (ref "C155") (pin "1") (pinfunction "1_1") (pintype "bidirectional"))
      (node (ref "C156") (pin "2") (pinfunction "2_2") (pintype "bidirectional"))
      (node (ref "C157") (pin "2") (pinfunction "2_2") (pintype "bidirectional"))
      (node (ref "C158") (pin "2") (pinfunction "2_2") (pintype "bidirectional"))
      (node (ref "C159") (pin "2") (pinfunction "2_2") (pintype "bidirectional"))
      (node (ref "C16") (pin "2") (pinfunction "2_2") (pintype "bidirectional"))
      (node (ref "C160") (pin "2") (pinfunction "2_2") (pintype "bidirectional"))
      (node (ref "C161") (pin "2") (pinfunction "2_2") (pintype "bidirectional"))
      (node (ref "C162") (pin "2") (pinfunction "2_2") (pintype "bidirectional"))
      (node (ref "C163") (pin "2") (pinfunction "2_2") (pintype "bidirectional"))
      (node (ref "C164") (pin "2") (pinfunction "2_2") (pintype "bidirectional"))
      (node (ref "C165") (pin "2") (pinfunction "2_2") (pintype "bidirectional"))
      (node (ref "C166") (pin "2") (pinfunction "2_2") (pintype "bidirectional"))
      (node (ref "C167") (pin "2") (pinfunction "2_2") (pintype "bidirectional"))
      (node (ref "C168") (pin "2") (pinfunction "2_2") (pintype "bidirectional"))
      (node (ref "C169") (pin "2") (pinfunction "2_2") (pintype "bidirectional"))
      (node (ref "C17") (pin "2") (pinfunction "2_2") (pintype "bidirectional"))
      (node (ref "C170") (pin "2") (pinfunction "2_2") (pintype "bidirectional"))
      (node (ref "C171") (pin "2") (pinfunction "2_2") (pintype "bidirectional"))
      (node (ref "C172") (pin "2") (pinfunction "2_2") (pintype "bidirectional"))
      (node (ref "C173") (pin "2") (pinfunction "2_2") (pintype "bidirectional"))
      (node (ref "C18") (pin "2") (pinfunction "2_2") (pintype "bidirectional"))
      (node (ref "C19") (pin "2") (pinfunction "2_2") (pintype "bidirectional"))
      (node (ref "C2") (pin "1") (pinfunction "1_1") (pintype "bidirectional"))
      (node (ref "C20") (pin "2") (pinfunction "2_2") (pintype "bidirectional"))
      (node (ref "C24") (pin "2") (pinfunction "2_2") (pintype "bidirectional"))
      (node (ref "C27") (pin "2") (pinfunction "2_2") (pintype "bidirectional"))
      (node (ref "C28") (pin "2") (pinfunction "2_2") (pintype "bidirectional"))
      (node (ref "C29") (pin "2") (pinfunction "2_2") (pintype "bidirectional"))
      (node (ref "C3") (pin "1") (pinfunction "1_1") (pintype "bidirectional"))
      (node (ref "C30") (pin "2") (pinfunction "2_2") (pintype "bidirectional"))
      (node (ref "C34") (pin "2") (pinfunction "2_2") (pintype "bidirectional"))
      (node (ref "C35") (pin "2") (pinfunction "2_2") (pintype "bidirectional"))
      (node (ref "C36") (pin "2") (pinfunction "2_2") (pintype "bidirectional"))
      (node (ref "C37") (pin "2") (pinfunction "2_2") (pintype "bidirectional"))
      (node (ref "C38") (pin "2") (pinfunction "2_2") (pintype "bidirectional"))
      (node (ref "C39") (pin "1") (pinfunction "1_1") (pintype "bidirectional"))
      (node (ref "C4") (pin "1") (pinfunction "1_1") (pintype "bidirectional"))
      (node (ref "C40") (pin "1") (pinfunction "1_1") (pintype "bidirectional"))
      (node (ref "C41") (pin "2") (pinfunction "2_2") (pintype "bidirectional"))
      (node (ref "C42") (pin "2") (pinfunction "2_2") (pintype "bidirectional"))
      (node (ref "C43") (pin "2") (pinfunction "2_2") (pintype "bidirectional"))
      (node (ref "C44") (pin "2") (pinfunction "2_2") (pintype "bidirectional"))
      (node (ref "C45") (pin "2") (pinfunction "2_2") (pintype "bidirectional"))
      (node (ref "C46") (pin "2") (pinfunction "2_2") (pintype "bidirectional"))
      (node (ref "C47") (pin "2") (pinfunction "2_2") (pintype "bidirectional"))
      (node (ref "C48") (pin "2") (pinfunction "2_2") (pintype "bidirectional"))
      (node (ref "C49") (pin "2") (pinfunction "2_2") (pintype "bidirectional"))
      (node (ref "C50") (pin "2") (pinfunction "2_2") (pintype "bidirectional"))
      (node (ref "C51") (pin "2") (pinfunction "2_2") (pintype "bidirectional"))
      (node (ref "C52") (pin "2") (pinfunction "2_2") (pintype "bidirectional"))
      (node (ref "C53") (pin "2") (pinfunction "2_2") (pintype "bidirectional"))
      (node (ref "C54") (pin "2") (pinfunction "2_2") (pintype "bidirectional"))
      (node (ref "C55") (pin "1") (pinfunction "1_1") (pintype "bidirectional"))
      (node (ref "C56") (pin "1") (pinfunction "1_1") (pintype "bidirectional"))
      (node (ref "C57") (pin "1") (pinfunction "1_1") (pintype "bidirectional"))
      (node (ref "C58") (pin "2") (pinfunction "2_2") (pintype "bidirectional"))
      (node (ref "C59") (pin "2") (pinfunction "2_2") (pintype "bidirectional"))
      (node (ref "C60") (pin "1") (pinfunction "1_1") (pintype "bidirectional"))
      (node (ref "C61") (pin "1") (pinfunction "1_1") (pintype "bidirectional"))
      (node (ref "C62") (pin "1") (pinfunction "1_1") (pintype "bidirectional"))
      (node (ref "C63") (pin "2") (pinfunction "2_2") (pintype "bidirectional"))
      (node (ref "C64") (pin "2") (pinfunction "2_2") (pintype "bidirectional"))
      (node (ref "C65") (pin "2") (pinfunction "2_2") (pintype "bidirectional"))
      (node (ref "C66") (pin "2") (pinfunction "2_2") (pintype "bidirectional"))
      (node (ref "C67") (pin "2") (pinfunction "2_2") (pintype "bidirectional"))
      (node (ref "C68") (pin "1") (pinfunction "1_1") (pintype "bidirectional"))
      (node (ref "C69") (pin "1") (pinfunction "1_1") (pintype "bidirectional"))
      (node (ref "C7") (pin "1") (pinfunction "1_1") (pintype "bidirectional"))
      (node (ref "C70") (pin "1") (pinfunction "1_1") (pintype "bidirectional"))
      (node (ref "C71") (pin "1") (pinfunction "1_1") (pintype "bidirectional"))
      (node (ref "C72") (pin "1") (pinfunction "1_1") (pintype "bidirectional"))
      (node (ref "C73") (pin "1") (pinfunction "1_1") (pintype "bidirectional"))
      (node (ref "C74") (pin "1") (pinfunction "1_1") (pintype "bidirectional"))
      (node (ref "C75") (pin "1") (pinfunction "1_1") (pintype "bidirectional"))
      (node (ref "C76") (pin "1") (pinfunction "1_1") (pintype "bidirectional"))
      (node (ref "C77") (pin "2") (pinfunction "2_2") (pintype "bidirectional"))
      (node (ref "C78") (pin "2") (pinfunction "2_2") (pintype "bidirectional"))
      (node (ref "C79") (pin "2") (pinfunction "2_2") (pintype "bidirectional"))
      (node (ref "C8") (pin "1") (pinfunction "1_1") (pintype "bidirectional"))
      (node (ref "C80") (pin "2") (pinfunction "2_2") (pintype "bidirectional"))
      (node (ref "C81") (pin "2") (pinfunction "2_2") (pintype "bidirectional"))
      (node (ref "C82") (pin "2") (pinfunction "2_2") (pintype "bidirectional"))
      (node (ref "C83") (pin "2") (pinfunction "2_2") (pintype "bidirectional"))
      (node (ref "C84") (pin "2") (pinfunction "2_2") (pintype "bidirectional"))
      (node (ref "C85") (pin "2") (pinfunction "2_2") (pintype "bidirectional"))
      (node (ref "C86") (pin "2") (pinfunction "2_2") (pintype "bidirectional"))
      (node (ref "C87") (pin "2") (pinfunction "2_2") (pintype "bidirectional"))
      (node (ref "C88") (pin "2") (pinfunction "2_2") (pintype "bidirectional"))
      (node (ref "C89") (pin "2") (pinfunction "2_2") (pintype "bidirectional"))
      (node (ref "C9") (pin "1") (pinfunction "1_1") (pintype "bidirectional"))
      (node (ref "C90") (pin "2") (pinfunction "2_2") (pintype "bidirectional"))
      (node (ref "C91") (pin "2") (pinfunction "2_2") (pintype "bidirectional"))
      (node (ref "C92") (pin "2") (pinfunction "2_2") (pintype "bidirectional"))
      (node (ref "C94") (pin "2") (pinfunction "2_2") (pintype "bidirectional"))
      (node (ref "C95") (pin "1") (pinfunction "1_1") (pintype "bidirectional"))
      (node (ref "C96") (pin "1") (pinfunction "1_1") (pintype "bidirectional"))
      (node (ref "C97") (pin "2") (pinfunction "2_2") (pintype "bidirectional"))
      (node (ref "C98") (pin "2") (pinfunction "2_2") (pintype "bidirectional"))
      (node (ref "C99") (pin "2") (pinfunction "2_2") (pintype "bidirectional"))
      (node (ref "D6") (pin "3") (pinfunction "6_3") (pintype "bidirectional"))
      (node (ref "D6") (pin "8") (pinfunction "3_8") (pintype "bidirectional"))
      (node (ref "D7") (pin "3") (pinfunction "6_3") (pintype "bidirectional"))
      (node (ref "D7") (pin "8") (pinfunction "3_8") (pintype "bidirectional"))
      (node (ref "FB3") (pin "2") (pinfunction "2_2") (pintype "bidirectional"))
      (node (ref "J1") (pin "1") (pinfunction "1_1") (pintype "bidirectional"))
      (node (ref "P1") (pin "2") (pinfunction "3_2") (pintype "bidirectional"))
      (node (ref "P10") (pin "6") (pinfunction "6_6") (pintype "bidirectional"))
      (node (ref "P10") (pin "9") (pinfunction "9_9") (pintype "bidirectional"))
      (node (ref "P2") (pin "10") (pinfunction "15_10") (pintype "bidirectional"))
      (node (ref "P2") (pin "12") (pinfunction "16_12") (pintype "bidirectional"))
      (node (ref "P2") (pin "16") (pinfunction "18_16") (pintype "bidirectional"))
      (node (ref "P2") (pin "20") (pinfunction "20_20") (pintype "bidirectional"))
      (node (ref "P2") (pin "4") (pinfunction "12_4") (pintype "bidirectional"))
      (node (ref "P2") (pin "8") (pinfunction "14_8") (pintype "bidirectional"))
      (node (ref "P3") (pin "4") (pinfunction "4_4") (pintype "bidirectional"))
      (node (ref "P4") (pin "5") (pinfunction "7_5") (pintype "bidirectional"))
      (node (ref "P5") (pin "8") (pinfunction "11_8") (pintype "bidirectional"))
      (node (ref "P6") (pin "10") (pinfunction "8_10") (pintype "bidirectional"))
      (node (ref "P6") (pin "13") (pinfunction "12_13") (pintype "bidirectional"))
      (node (ref "P6") (pin "16") (pinfunction "17_16") (pintype "bidirectional"))
      (node (ref "P6") (pin "4") (pinfunction "3_4") (pintype "bidirectional"))
      (node (ref "P6") (pin "7") (pinfunction "5_7") (pintype "bidirectional"))
      (node (ref "P8") (pin "1") (pinfunction "24_1") (pintype "bidirectional"))
      (node (ref "P8") (pin "2") (pinfunction "1_2") (pintype "bidirectional"))
      (node (ref "P9") (pin "1") (pinfunction "24_1") (pintype "bidirectional"))
      (node (ref "P9") (pin "2") (pinfunction "1_2") (pintype "bidirectional"))
      (node (ref "P9") (pin "43") (pinfunction "45_43") (pintype "bidirectional"))
      (node (ref "P9") (pin "44") (pinfunction "22_44") (pintype "bidirectional"))
      (node (ref "P9") (pin "45") (pinfunction "46_45") (pintype "bidirectional"))
      (node (ref "P9") (pin "46") (pinfunction "23_46") (pintype "bidirectional"))
      (node (ref "Q1") (pin "1") (pinfunction "1_1") (pintype "bidirectional"))
      (node (ref "Q1") (pin "4") (pinfunction "1_4") (pintype "bidirectional"))
      (node (ref "Q2") (pin "1") (pinfunction "1_1") (pintype "bidirectional"))
      (node (ref "Q2") (pin "4") (pinfunction "1_4") (pintype "bidirectional"))
      (node (ref "R10") (pin "2") (pinfunction "2_2") (pintype "bidirectional"))
      (node (ref "R100") (pin "2") (pinfunction "2_2") (pintype "bidirectional"))
      (node (ref "R115") (pin "2") (pinfunction "2_2") (pintype "bidirectional"))
      (node (ref "R116") (pin "2") (pinfunction "2_2") (pintype "bidirectional"))
      (node (ref "R117") (pin "2") (pinfunction "2_2") (pintype "bidirectional"))
      (node (ref "R118") (pin "2") (pinfunction "2_2") (pintype "bidirectional"))
      (node (ref "R12") (pin "1") (pinfunction "1_1") (pintype "bidirectional"))
      (node (ref "R130") (pin "1") (pinfunction "1_1") (pintype "bidirectional"))
      (node (ref "R132") (pin "1") (pinfunction "1_1") (pintype "bidirectional"))
      (node (ref "R135") (pin "2") (pinfunction "2_2") (pintype "bidirectional"))
      (node (ref "R136") (pin "1") (pinfunction "1_1") (pintype "bidirectional"))
      (node (ref "R144") (pin "2") (pinfunction "2_2") (pintype "bidirectional"))
      (node (ref "R145") (pin "2") (pinfunction "2_2") (pintype "bidirectional"))
      (node (ref "R148") (pin "2") (pinfunction "2_2") (pintype "bidirectional"))
      (node (ref "R149") (pin "2") (pinfunction "2_2") (pintype "bidirectional"))
      (node (ref "R164") (pin "2") (pinfunction "2_2") (pintype "bidirectional"))
      (node (ref "R165") (pin "2") (pinfunction "2_2") (pintype "bidirectional"))
      (node (ref "R22") (pin "1") (pinfunction "1_1") (pintype "bidirectional"))
      (node (ref "R25") (pin "2") (pinfunction "2_2") (pintype "bidirectional"))
      (node (ref "R49") (pin "1") (pinfunction "1_1") (pintype "bidirectional"))
      (node (ref "R53") (pin "2") (pinfunction "2_2") (pintype "bidirectional"))
      (node (ref "R54") (pin "1") (pinfunction "1_1") (pintype "bidirectional"))
      (node (ref "R76") (pin "2") (pinfunction "2_2") (pintype "bidirectional"))
      (node (ref "R77") (pin "2") (pinfunction "2_2") (pintype "bidirectional"))
      (node (ref "R78") (pin "2") (pinfunction "2_2") (pintype "bidirectional"))
      (node (ref "R79") (pin "2") (pinfunction "2_2") (pintype "bidirectional"))
      (node (ref "R80") (pin "2") (pinfunction "2_2") (pintype "bidirectional"))
      (node (ref "R81") (pin "2") (pinfunction "2_2") (pintype "bidirectional"))
      (node (ref "R82") (pin "2") (pinfunction "2_2") (pintype "bidirectional"))
      (node (ref "R83") (pin "2") (pinfunction "2_2") (pintype "bidirectional"))
      (node (ref "R84") (pin "2") (pinfunction "2_2") (pintype "bidirectional"))
      (node (ref "R85") (pin "2") (pinfunction "2_2") (pintype "bidirectional"))
      (node (ref "R86") (pin "2") (pinfunction "2_2") (pintype "bidirectional"))
      (node (ref "R87") (pin "2") (pinfunction "2_2") (pintype "bidirectional"))
      (node (ref "R88") (pin "2") (pinfunction "2_2") (pintype "bidirectional"))
      (node (ref "R89") (pin "2") (pinfunction "2_2") (pintype "bidirectional"))
      (node (ref "R90") (pin "2") (pinfunction "2_2") (pintype "bidirectional"))
      (node (ref "R91") (pin "2") (pinfunction "2_2") (pintype "bidirectional"))
      (node (ref "R92") (pin "2") (pinfunction "2_2") (pintype "bidirectional"))
      (node (ref "R93") (pin "2") (pinfunction "2_2") (pintype "bidirectional"))
      (node (ref "R94") (pin "2") (pinfunction "2_2") (pintype "bidirectional"))
      (node (ref "R95") (pin "2") (pinfunction "2_2") (pintype "bidirectional"))
      (node (ref "R96") (pin "1") (pinfunction "1_1") (pintype "bidirectional"))
      (node (ref "R99") (pin "1") (pinfunction "1_1") (pintype "bidirectional"))
      (node (ref "S1") (pin "1") (pinfunction "1_1") (pintype "bidirectional"))
      (node (ref "S1") (pin "3") (pinfunction "3_3") (pintype "bidirectional"))
      (node (ref "S2") (pin "2") (pinfunction "2_2") (pintype "bidirectional"))
      (node (ref "S2") (pin "4") (pinfunction "4_4") (pintype "bidirectional"))
      (node (ref "S3") (pin "1") (pinfunction "1_1") (pintype "bidirectional"))
      (node (ref "S3") (pin "3") (pinfunction "3_3") (pintype "bidirectional"))
      (node (ref "TP1") (pin "1") (pinfunction "1_1") (pintype "bidirectional"))
      (node (ref "TP8") (pin "1") (pinfunction "1_1") (pintype "bidirectional"))
      (node (ref "U10") (pin "4") (pinfunction "4_4") (pintype "bidirectional"))
      (node (ref "U11") (pin "16") (pinfunction "19_16") (pintype "bidirectional"))
      (node (ref "U11") (pin "17") (pinfunction "18_17") (pintype "bidirectional"))
      (node (ref "U11") (pin "18") (pinfunction "17_18") (pintype "bidirectional"))
      (node (ref "U11") (pin "19") (pinfunction "50_19") (pintype "bidirectional"))
      (node (ref "U11") (pin "53") (pinfunction "57_53") (pintype "bidirectional"))
      (node (ref "U11") (pin "54") (pinfunction "58_54") (pintype "bidirectional"))
      (node (ref "U11") (pin "61") (pinfunction "3_61") (pintype "bidirectional"))
      (node (ref "U11") (pin "62") (pinfunction "2_62") (pintype "bidirectional"))
      (node (ref "U11") (pin "63") (pinfunction "1_63") (pintype "bidirectional"))
      (node (ref "U11") (pin "65") (pinfunction "65_65") (pintype "bidirectional"))
      (node (ref "U11") (pin "8") (pinfunction "10_8") (pintype "bidirectional"))
      (node (ref "U11") (pin "9") (pinfunction "9_9") (pintype "bidirectional"))
      (node (ref "U12") (pin "A9") (pinfunction "35_A9") (pintype "bidirectional"))
      (node (ref "U12") (pin "B1") (pinfunction "42_B1") (pintype "bidirectional"))
      (node (ref "U12") (pin "B3") (pinfunction "36_B3") (pintype "bidirectional"))
      (node (ref "U12") (pin "B9") (pinfunction "41_B9") (pintype "bidirectional"))
      (node (ref "U12") (pin "D1") (pinfunction "40_D1") (pintype "bidirectional"))
      (node (ref "U12") (pin "D8") (pinfunction "39_D8") (pintype "bidirectional"))
      (node (ref "U12") (pin "E1") (pinfunction "37_E1") (pintype "bidirectional"))
      (node (ref "U12") (pin "E2") (pinfunction "43_E2") (pintype "bidirectional"))
      (node (ref "U12") (pin "E8") (pinfunction "65_E8") (pintype "bidirectional"))
      (node (ref "U12") (pin "F9") (pinfunction "68_F9") (pintype "bidirectional"))
      (node (ref "U12") (pin "G1") (pinfunction "69_G1") (pintype "bidirectional"))
      (node (ref "U12") (pin "G8") (pinfunction "38_G8") (pintype "bidirectional"))
      (node (ref "U12") (pin "G9") (pinfunction "70_G9") (pintype "bidirectional"))
      (node (ref "U12") (pin "J2") (pinfunction "76_J2") (pintype "bidirectional"))
      (node (ref "U12") (pin "J8") (pinfunction "77_J8") (pintype "bidirectional"))
      (node (ref "U12") (pin "M1") (pinfunction "83_M1") (pintype "bidirectional"))
      (node (ref "U12") (pin "M9") (pinfunction "86_M9") (pintype "bidirectional"))
      (node (ref "U12") (pin "P1") (pinfunction "89_P1") (pintype "bidirectional"))
      (node (ref "U12") (pin "P9") (pinfunction "90_P9") (pintype "bidirectional"))
      (node (ref "U12") (pin "T1") (pinfunction "93_T1") (pintype "bidirectional"))
      (node (ref "U12") (pin "T9") (pinfunction "95_T9") (pintype "bidirectional"))
      (node (ref "U13") (pin "C4") (pinfunction "32_C4") (pintype "bidirectional"))
      (node (ref "U13") (pin "E7") (pinfunction "54_E7") (pintype "bidirectional"))
      (node (ref "U13") (pin "G5") (pinfunction "72_G5") (pintype "bidirectional"))
      (node (ref "U13") (pin "H10") (pinfunction "81_H10") (pintype "bidirectional"))
      (node (ref "U13") (pin "K8") (pinfunction "96_K8") (pintype "bidirectional"))
      (node (ref "U13") (pin "N2") (pinfunction "123_N2") (pintype "bidirectional"))
      (node (ref "U13") (pin "N5") (pinfunction "55_N5") (pintype "bidirectional"))
      (node (ref "U13") (pin "P4") (pinfunction "138_P4") (pintype "bidirectional"))
      (node (ref "U13") (pin "P6") (pinfunction "140_P6") (pintype "bidirectional"))
      (node (ref "U14") (pin "33") (pinfunction "21_33") (pintype "bidirectional"))
      (node (ref "U15") (pin "1") (pinfunction "3_1") (pintype "bidirectional"))
      (node (ref "U15") (pin "4") (pinfunction "5_4") (pintype "bidirectional"))
      (node (ref "U2") (pin "30") (pinfunction "46_30") (pintype "bidirectional"))
      (node (ref "U2") (pin "41") (pinfunction "45_41") (pintype "bidirectional"))
      (node (ref "U2") (pin "49") (pinfunction "49_49") (pintype "bidirectional"))
      (node (ref "U3") (pin "3") (pinfunction "3_3") (pintype "bidirectional"))
      (node (ref "U4") (pin "5") (pinfunction "3_5") (pintype "bidirectional"))
      (node (ref "U4") (pin "6") (pinfunction "6_6") (pintype "bidirectional"))
      (node (ref "U4") (pin "7") (pinfunction "7_7") (pintype "bidirectional"))
      (node (ref "U4") (pin "8") (pinfunction "8_8") (pintype "bidirectional"))
      (node (ref "U5") (pin "A1") (pinfunction "1_A1") (pintype "bidirectional"))
      (node (ref "U5") (pin "A18") (pinfunction "2_A18") (pintype "bidirectional"))
      (node (ref "U5") (pin "F8") (pinfunction "4_F8") (pintype "bidirectional"))
      (node (ref "U5") (pin "G11") (pinfunction "14_G11") (pintype "bidirectional"))
      (node (ref "U5") (pin "G12") (pinfunction "101_G12") (pintype "bidirectional"))
      (node (ref "U5") (pin "G8") (pinfunction "6_G8") (pintype "bidirectional"))
      (node (ref "U5") (pin "G9") (pinfunction "5_G9") (pintype "bidirectional"))
      (node (ref "U5") (pin "H10") (pinfunction "9_H10") (pintype "bidirectional"))
      (node (ref "U5") (pin "H12") (pinfunction "15_H12") (pintype "bidirectional"))
      (node (ref "U5") (pin "H6") (pinfunction "7_H6") (pintype "bidirectional"))
      (node (ref "U5") (pin "H7") (pinfunction "16_H7") (pintype "bidirectional"))
      (node (ref "U5") (pin "H8") (pinfunction "18_H8") (pintype "bidirectional"))
      (node (ref "U5") (pin "H9") (pinfunction "8_H9") (pintype "bidirectional"))
      (node (ref "U5") (pin "J10") (pinfunction "13_J10") (pintype "bidirectional"))
      (node (ref "U5") (pin "J11") (pinfunction "27_J11") (pintype "bidirectional"))
      (node (ref "U5") (pin "J6") (pinfunction "24_J6") (pintype "bidirectional"))
      (node (ref "U5") (pin "J7") (pinfunction "10_J7") (pintype "bidirectional"))
      (node (ref "U5") (pin "J8") (pinfunction "11_J8") (pintype "bidirectional"))
      (node (ref "U5") (pin "J9") (pinfunction "12_J9") (pintype "bidirectional"))
      (node (ref "U5") (pin "K10") (pinfunction "20_K10") (pintype "bidirectional"))
      (node (ref "U5") (pin "K11") (pinfunction "21_K11") (pintype "bidirectional"))
      (node (ref "U5") (pin "K7") (pinfunction "17_K7") (pintype "bidirectional"))
      (node (ref "U5") (pin "K9") (pinfunction "19_K9") (pintype "bidirectional"))
      (node (ref "U5") (pin "L10") (pinfunction "35_L10") (pintype "bidirectional"))
      (node (ref "U5") (pin "L11") (pinfunction "23_L11") (pintype "bidirectional"))
      (node (ref "U5") (pin "L12") (pinfunction "29_L12") (pintype "bidirectional"))
      (node (ref "U5") (pin "L13") (pinfunction "36_L13") (pintype "bidirectional"))
      (node (ref "U5") (pin "M10") (pinfunction "30_M10") (pintype "bidirectional"))
      (node (ref "U5") (pin "M12") (pinfunction "22_M12") (pintype "bidirectional"))
      (node (ref "U5") (pin "M14") (pinfunction "85_M14") (pintype "bidirectional"))
      (node (ref "U5") (pin "M6") (pinfunction "25_M6") (pintype "bidirectional"))
      (node (ref "U5") (pin "M7") (pinfunction "26_M7") (pintype "bidirectional"))
      (node (ref "U5") (pin "M8") (pinfunction "3_M8") (pintype "bidirectional"))
      (node (ref "U5") (pin "M9") (pinfunction "28_M9") (pintype "bidirectional"))
      (node (ref "U5") (pin "N10") (pinfunction "33_N10") (pintype "bidirectional"))
      (node (ref "U5") (pin "N11") (pinfunction "34_N11") (pintype "bidirectional"))
      (node (ref "U5") (pin "N14") (pinfunction "82_N14") (pintype "bidirectional"))
      (node (ref "U5") (pin "N7") (pinfunction "31_N7") (pintype "bidirectional"))
      (node (ref "U5") (pin "V1") (pinfunction "37_V1") (pintype "bidirectional"))
      (node (ref "U5") (pin "V18") (pinfunction "32_V18") (pintype "bidirectional"))
      (node (ref "U6") (pin "4") (pinfunction "4_4") (pintype "bidirectional"))
      (node (ref "U7") (pin "2") (pinfunction "4_2") (pintype "bidirectional"))
      (node (ref "U8") (pin "1") (pinfunction "1_1") (pintype "bidirectional"))
      (node (ref "U8") (pin "9") (pinfunction "9_9") (pintype "bidirectional"))
      (node (ref "U9") (pin "4") (pinfunction "4_4") (pintype "bidirectional"))
      (node (ref "Y4") (pin "2") (pinfunction "2_2") (pintype "bidirectional"))
    )
    (net (code "62") (name "DVI_+5V") (class "Default")
      (node (ref "P6") (pin "19") (pinfunction "18_19") (pintype "bidirectional"))
      (node (ref "R146") (pin "1") (pinfunction "1_1") (pintype "bidirectional"))
      (node (ref "R147") (pin "1") (pinfunction "1_1") (pintype "bidirectional"))
      (node (ref "RT1") (pin "2") (pinfunction "2_2") (pintype "bidirectional"))
    )
    (net (code "63") (name "EHRPWM1A") (class "Default")
      (node (ref "P9") (pin "14") (pinfunction "7_14") (pintype "bidirectional"))
      (node (ref "U5") (pin "U14") (pinfunction "34_U14") (pintype "bidirectional"))
    )
    (net (code "64") (name "EHRPWM1B") (class "Default")
      (node (ref "P9") (pin "16") (pinfunction "8_16") (pintype "bidirectional"))
      (node (ref "U5") (pin "T14") (pinfunction "35_T14") (pintype "bidirectional"))
    )
    (net (code "65") (name "EHRPWM2A") (class "Default")
      (node (ref "P8") (pin "19") (pinfunction "33_19") (pintype "bidirectional"))
      (node (ref "U5") (pin "U10") (pinfunction "24_U10") (pintype "bidirectional"))
    )
    (net (code "66") (name "EHRPWM2B") (class "Default")
      (node (ref "P8") (pin "13") (pinfunction "30_13") (pintype "bidirectional"))
      (node (ref "U5") (pin "T10") (pinfunction "25_T10") (pintype "bidirectional"))
    )
    (net (code "67") (name "EMMC_RSTN") (class "Default")
      (node (ref "R111") (pin "2") (pinfunction "2_2") (pintype "bidirectional"))
      (node (ref "R162") (pin "2") (pinfunction "2_2") (pintype "bidirectional"))
      (node (ref "U13") (pin "K5") (pinfunction "149_K5") (pintype "bidirectional"))
    )
    (net (code "68") (name "GNDA_ADC") (class "Default")
      (node (ref "C31") (pin "2") (pinfunction "2_2") (pintype "bidirectional"))
      (node (ref "C32") (pin "2") (pinfunction "2_2") (pintype "bidirectional"))
      (node (ref "C33") (pin "2") (pinfunction "2_2") (pintype "bidirectional"))
      (node (ref "C93") (pin "2") (pinfunction "2_2") (pintype "bidirectional"))
      (node (ref "FB3") (pin "1") (pinfunction "1_1") (pintype "bidirectional"))
      (node (ref "P9") (pin "34") (pinfunction "17_34") (pintype "bidirectional"))
      (node (ref "U5") (pin "A9") (pinfunction "10_A9") (pintype "bidirectional"))
      (node (ref "U5") (pin "E8") (pinfunction "87_E8") (pintype "bidirectional"))
    )
    (net (code "69") (name "GND_EARTH") (class "Default")
      (node (ref "MTG1") (pin "1") (pinfunction "1_1") (pintype "bidirectional"))
      (node (ref "MTG2") (pin "1") (pinfunction "1_1") (pintype "bidirectional"))
      (node (ref "MTG3") (pin "1") (pinfunction "1_1") (pintype "bidirectional"))
      (node (ref "MTG4") (pin "1") (pinfunction "1_1") (pintype "bidirectional"))
      (node (ref "P10") (pin "11") (pinfunction "11_11") (pintype "bidirectional"))
      (node (ref "P10") (pin "12") (pinfunction "12_12") (pintype "bidirectional"))
      (node (ref "P10") (pin "13") (pinfunction "13_13") (pintype "bidirectional"))
      (node (ref "P10") (pin "14") (pinfunction "14_14") (pintype "bidirectional"))
      (node (ref "P10") (pin "15") (pinfunction "15_15") (pintype "bidirectional"))
      (node (ref "P10") (pin "16") (pinfunction "16_16") (pintype "bidirectional"))
      (node (ref "P3") (pin "5") (pinfunction "5_5") (pintype "bidirectional"))
      (node (ref "P3") (pin "6") (pinfunction "6_6") (pintype "bidirectional"))
      (node (ref "P4") (pin "6") (pinfunction "6_6") (pintype "bidirectional"))
      (node (ref "P4") (pin "7") (pinfunction "5_7") (pintype "bidirectional"))
      (node (ref "P4") (pin "8") (pinfunction "8_8") (pintype "bidirectional"))
      (node (ref "P4") (pin "9") (pinfunction "9_9") (pintype "bidirectional"))
      (node (ref "P5") (pin "13") (pinfunction "12_13") (pintype "bidirectional"))
      (node (ref "P5") (pin "14") (pinfunction "13_14") (pintype "bidirectional"))
      (node (ref "P6") (pin "20") (pinfunction "20_20") (pintype "bidirectional"))
      (node (ref "P6") (pin "21") (pinfunction "21_21") (pintype "bidirectional"))
      (node (ref "P6") (pin "22") (pinfunction "22_22") (pintype "bidirectional"))
      (node (ref "P6") (pin "23") (pinfunction "23_23") (pintype "bidirectional"))
      (node (ref "R136") (pin "2") (pinfunction "2_2") (pintype "bidirectional"))
    )
    (net (code "70") (name "GND_SIGNAL_GND_OSC0") (class "Default")
      (node (ref "C25") (pin "2") (pinfunction "2_2") (pintype "bidirectional"))
      (node (ref "C26") (pin "2") (pinfunction "2_2") (pintype "bidirectional"))
      (node (ref "U5") (pin "V11") (pinfunction "110_V11") (pintype "bidirectional"))
    )
    (net (code "71") (name "GPIO0_7") (class "Default")
      (node (ref "P9") (pin "42") (pinfunction "21_42") (pintype "bidirectional"))
      (node (ref "R50") (pin "1") (pinfunction "1_1") (pintype "bidirectional"))
      (node (ref "R51") (pin "1") (pinfunction "1_1") (pintype "bidirectional"))
    )
    (net (code "72") (name "GPIO0_26") (class "Default")
      (node (ref "P8") (pin "14") (pinfunction "7_14") (pintype "bidirectional"))
      (node (ref "U5") (pin "T11") (pinfunction "26_T11") (pintype "bidirectional"))
    )
    (net (code "73") (name "GPIO0_27") (class "Default")
      (node (ref "P8") (pin "17") (pinfunction "32_17") (pintype "bidirectional"))
      (node (ref "U5") (pin "U12") (pinfunction "27_U12") (pintype "bidirectional"))
    )
    (net (code "74") (name "GPIO1_12") (class "Default")
      (node (ref "P8") (pin "12") (pinfunction "6_12") (pintype "bidirectional"))
      (node (ref "U5") (pin "T12") (pinfunction "28_T12") (pintype "bidirectional"))
    )
    (net (code "75") (name "GPIO1_13") (class "Default")
      (node (ref "P8") (pin "11") (pinfunction "29_11") (pintype "bidirectional"))
      (node (ref "U5") (pin "R12") (pinfunction "29_R12") (pintype "bidirectional"))
    )
    (net (code "76") (name "GPIO1_14") (class "Default")
      (node (ref "P8") (pin "16") (pinfunction "8_16") (pintype "bidirectional"))
      (node (ref "U5") (pin "V13") (pinfunction "30_V13") (pintype "bidirectional"))
    )
    (net (code "77") (name "GPIO1_15") (class "Default")
      (node (ref "P8") (pin "15") (pinfunction "31_15") (pintype "bidirectional"))
      (node (ref "U5") (pin "U13") (pinfunction "31_U13") (pintype "bidirectional"))
    )
    (net (code "78") (name "GPIO1_16") (class "Default")
      (node (ref "P9") (pin "15") (pinfunction "31_15") (pintype "bidirectional"))
      (node (ref "R160") (pin "2") (pinfunction "2_2") (pintype "bidirectional"))
      (node (ref "R161") (pin "2") (pinfunction "2_2") (pintype "bidirectional"))
    )
    (net (code "79") (name "GPIO1_17") (class "Default")
      (node (ref "P9") (pin "23") (pinfunction "35_23") (pintype "bidirectional"))
      (node (ref "U5") (pin "V14") (pinfunction "33_V14") (pintype "bidirectional"))
    )
    (net (code "80") (name "GPIO1_28") (class "Default")
      (node (ref "P9") (pin "12") (pinfunction "6_12") (pintype "bidirectional"))
      (node (ref "U5") (pin "U18") (pinfunction "14_U18") (pintype "bidirectional"))
    )
    (net (code "81") (name "GPIO1_29") (class "Default")
      (node (ref "P8") (pin "26") (pinfunction "13_26") (pintype "bidirectional"))
      (node (ref "U5") (pin "V6") (pinfunction "6_V6") (pintype "bidirectional"))
    )
    (net (code "82") (name "GPIO2_1") (class "Default")
      (node (ref "P8") (pin "18") (pinfunction "9_18") (pintype "bidirectional"))
      (node (ref "U5") (pin "V12") (pinfunction "5_V12") (pintype "bidirectional"))
    )
    (net (code "83") (name "GPIO3_19") (class "Default")
      (node (ref "P9") (pin "27") (pinfunction "37_27") (pintype "bidirectional"))
      (node (ref "U5") (pin "C13") (pinfunction "84_C13") (pintype "bidirectional"))
    )
    (net (code "84") (name "GPIO3_20") (class "Default")
      (node (ref "R20") (pin "2") (pinfunction "2_2") (pintype "bidirectional"))
      (node (ref "U5") (pin "D13") (pinfunction "85_D13") (pintype "bidirectional"))
    )
    (net (code "85") (name "GPIO3_21") (class "Default")
      (node (ref "P9") (pin "25") (pinfunction "36_25") (pintype "bidirectional"))
      (node (ref "R167") (pin "2") (pinfunction "2_2") (pintype "bidirectional"))
      (node (ref "U5") (pin "A14") (pinfunction "78_A14") (pintype "bidirectional"))
    )
    (net (code "86") (name "HDMI_CEC") (class "Default")
      (node (ref "D8") (pin "1") (pinfunction "2_1") (pintype "bidirectional"))
      (node (ref "P6") (pin "15") (pinfunction "13_15") (pintype "bidirectional"))
      (node (ref "U11") (pin "30") (pinfunction "34_30") (pintype "bidirectional"))
    )
    (net (code "87") (name "HDMI_DSCL") (class "Default")
      (node (ref "P6") (pin "17") (pinfunction "15_17") (pintype "bidirectional"))
      (node (ref "R146") (pin "2") (pinfunction "2_2") (pintype "bidirectional"))
      (node (ref "U11") (pin "33") (pinfunction "28_33") (pintype "bidirectional"))
    )
    (net (code "88") (name "HDMI_DSDA") (class "Default")
      (node (ref "P6") (pin "18") (pinfunction "16_18") (pintype "bidirectional"))
      (node (ref "R147") (pin "2") (pinfunction "2_2") (pintype "bidirectional"))
      (node (ref "U11") (pin "32") (pinfunction "29_32") (pintype "bidirectional"))
    )
    (net (code "89") (name "HDMI_HPD") (class "Default")
      (node (ref "P6") (pin "1") (pinfunction "19_1") (pintype "bidirectional"))
      (node (ref "U11") (pin "31") (pinfunction "32_31") (pintype "bidirectional"))
    )
    (net (code "90") (name "HDMI_INT") (class "Default")
      (node (ref "R158") (pin "2") (pinfunction "2_2") (pintype "bidirectional"))
      (node (ref "U11") (pin "50") (pinfunction "33_50") (pintype "bidirectional"))
      (node (ref "U5") (pin "U16") (pinfunction "41_U16") (pintype "bidirectional"))
    )
    (net (code "91") (name "I2C0_SCL") (class "Default")
      (node (ref "R3") (pin "2") (pinfunction "2_2") (pintype "bidirectional"))
      (node (ref "U11") (pin "52") (pinfunction "30_52") (pintype "bidirectional"))
      (node (ref "U2") (pin "28") (pinfunction "16_28") (pintype "bidirectional"))
      (node (ref "U5") (pin "C16") (pinfunction "49_C16") (pintype "bidirectional"))
      (node (ref "U7") (pin "1") (pinfunction "1_1") (pintype "bidirectional"))
    )
    (net (code "92") (name "I2C0_SDA") (class "Default")
      (node (ref "R4") (pin "2") (pinfunction "2_2") (pintype "bidirectional"))
      (node (ref "U11") (pin "51") (pinfunction "31_51") (pintype "bidirectional"))
      (node (ref "U2") (pin "27") (pinfunction "17_27") (pintype "bidirectional"))
      (node (ref "U5") (pin "C17") (pinfunction "50_C17") (pintype "bidirectional"))
      (node (ref "U7") (pin "3") (pinfunction "2_3") (pintype "bidirectional"))
    )
    (net (code "93") (name "I2C1_SCL") (class "Default")
      (node (ref "P9") (pin "17") (pinfunction "32_17") (pintype "bidirectional"))
      (node (ref "U5") (pin "A16") (pinfunction "74_A16") (pintype "bidirectional"))
    )
    (net (code "94") (name "I2C1_SDA") (class "Default")
      (node (ref "P9") (pin "18") (pinfunction "9_18") (pintype "bidirectional"))
      (node (ref "U5") (pin "B16") (pinfunction "73_B16") (pintype "bidirectional"))
    )
    (net (code "95") (name "I2C2_SCL") (class "Default")
      (node (ref "P9") (pin "19") (pinfunction "33_19") (pintype "bidirectional"))
      (node (ref "U5") (pin "D17") (pinfunction "48_D17") (pintype "bidirectional"))
    )
    (net (code "96") (name "I2C2_SDA") (class "Default")
      (node (ref "P9") (pin "20") (pinfunction "10_20") (pintype "bidirectional"))
      (node (ref "U5") (pin "D18") (pinfunction "47_D18") (pintype "bidirectional"))
    )
    (net (code "97") (name "JTAG_EMU0") (class "Default")
      (node (ref "P2") (pin "13") (pinfunction "7_13") (pintype "bidirectional"))
      (node (ref "R23") (pin "2") (pinfunction "2_2") (pintype "bidirectional"))
      (node (ref "U5") (pin "C14") (pinfunction "60_C14") (pintype "bidirectional"))
    )
    (net (code "98") (name "JTAG_EMU1") (class "Default")
      (node (ref "P2") (pin "14") (pinfunction "17_14") (pintype "bidirectional"))
      (node (ref "R24") (pin "2") (pinfunction "2_2") (pintype "bidirectional"))
      (node (ref "U5") (pin "B14") (pinfunction "108_B14") (pintype "bidirectional"))
    )
    (net (code "99") (name "JTAG_TCK") (class "Default")
      (node (ref "P2") (pin "11") (pinfunction "6_11") (pintype "bidirectional"))
      (node (ref "P2") (pin "9") (pinfunction "5_9") (pintype "bidirectional"))
      (node (ref "U5") (pin "A12") (pinfunction "57_A12") (pintype "bidirectional"))
    )
    (net (code "100") (name "JTAG_TDI") (class "Default")
      (node (ref "P2") (pin "3") (pinfunction "2_3") (pintype "bidirectional"))
      (node (ref "U5") (pin "B11") (pinfunction "58_B11") (pintype "bidirectional"))
    )
    (net (code "101") (name "JTAG_TDO") (class "Default")
      (node (ref "P2") (pin "7") (pinfunction "4_7") (pintype "bidirectional"))
      (node (ref "U5") (pin "A11") (pinfunction "59_A11") (pintype "bidirectional"))
    )
    (net (code "102") (name "JTAG_TMS") (class "Default")
      (node (ref "P2") (pin "1") (pinfunction "1_1") (pintype "bidirectional"))
      (node (ref "U5") (pin "C11") (pinfunction "55_C11") (pintype "bidirectional"))
    )
    (net (code "103") (name "JTAG_TRSTN") (class "Default")
      (node (ref "P2") (pin "2") (pinfunction "11_2") (pintype "bidirectional"))
      (node (ref "R25") (pin "1") (pinfunction "1_1") (pintype "bidirectional"))
      (node (ref "U5") (pin "B10") (pinfunction "56_B10") (pintype "bidirectional"))
    )
    (net (code "104") (name "LCD_DATA0") (class "Default")
      (node (ref "C173") (pin "1") (pinfunction "1_1") (pintype "bidirectional"))
      (node (ref "P8") (pin "45") (pinfunction "46_45") (pintype "bidirectional"))
      (node (ref "R70") (pin "2") (pinfunction "2_2") (pintype "bidirectional"))
      (node (ref "R95") (pin "1") (pinfunction "1_1") (pintype "bidirectional"))
      (node (ref "U11") (pin "15") (pinfunction "20_15") (pintype "bidirectional"))
      (node (ref "U5") (pin "R1") (pinfunction "51_R1") (pintype "bidirectional"))
    )
    (net (code "105") (name "LCD_DATA1") (class "Default")
      (node (ref "C171") (pin "1") (pinfunction "1_1") (pintype "bidirectional"))
      (node (ref "P8") (pin "46") (pinfunction "23_46") (pintype "bidirectional"))
      (node (ref "R69") (pin "2") (pinfunction "2_2") (pintype "bidirectional"))
      (node (ref "R94") (pin "1") (pinfunction "1_1") (pintype "bidirectional"))
      (node (ref "U11") (pin "13") (pinfunction "21_13") (pintype "bidirectional"))
      (node (ref "U5") (pin "R2") (pinfunction "52_R2") (pintype "bidirectional"))
    )
    (net (code "106") (name "LCD_DATA2") (class "Default")
      (node (ref "C172") (pin "1") (pinfunction "1_1") (pintype "bidirectional"))
      (node (ref "P8") (pin "43") (pinfunction "45_43") (pintype "bidirectional"))
      (node (ref "R68") (pin "2") (pinfunction "2_2") (pintype "bidirectional"))
      (node (ref "R75") (pin "1") (pinfunction "1_1") (pintype "bidirectional"))
      (node (ref "R93") (pin "1") (pinfunction "1_1") (pintype "bidirectional"))
      (node (ref "U11") (pin "12") (pinfunction "22_12") (pintype "bidirectional"))
      (node (ref "U5") (pin "R3") (pinfunction "53_R3") (pintype "bidirectional"))
    )
    (net (code "107") (name "LCD_DATA3") (class "Default")
      (node (ref "C170") (pin "1") (pinfunction "1_1") (pintype "bidirectional"))
      (node (ref "P8") (pin "44") (pinfunction "22_44") (pintype "bidirectional"))
      (node (ref "R67") (pin "2") (pinfunction "2_2") (pintype "bidirectional"))
      (node (ref "R92") (pin "1") (pinfunction "1_1") (pintype "bidirectional"))
      (node (ref "U11") (pin "11") (pinfunction "23_11") (pintype "bidirectional"))
      (node (ref "U5") (pin "R4") (pinfunction "54_R4") (pintype "bidirectional"))
    )
    (net (code "108") (name "LCD_DATA4") (class "Default")
      (node (ref "C169") (pin "1") (pinfunction "1_1") (pintype "bidirectional"))
      (node (ref "P8") (pin "41") (pinfunction "44_41") (pintype "bidirectional"))
      (node (ref "R66") (pin "2") (pinfunction "2_2") (pintype "bidirectional"))
      (node (ref "R91") (pin "1") (pinfunction "1_1") (pintype "bidirectional"))
      (node (ref "U11") (pin "10") (pinfunction "24_10") (pintype "bidirectional"))
      (node (ref "U5") (pin "T1") (pinfunction "55_T1") (pintype "bidirectional"))
    )
    (net (code "109") (name "LCD_DATA5") (class "Default")
      (node (ref "C163") (pin "1") (pinfunction "1_1") (pintype "bidirectional"))
      (node (ref "P8") (pin "42") (pinfunction "21_42") (pintype "bidirectional"))
      (node (ref "R65") (pin "2") (pinfunction "2_2") (pintype "bidirectional"))
      (node (ref "R90") (pin "1") (pinfunction "1_1") (pintype "bidirectional"))
      (node (ref "U11") (pin "7") (pinfunction "11_7") (pintype "bidirectional"))
      (node (ref "U5") (pin "T2") (pinfunction "56_T2") (pintype "bidirectional"))
    )
    (net (code "110") (name "LCD_DATA6") (class "Default")
      (node (ref "C162") (pin "1") (pinfunction "1_1") (pintype "bidirectional"))
      (node (ref "P8") (pin "39") (pinfunction "43_39") (pintype "bidirectional"))
      (node (ref "R64") (pin "2") (pinfunction "2_2") (pintype "bidirectional"))
      (node (ref "R89") (pin "1") (pinfunction "1_1") (pintype "bidirectional"))
      (node (ref "U11") (pin "6") (pinfunction "12_6") (pintype "bidirectional"))
      (node (ref "U5") (pin "T3") (pinfunction "57_T3") (pintype "bidirectional"))
    )
    (net (code "111") (name "LCD_DATA7") (class "Default")
      (node (ref "C161") (pin "1") (pinfunction "1_1") (pintype "bidirectional"))
      (node (ref "P8") (pin "40") (pinfunction "20_40") (pintype "bidirectional"))
      (node (ref "R63") (pin "2") (pinfunction "2_2") (pintype "bidirectional"))
      (node (ref "R88") (pin "1") (pinfunction "1_1") (pintype "bidirectional"))
      (node (ref "U11") (pin "3") (pinfunction "13_3") (pintype "bidirectional"))
      (node (ref "U5") (pin "T4") (pinfunction "58_T4") (pintype "bidirectional"))
    )
    (net (code "112") (name "LCD_DATA8") (class "Default")
      (node (ref "C160") (pin "1") (pinfunction "1_1") (pintype "bidirectional"))
      (node (ref "P8") (pin "37") (pinfunction "42_37") (pintype "bidirectional"))
      (node (ref "R62") (pin "2") (pinfunction "2_2") (pintype "bidirectional"))
      (node (ref "R87") (pin "1") (pinfunction "1_1") (pintype "bidirectional"))
      (node (ref "U11") (pin "2") (pinfunction "14_2") (pintype "bidirectional"))
      (node (ref "U5") (pin "U1") (pinfunction "59_U1") (pintype "bidirectional"))
    )
    (net (code "113") (name "LCD_DATA9") (class "Default")
      (node (ref "C157") (pin "1") (pinfunction "1_1") (pintype "bidirectional"))
      (node (ref "P8") (pin "38") (pinfunction "19_38") (pintype "bidirectional"))
      (node (ref "R61") (pin "2") (pinfunction "2_2") (pintype "bidirectional"))
      (node (ref "R86") (pin "1") (pinfunction "1_1") (pintype "bidirectional"))
      (node (ref "U11") (pin "1") (pinfunction "15_1") (pintype "bidirectional"))
      (node (ref "U5") (pin "U2") (pinfunction "60_U2") (pintype "bidirectional"))
    )
    (net (code "114") (name "LCD_DATA10") (class "Default")
      (node (ref "C156") (pin "1") (pinfunction "1_1") (pintype "bidirectional"))
      (node (ref "P8") (pin "36") (pinfunction "18_36") (pintype "bidirectional"))
      (node (ref "R60") (pin "2") (pinfunction "2_2") (pintype "bidirectional"))
      (node (ref "R85") (pin "1") (pinfunction "1_1") (pintype "bidirectional"))
      (node (ref "U11") (pin "64") (pinfunction "16_64") (pintype "bidirectional"))
      (node (ref "U5") (pin "U3") (pinfunction "61_U3") (pintype "bidirectional"))
    )
    (net (code "115") (name "LCD_DATA11") (class "Default")
      (node (ref "C168") (pin "1") (pinfunction "1_1") (pintype "bidirectional"))
      (node (ref "P8") (pin "34") (pinfunction "17_34") (pintype "bidirectional"))
      (node (ref "R59") (pin "2") (pinfunction "2_2") (pintype "bidirectional"))
      (node (ref "R84") (pin "1") (pinfunction "1_1") (pintype "bidirectional"))
      (node (ref "U11") (pin "60") (pinfunction "4_60") (pintype "bidirectional"))
      (node (ref "U5") (pin "U4") (pinfunction "62_U4") (pintype "bidirectional"))
    )
    (net (code "116") (name "LCD_DATA12") (class "Default")
      (node (ref "C167") (pin "1") (pinfunction "1_1") (pintype "bidirectional"))
      (node (ref "P8") (pin "35") (pinfunction "41_35") (pintype "bidirectional"))
      (node (ref "R58") (pin "2") (pinfunction "2_2") (pintype "bidirectional"))
      (node (ref "R83") (pin "1") (pinfunction "1_1") (pintype "bidirectional"))
      (node (ref "U11") (pin "59") (pinfunction "5_59") (pintype "bidirectional"))
      (node (ref "U5") (pin "V2") (pinfunction "63_V2") (pintype "bidirectional"))
    )
    (net (code "117") (name "LCD_DATA13") (class "Default")
      (node (ref "C166") (pin "1") (pinfunction "1_1") (pintype "bidirectional"))
      (node (ref "P8") (pin "33") (pinfunction "40_33") (pintype "bidirectional"))
      (node (ref "R57") (pin "2") (pinfunction "2_2") (pintype "bidirectional"))
      (node (ref "R82") (pin "1") (pinfunction "1_1") (pintype "bidirectional"))
      (node (ref "U11") (pin "58") (pinfunction "6_58") (pintype "bidirectional"))
      (node (ref "U5") (pin "V3") (pinfunction "64_V3") (pintype "bidirectional"))
    )
    (net (code "118") (name "LCD_DATA14") (class "Default")
      (node (ref "C165") (pin "1") (pinfunction "1_1") (pintype "bidirectional"))
      (node (ref "P8") (pin "31") (pinfunction "39_31") (pintype "bidirectional"))
      (node (ref "R56") (pin "2") (pinfunction "2_2") (pintype "bidirectional"))
      (node (ref "R81") (pin "1") (pinfunction "1_1") (pintype "bidirectional"))
      (node (ref "U11") (pin "57") (pinfunction "7_57") (pintype "bidirectional"))
      (node (ref "U5") (pin "V4") (pinfunction "65_V4") (pintype "bidirectional"))
    )
    (net (code "119") (name "LCD_DATA15") (class "Default")
      (node (ref "C164") (pin "1") (pinfunction "1_1") (pintype "bidirectional"))
      (node (ref "P8") (pin "32") (pinfunction "16_32") (pintype "bidirectional"))
      (node (ref "R55") (pin "2") (pinfunction "2_2") (pintype "bidirectional"))
      (node (ref "R80") (pin "1") (pinfunction "1_1") (pintype "bidirectional"))
      (node (ref "U11") (pin "56") (pinfunction "8_56") (pintype "bidirectional"))
      (node (ref "U5") (pin "T5") (pinfunction "66_T5") (pintype "bidirectional"))
    )
    (net (code "120") (name "LCD_DE") (class "Default")
      (node (ref "P8") (pin "30") (pinfunction "15_30") (pintype "bidirectional"))
      (node (ref "R48") (pin "2") (pinfunction "2_2") (pintype "bidirectional"))
      (node (ref "U11") (pin "20") (pinfunction "27_20") (pintype "bidirectional"))
    )
    (net (code "121") (name "LCD_HSYNC") (class "Default")
      (node (ref "P8") (pin "29") (pinfunction "38_29") (pintype "bidirectional"))
      (node (ref "R47") (pin "2") (pinfunction "2_2") (pintype "bidirectional"))
      (node (ref "U11") (pin "22") (pinfunction "26_22") (pintype "bidirectional"))
    )
    (net (code "122") (name "LCD_PCLK") (class "Default")
      (node (ref "P8") (pin "28") (pinfunction "14_28") (pintype "bidirectional"))
      (node (ref "R45") (pin "2") (pinfunction "2_2") (pintype "bidirectional"))
      (node (ref "U11") (pin "4") (pinfunction "43_4") (pintype "bidirectional"))
    )
    (net (code "123") (name "LCD_VSYNC") (class "Default")
      (node (ref "P8") (pin "27") (pinfunction "37_27") (pintype "bidirectional"))
      (node (ref "R46") (pin "2") (pinfunction "2_2") (pintype "bidirectional"))
      (node (ref "U11") (pin "21") (pinfunction "25_21") (pintype "bidirectional"))
    )
    (net (code "124") (name "LDO_PGOOD") (class "Default")
      (node (ref "U2") (pin "46") (pinfunction "26_46") (pintype "bidirectional"))
      (node (ref "U5") (pin "B5") (pinfunction "116_B5") (pintype "bidirectional"))
    )
    (net (code "125") (name "MDIO_CLK") (class "Default")
      (node (ref "U14") (pin "17") (pinfunction "2_17") (pintype "bidirectional"))
      (node (ref "U5") (pin "M18") (pinfunction "43_M18") (pintype "bidirectional"))
    )
    (net (code "126") (name "MDIO_DATA") (class "Default")
      (node (ref "R119") (pin "2") (pinfunction "2_2") (pintype "bidirectional"))
      (node (ref "U14") (pin "16") (pinfunction "1_16") (pintype "bidirectional"))
      (node (ref "U5") (pin "M17") (pinfunction "44_M17") (pintype "bidirectional"))
    )
    (net (code "127") (name "MII1_COL") (class "Default")
      (node (ref "R138") (pin "1") (pinfunction "1_1") (pintype "bidirectional"))
      (node (ref "U5") (pin "H16") (pinfunction "27_H16") (pintype "bidirectional"))
    )
    (net (code "128") (name "MII1_CRS_DV") (class "Default")
      (node (ref "R139") (pin "1") (pinfunction "1_1") (pintype "bidirectional"))
      (node (ref "U5") (pin "H17") (pinfunction "28_H17") (pintype "bidirectional"))
    )
    (net (code "129") (name "MII1_REFCLK") (class "Default")
      (node (ref "R124") (pin "1") (pinfunction "1_1") (pintype "bidirectional"))
      (node (ref "R140") (pin "1") (pinfunction "1_1") (pintype "bidirectional"))
      (node (ref "R28") (pin "2") (pinfunction "2_2") (pintype "bidirectional"))
    )
    (net (code "130") (name "MII1_RXCLK") (class "Default")
      (node (ref "R131") (pin "1") (pinfunction "1_1") (pintype "bidirectional"))
      (node (ref "U5") (pin "L18") (pinfunction "37_L18") (pintype "bidirectional"))
    )
    (net (code "131") (name "MII1_RXD0") (class "Default")
      (node (ref "R128") (pin "1") (pinfunction "1_1") (pintype "bidirectional"))
      (node (ref "U5") (pin "M16") (pinfunction "38_M16") (pintype "bidirectional"))
    )
    (net (code "132") (name "MII1_RXD1") (class "Default")
      (node (ref "R127") (pin "1") (pinfunction "1_1") (pintype "bidirectional"))
      (node (ref "U5") (pin "L15") (pinfunction "39_L15") (pintype "bidirectional"))
    )
    (net (code "133") (name "MII1_RXD2") (class "Default")
      (node (ref "R126") (pin "1") (pinfunction "1_1") (pintype "bidirectional"))
      (node (ref "U5") (pin "L16") (pinfunction "40_L16") (pintype "bidirectional"))
    )
    (net (code "134") (name "MII1_RXD3") (class "Default")
      (node (ref "R125") (pin "1") (pinfunction "1_1") (pintype "bidirectional"))
      (node (ref "U5") (pin "L17") (pinfunction "41_L17") (pintype "bidirectional"))
    )
    (net (code "135") (name "MII1_RXDV") (class "Default")
      (node (ref "R129") (pin "1") (pinfunction "1_1") (pintype "bidirectional"))
      (node (ref "U5") (pin "J17") (pinfunction "36_J17") (pintype "bidirectional"))
    )
    (net (code "136") (name "MII1_RXERR") (class "Default")
      (node (ref "R133") (pin "1") (pinfunction "1_1") (pintype "bidirectional"))
      (node (ref "U5") (pin "J15") (pinfunction "35_J15") (pintype "bidirectional"))
    )
    (net (code "137") (name "MII1_TXCLK") (class "Default")
      (node (ref "R134") (pin "1") (pinfunction "1_1") (pintype "bidirectional"))
      (node (ref "U5") (pin "K18") (pinfunction "33_K18") (pintype "bidirectional"))
    )
    (net (code "138") (name "MII1_TXD0") (class "Default")
      (node (ref "U14") (pin "22") (pinfunction "12_22") (pintype "bidirectional"))
      (node (ref "U5") (pin "K17") (pinfunction "29_K17") (pintype "bidirectional"))
    )
    (net (code "139") (name "MII1_TXD1") (class "Default")
      (node (ref "U14") (pin "23") (pinfunction "13_23") (pintype "bidirectional"))
      (node (ref "U5") (pin "K16") (pinfunction "30_K16") (pintype "bidirectional"))
    )
    (net (code "140") (name "MII1_TXD2") (class "Default")
      (node (ref "U14") (pin "24") (pinfunction "14_24") (pintype "bidirectional"))
      (node (ref "U5") (pin "K15") (pinfunction "31_K15") (pintype "bidirectional"))
    )
    (net (code "141") (name "MII1_TXD3") (class "Default")
      (node (ref "U14") (pin "25") (pinfunction "15_25") (pintype "bidirectional"))
      (node (ref "U5") (pin "J18") (pinfunction "32_J18") (pintype "bidirectional"))
    )
    (net (code "142") (name "MII1_TXEN") (class "Default")
      (node (ref "U14") (pin "21") (pinfunction "11_21") (pintype "bidirectional"))
      (node (ref "U5") (pin "J16") (pinfunction "34_J16") (pintype "bidirectional"))
    )
    (net (code "143") (name "MMC0_CD") (class "Default")
      (node (ref "P10") (pin "10") (pinfunction "10_10") (pintype "bidirectional"))
      (node (ref "P2") (pin "19") (pinfunction "10_19") (pintype "bidirectional"))
      (node (ref "R157") (pin "1") (pinfunction "1_1") (pintype "bidirectional"))
      (node (ref "U5") (pin "C15") (pinfunction "75_C15") (pintype "bidirectional"))
    )
    (net (code "144") (name "MMC0_CLKO") (class "Default")
      (node (ref "P10") (pin "5") (pinfunction "5_5") (pintype "bidirectional"))
      (node (ref "R152") (pin "2") (pinfunction "2_2") (pintype "bidirectional"))
      (node (ref "U5") (pin "G17") (pinfunction "44_G17") (pintype "bidirectional"))
    )
    (net (code "145") (name "MMC0_CMD") (class "Default")
      (node (ref "P10") (pin "3") (pinfunction "3_3") (pintype "bidirectional"))
      (node (ref "R151") (pin "2") (pinfunction "2_2") (pintype "bidirectional"))
      (node (ref "U5") (pin "G18") (pinfunction "45_G18") (pintype "bidirectional"))
    )
    (net (code "146") (name "MMC0_DAT0") (class "Default")
      (node (ref "P10") (pin "7") (pinfunction "7_7") (pintype "bidirectional"))
      (node (ref "R153") (pin "2") (pinfunction "2_2") (pintype "bidirectional"))
      (node (ref "U5") (pin "G16") (pinfunction "46_G16") (pintype "bidirectional"))
    )
    (net (code "147") (name "MMC0_DAT1") (class "Default")
      (node (ref "P10") (pin "8") (pinfunction "8_8") (pintype "bidirectional"))
      (node (ref "R154") (pin "2") (pinfunction "2_2") (pintype "bidirectional"))
      (node (ref "U5") (pin "G15") (pinfunction "47_G15") (pintype "bidirectional"))
    )
    (net (code "148") (name "MMC0_DAT2") (class "Default")
      (node (ref "P10") (pin "1") (pinfunction "1_1") (pintype "bidirectional"))
      (node (ref "R150") (pin "2") (pinfunction "2_2") (pintype "bidirectional"))
      (node (ref "U5") (pin "F18") (pinfunction "48_F18") (pintype "bidirectional"))
    )
    (net (code "149") (name "MMC0_DAT3") (class "Default")
      (node (ref "P10") (pin "2") (pinfunction "2_2") (pintype "bidirectional"))
      (node (ref "R155") (pin "2") (pinfunction "2_2") (pintype "bidirectional"))
      (node (ref "U5") (pin "F17") (pinfunction "49_F17") (pintype "bidirectional"))
    )
    (net (code "150") (name "MMC1_CLK") (class "Default")
      (node (ref "P8") (pin "21") (pinfunction "34_21") (pintype "bidirectional"))
      (node (ref "R110") (pin "2") (pinfunction "2_2") (pintype "bidirectional"))
      (node (ref "U13") (pin "M6") (pinfunction "113_M6") (pintype "bidirectional"))
      (node (ref "U5") (pin "U9") (pinfunction "7_U9") (pintype "bidirectional"))
    )
    (net (code "151") (name "MMC1_CMD") (class "Default")
      (node (ref "P8") (pin "20") (pinfunction "10_20") (pintype "bidirectional"))
      (node (ref "R109") (pin "2") (pinfunction "2_2") (pintype "bidirectional"))
      (node (ref "U13") (pin "M5") (pinfunction "112_M5") (pintype "bidirectional"))
      (node (ref "U5") (pin "V9") (pinfunction "8_V9") (pintype "bidirectional"))
    )
    (net (code "152") (name "MMC1_DAT0") (class "Default")
      (node (ref "P8") (pin "25") (pinfunction "36_25") (pintype "bidirectional"))
      (node (ref "R101") (pin "2") (pinfunction "2_2") (pintype "bidirectional"))
      (node (ref "U13") (pin "A3") (pinfunction "3_A3") (pintype "bidirectional"))
      (node (ref "U5") (pin "U7") (pinfunction "16_U7") (pintype "bidirectional"))
    )
    (net (code "153") (name "MMC1_DAT1") (class "Default")
      (node (ref "P8") (pin "24") (pinfunction "12_24") (pintype "bidirectional"))
      (node (ref "R102") (pin "2") (pinfunction "2_2") (pintype "bidirectional"))
      (node (ref "U13") (pin "A4") (pinfunction "4_A4") (pintype "bidirectional"))
      (node (ref "U5") (pin "V7") (pinfunction "17_V7") (pintype "bidirectional"))
    )
    (net (code "154") (name "MMC1_DAT2") (class "Default")
      (node (ref "P8") (pin "5") (pinfunction "26_5") (pintype "bidirectional"))
      (node (ref "R103") (pin "2") (pinfunction "2_2") (pintype "bidirectional"))
      (node (ref "U13") (pin "A5") (pinfunction "5_A5") (pintype "bidirectional"))
      (node (ref "U5") (pin "R8") (pinfunction "18_R8") (pintype "bidirectional"))
    )
    (net (code "155") (name "MMC1_DAT3") (class "Default")
      (node (ref "P8") (pin "6") (pinfunction "3_6") (pintype "bidirectional"))
      (node (ref "R104") (pin "2") (pinfunction "2_2") (pintype "bidirectional"))
      (node (ref "U13") (pin "B2") (pinfunction "16_B2") (pintype "bidirectional"))
      (node (ref "U5") (pin "T8") (pinfunction "19_T8") (pintype "bidirectional"))
    )
    (net (code "156") (name "MMC1_DAT4") (class "Default")
      (node (ref "P8") (pin "23") (pinfunction "35_23") (pintype "bidirectional"))
      (node (ref "R105") (pin "2") (pinfunction "2_2") (pintype "bidirectional"))
      (node (ref "U13") (pin "B3") (pinfunction "17_B3") (pintype "bidirectional"))
      (node (ref "U5") (pin "U8") (pinfunction "20_U8") (pintype "bidirectional"))
    )
    (net (code "157") (name "MMC1_DAT5") (class "Default")
      (node (ref "P8") (pin "22") (pinfunction "11_22") (pintype "bidirectional"))
      (node (ref "R106") (pin "2") (pinfunction "2_2") (pintype "bidirectional"))
      (node (ref "U13") (pin "B4") (pinfunction "18_B4") (pintype "bidirectional"))
      (node (ref "U5") (pin "V8") (pinfunction "21_V8") (pintype "bidirectional"))
    )
    (net (code "158") (name "MMC1_DAT6") (class "Default")
      (node (ref "P8") (pin "3") (pinfunction "25_3") (pintype "bidirectional"))
      (node (ref "R107") (pin "2") (pinfunction "2_2") (pintype "bidirectional"))
      (node (ref "U13") (pin "B5") (pinfunction "19_B5") (pintype "bidirectional"))
      (node (ref "U5") (pin "R9") (pinfunction "22_R9") (pintype "bidirectional"))
    )
    (net (code "159") (name "MMC1_DAT7") (class "Default")
      (node (ref "P8") (pin "4") (pinfunction "2_4") (pintype "bidirectional"))
      (node (ref "R108") (pin "2") (pinfunction "2_2") (pintype "bidirectional"))
      (node (ref "U13") (pin "B6") (pinfunction "20_B6") (pintype "bidirectional"))
      (node (ref "U5") (pin "T9") (pinfunction "23_T9") (pintype "bidirectional"))
    )
    (net (code "160") (name "MODE2") (class "Default")
      (node (ref "R113") (pin "1") (pinfunction "1_1") (pintype "bidirectional"))
      (node (ref "R138") (pin "2") (pinfunction "2_2") (pintype "bidirectional"))
      (node (ref "U14") (pin "15") (pinfunction "16_15") (pintype "bidirectional"))
    )
    (net (code "161") (name "Net-(C142-Pad1)") (class "Default")
      (node (ref "C142") (pin "1") (pinfunction "1_1") (pintype "bidirectional"))
      (node (ref "R143") (pin "2") (pinfunction "2_2") (pintype "bidirectional"))
      (node (ref "Y3") (pin "2") (pinfunction "2_2") (pintype "bidirectional"))
    )
    (net (code "162") (name "Net-(C143-Pad1)") (class "Default")
      (node (ref "C143") (pin "1") (pinfunction "1_1") (pintype "bidirectional"))
      (node (ref "R141") (pin "2") (pinfunction "2_2") (pintype "bidirectional"))
      (node (ref "R142") (pin "1") (pinfunction "1_1") (pintype "bidirectional"))
      (node (ref "Y3") (pin "1") (pinfunction "1_1") (pintype "bidirectional"))
    )
    (net (code "163") (name "Net-(D1-Pad1)") (class "Default")
      (node (ref "D1") (pin "1") (pinfunction "1_1") (pintype "bidirectional"))
      (node (ref "R12") (pin "2") (pinfunction "2_2") (pintype "bidirectional"))
    )
    (net (code "164") (name "Net-(D2-Pad2)") (class "Default")
      (node (ref "D2") (pin "2") (pinfunction "2_2") (pintype "bidirectional"))
      (node (ref "R72") (pin "2") (pinfunction "2_2") (pintype "bidirectional"))
    )
    (net (code "165") (name "Net-(D3-Pad2)") (class "Default")
      (node (ref "D3") (pin "2") (pinfunction "2_2") (pintype "bidirectional"))
      (node (ref "R73") (pin "2") (pinfunction "2_2") (pintype "bidirectional"))
    )
    (net (code "166") (name "Net-(D4-Pad2)") (class "Default")
      (node (ref "D4") (pin "2") (pinfunction "2_2") (pintype "bidirectional"))
      (node (ref "R74") (pin "2") (pinfunction "2_2") (pintype "bidirectional"))
    )
    (net (code "167") (name "Net-(D5-Pad2)") (class "Default")
      (node (ref "D5") (pin "2") (pinfunction "2_2") (pintype "bidirectional"))
      (node (ref "R71") (pin "2") (pinfunction "2_2") (pintype "bidirectional"))
    )
    (net (code "168") (name "Net-(D8-1)") (class "Default")
      (node (ref "D8") (pin "2") (pinfunction "1_2") (pintype "bidirectional"))
      (node (ref "R166") (pin "1") (pinfunction "1_1") (pintype "bidirectional"))
    )
    (net (code "169") (name "Net-(FB7-Pad2)") (class "Default")
      (node (ref "FB7") (pin "2") (pinfunction "2_2") (pintype "bidirectional"))
      (node (ref "P3") (pin "1") (pinfunction "1_1") (pintype "bidirectional"))
    )
    (net (code "170") (name "Net-(P5-1)") (class "Default")
      (node (ref "C141") (pin "1") (pinfunction "1_1") (pintype "bidirectional"))
      (node (ref "P5") (pin "4") (pinfunction "6_4") (pintype "bidirectional"))
      (node (ref "P5") (pin "5") (pinfunction "1_5") (pintype "bidirectional"))
      (node (ref "R137") (pin "1") (pinfunction "1_1") (pintype "bidirectional"))
    )
    (net (code "171") (name "Net-(P5-2)") (class "Default")
      (node (ref "C139") (pin "1") (pinfunction "1_1") (pintype "bidirectional"))
      (node (ref "P5") (pin "3") (pinfunction "2_3") (pintype "bidirectional"))
      (node (ref "R122") (pin "1") (pinfunction "1_1") (pintype "bidirectional"))
      (node (ref "U14") (pin "29") (pinfunction "30_29") (pintype "bidirectional"))
    )
    (net (code "172") (name "Net-(P5-3)") (class "Default")
      (node (ref "C140") (pin "1") (pinfunction "1_1") (pintype "bidirectional"))
      (node (ref "P5") (pin "6") (pinfunction "3_6") (pintype "bidirectional"))
      (node (ref "R123") (pin "1") (pinfunction "1_1") (pintype "bidirectional"))
      (node (ref "U14") (pin "28") (pinfunction "29_28") (pintype "bidirectional"))
    )
    (net (code "173") (name "Net-(P5-4)") (class "Default")
      (node (ref "C137") (pin "1") (pinfunction "1_1") (pintype "bidirectional"))
      (node (ref "P5") (pin "1") (pinfunction "4_1") (pintype "bidirectional"))
      (node (ref "R120") (pin "1") (pinfunction "1_1") (pintype "bidirectional"))
      (node (ref "U14") (pin "31") (pinfunction "27_31") (pintype "bidirectional"))
    )
    (net (code "174") (name "Net-(P5-5)") (class "Default")
      (node (ref "C138") (pin "1") (pinfunction "1_1") (pintype "bidirectional"))
      (node (ref "P5") (pin "2") (pinfunction "5_2") (pintype "bidirectional"))
      (node (ref "R121") (pin "1") (pinfunction "1_1") (pintype "bidirectional"))
      (node (ref "U14") (pin "30") (pinfunction "28_30") (pintype "bidirectional"))
    )
    (net (code "175") (name "Net-(P5-7)") (class "Default")
      (node (ref "P5") (pin "11") (pinfunction "7_11") (pintype "bidirectional"))
      (node (ref "R130") (pin "2") (pinfunction "2_2") (pintype "bidirectional"))
    )
    (net (code "176") (name "Net-(P5-8)") (class "Default")
      (node (ref "P5") (pin "12") (pinfunction "8_12") (pintype "bidirectional"))
      (node (ref "R135") (pin "1") (pinfunction "1_1") (pintype "bidirectional"))
      (node (ref "U14") (pin "2") (pinfunction "32_2") (pintype "bidirectional"))
    )
    (net (code "177") (name "Net-(P5-9)") (class "Default")
      (node (ref "P5") (pin "10") (pinfunction "9_10") (pintype "bidirectional"))
      (node (ref "R132") (pin "2") (pinfunction "2_2") (pintype "bidirectional"))
    )
    (net (code "178") (name "Net-(P5-10)") (class "Default")
      (node (ref "P5") (pin "9") (pinfunction "10_9") (pintype "bidirectional"))
      (node (ref "U14") (pin "3") (pinfunction "33_3") (pintype "bidirectional"))
    )
    (net (code "179") (name "Net-(P6-1)") (class "Default")
      (node (ref "D7") (pin "2") (pinfunction "2_2") (pintype "bidirectional"))
      (node (ref "P6") (pin "3") (pinfunction "1_3") (pintype "bidirectional"))
      (node (ref "U11") (pin "45") (pinfunction "41_45") (pintype "bidirectional"))
    )
    (net (code "180") (name "Net-(P6-2)") (class "Default")
      (node (ref "D7") (pin "1") (pinfunction "1_1") (pintype "bidirectional"))
      (node (ref "P6") (pin "5") (pinfunction "2_5") (pintype "bidirectional"))
      (node (ref "U11") (pin "44") (pinfunction "42_44") (pintype "bidirectional"))
    )
    (net (code "181") (name "Net-(P6-4)") (class "Default")
      (node (ref "D7") (pin "5") (pinfunction "5_5") (pintype "bidirectional"))
      (node (ref "P6") (pin "6") (pinfunction "4_6") (pintype "bidirectional"))
      (node (ref "U11") (pin "43") (pinfunction "39_43") (pintype "bidirectional"))
    )
    (net (code "182") (name "Net-(P6-6)") (class "Default")
      (node (ref "D7") (pin "4") (pinfunction "4_4") (pintype "bidirectional"))
      (node (ref "P6") (pin "8") (pinfunction "6_8") (pintype "bidirectional"))
      (node (ref "U11") (pin "42") (pinfunction "40_42") (pintype "bidirectional"))
    )
    (net (code "183") (name "Net-(P6-7)") (class "Default")
      (node (ref "D6") (pin "2") (pinfunction "2_2") (pintype "bidirectional"))
      (node (ref "P6") (pin "9") (pinfunction "7_9") (pintype "bidirectional"))
      (node (ref "U11") (pin "40") (pinfunction "37_40") (pintype "bidirectional"))
    )
    (net (code "184") (name "Net-(P6-9)") (class "Default")
      (node (ref "D6") (pin "1") (pinfunction "1_1") (pintype "bidirectional"))
      (node (ref "P6") (pin "11") (pinfunction "9_11") (pintype "bidirectional"))
      (node (ref "U11") (pin "39") (pinfunction "38_39") (pintype "bidirectional"))
    )
    (net (code "185") (name "Net-(P6-10)") (class "Default")
      (node (ref "D6") (pin "4") (pinfunction "4_4") (pintype "bidirectional"))
      (node (ref "P6") (pin "12") (pinfunction "10_12") (pintype "bidirectional"))
      (node (ref "U11") (pin "38") (pinfunction "35_38") (pintype "bidirectional"))
    )
    (net (code "186") (name "Net-(P6-11)") (class "Default")
      (node (ref "D6") (pin "5") (pinfunction "5_5") (pintype "bidirectional"))
      (node (ref "P6") (pin "14") (pinfunction "11_14") (pintype "bidirectional"))
      (node (ref "U11") (pin "37") (pinfunction "36_37") (pintype "bidirectional"))
    )
    (net (code "187") (name "Net-(Q1A-2)") (class "Default")
      (node (ref "D2") (pin "1") (pinfunction "1_1") (pintype "bidirectional"))
      (node (ref "Q1") (pin "6") (pinfunction "2_6") (pintype "bidirectional"))
    )
    (net (code "188") (name "Net-(Q1B-2)") (class "Default")
      (node (ref "D3") (pin "1") (pinfunction "1_1") (pintype "bidirectional"))
      (node (ref "Q1") (pin "3") (pinfunction "2_3") (pintype "bidirectional"))
    )
    (net (code "189") (name "Net-(Q2A-2)") (class "Default")
      (node (ref "D4") (pin "1") (pinfunction "1_1") (pintype "bidirectional"))
      (node (ref "Q2") (pin "6") (pinfunction "2_6") (pintype "bidirectional"))
    )
    (net (code "190") (name "Net-(Q2B-2)") (class "Default")
      (node (ref "D5") (pin "1") (pinfunction "1_1") (pintype "bidirectional"))
      (node (ref "Q2") (pin "3") (pinfunction "2_3") (pintype "bidirectional"))
    )
    (net (code "191") (name "Net-(R21-Pad1)") (class "Default")
      (node (ref "R21") (pin "1") (pinfunction "1_1") (pintype "bidirectional"))
      (node (ref "U6") (pin "5") (pinfunction "5_5") (pintype "bidirectional"))
    )
    (net (code "192") (name "Net-(R75-Pad2)") (class "Default")
      (node (ref "R75") (pin "2") (pinfunction "2_2") (pintype "bidirectional"))
      (node (ref "S2") (pin "1") (pinfunction "1_1") (pintype "bidirectional"))
      (node (ref "S2") (pin "3") (pinfunction "3_3") (pintype "bidirectional"))
    )
    (net (code "193") (name "Net-(R156-Pad2)") (class "Default")
      (node (ref "R156") (pin "2") (pinfunction "2_2") (pintype "bidirectional"))
      (node (ref "TP4") (pin "1") (pinfunction "1_1") (pintype "bidirectional"))
      (node (ref "U7") (pin "5") (pinfunction "5_5") (pintype "bidirectional"))
    )
    (net (code "194") (name "Net-(U2-5)") (class "Default")
      (node (ref "TP5") (pin "1") (pinfunction "1_1") (pintype "bidirectional"))
      (node (ref "U2") (pin "4") (pinfunction "5_4") (pintype "bidirectional"))
      (node (ref "U2") (pin "5") (pinfunction "6_5") (pintype "bidirectional"))
    )
    (net (code "195") (name "Net-(U2-7)") (class "Default")
      (node (ref "TP6") (pin "1") (pinfunction "1_1") (pintype "bidirectional"))
      (node (ref "U2") (pin "6") (pinfunction "7_6") (pintype "bidirectional"))
    )
    (net (code "196") (name "Net-(U2-8)") (class "Default")
      (node (ref "TP7") (pin "1") (pinfunction "1_1") (pintype "bidirectional"))
      (node (ref "U2") (pin "11") (pinfunction "8_11") (pintype "bidirectional"))
    )
    (net (code "197") (name "Net-(U2-11)") (class "Default")
      (node (ref "C3") (pin "2") (pinfunction "2_2") (pintype "bidirectional"))
      (node (ref "U2") (pin "48") (pinfunction "11_48") (pintype "bidirectional"))
    )
    (net (code "198") (name "Net-(U2-12)") (class "Default")
      (node (ref "C4") (pin "2") (pinfunction "2_2") (pintype "bidirectional"))
      (node (ref "U2") (pin "47") (pinfunction "12_47") (pintype "bidirectional"))
    )
    (net (code "199") (name "Net-(U2-30)") (class "Default")
      (node (ref "L1") (pin "1") (pinfunction "1_1") (pintype "bidirectional"))
      (node (ref "U2") (pin "20") (pinfunction "30_20") (pintype "bidirectional"))
    )
    (net (code "200") (name "Net-(U2-31)") (class "Default")
      (node (ref "L1") (pin "2") (pinfunction "2_2") (pintype "bidirectional"))
      (node (ref "R6") (pin "1") (pinfunction "1_1") (pintype "bidirectional"))
      (node (ref "U2") (pin "19") (pinfunction "31_19") (pintype "bidirectional"))
    )
    (net (code "201") (name "Net-(U2-33)") (class "Default")
      (node (ref "L2") (pin "1") (pinfunction "1_1") (pintype "bidirectional"))
      (node (ref "U2") (pin "23") (pinfunction "33_23") (pintype "bidirectional"))
    )
    (net (code "202") (name "Net-(U2-36)") (class "Default")
      (node (ref "L3") (pin "1") (pinfunction "1_1") (pintype "bidirectional"))
      (node (ref "U2") (pin "31") (pinfunction "36_31") (pintype "bidirectional"))
    )
    (net (code "203") (name "Net-(U2-43)") (class "Default")
      (node (ref "R5") (pin "1") (pinfunction "1_1") (pintype "bidirectional"))
      (node (ref "R7") (pin "1") (pinfunction "1_1") (pintype "bidirectional"))
      (node (ref "R8") (pin "1") (pinfunction "1_1") (pintype "bidirectional"))
      (node (ref "U2") (pin "3") (pinfunction "43_3") (pintype "bidirectional"))
    )
    (net (code "204") (name "Net-(U3-1)") (class "Default")
      (node (ref "U3") (pin "2") (pinfunction "1_2") (pintype "bidirectional"))
      (node (ref "U5") (pin "R14") (pinfunction "36_R14") (pintype "bidirectional"))
    )
    (net (code "205") (name "Net-(U3-2)") (class "Default")
      (node (ref "R162") (pin "1") (pinfunction "1_1") (pintype "bidirectional"))
      (node (ref "U3") (pin "4") (pinfunction "2_4") (pintype "bidirectional"))
    )
    (net (code "206") (name "Net-(U4-5)") (class "Default")
      (node (ref "C19") (pin "1") (pinfunction "1_1") (pintype "bidirectional"))
      (node (ref "R10") (pin "1") (pinfunction "1_1") (pintype "bidirectional"))
      (node (ref "R11") (pin "2") (pinfunction "2_2") (pintype "bidirectional"))
      (node (ref "U4") (pin "4") (pinfunction "5_4") (pintype "bidirectional"))
    )
    (net (code "207") (name "Net-(U5A-1)") (class "Default")
      (node (ref "C21") (pin "2") (pinfunction "2_2") (pintype "bidirectional"))
      (node (ref "U5") (pin "A6") (pinfunction "1_A6") (pintype "bidirectional"))
      (node (ref "Y1") (pin "1") (pinfunction "1_1") (pintype "bidirectional"))
    )
    (net (code "208") (name "Net-(U5A-2)") (class "Default")
      (node (ref "C22") (pin "2") (pinfunction "2_2") (pintype "bidirectional"))
      (node (ref "U5") (pin "A4") (pinfunction "2_A4") (pintype "bidirectional"))
      (node (ref "Y1") (pin "4") (pinfunction "2_4") (pintype "bidirectional"))
    )
    (net (code "209") (name "Net-(U5A-3)") (class "Default")
      (node (ref "C25") (pin "1") (pinfunction "1_1") (pintype "bidirectional"))
      (node (ref "R17") (pin "1") (pinfunction "1_1") (pintype "bidirectional"))
      (node (ref "U5") (pin "V10") (pinfunction "3_V10") (pintype "bidirectional"))
      (node (ref "Y2") (pin "2") (pinfunction "2_2") (pintype "bidirectional"))
    )
    (net (code "210") (name "Net-(U5A-4)") (class "Default")
      (node (ref "C26") (pin "1") (pinfunction "1_1") (pintype "bidirectional"))
      (node (ref "R17") (pin "2") (pinfunction "2_2") (pintype "bidirectional"))
      (node (ref "U5") (pin "U11") (pinfunction "4_U11") (pintype "bidirectional"))
      (node (ref "Y2") (pin "1") (pinfunction "1_1") (pintype "bidirectional"))
    )
    (net (code "211") (name "Net-(U5A-11)") (class "Default")
      (node (ref "R161") (pin "1") (pinfunction "1_1") (pintype "bidirectional"))
      (node (ref "U5") (pin "T13") (pinfunction "11_T13") (pintype "bidirectional"))
    )
    (net (code "212") (name "Net-(U5A-32)") (class "Default")
      (node (ref "R160") (pin "1") (pinfunction "1_1") (pintype "bidirectional"))
      (node (ref "U5") (pin "R13") (pinfunction "32_R13") (pintype "bidirectional"))
    )
    (net (code "213") (name "Net-(U5A-43)") (class "Default")
      (node (ref "U5") (pin "V17") (pinfunction "43_V17") (pintype "bidirectional"))
      (node (ref "Y4") (pin "1") (pinfunction "1_1") (pintype "bidirectional"))
    )
    (net (code "214") (name "Net-(U5A-53)") (class "Default")
      (node (ref "R18") (pin "1") (pinfunction "1_1") (pintype "bidirectional"))
      (node (ref "U5") (pin "A15") (pinfunction "53_A15") (pintype "bidirectional"))
    )
    (net (code "215") (name "Net-(U5A-54)") (class "Default")
      (node (ref "R19") (pin "1") (pinfunction "1_1") (pintype "bidirectional"))
      (node (ref "U5") (pin "D14") (pinfunction "54_D14") (pintype "bidirectional"))
    )
    (net (code "216") (name "Net-(U5A-109)") (class "Default")
      (node (ref "C21") (pin "1") (pinfunction "1_1") (pintype "bidirectional"))
      (node (ref "C22") (pin "1") (pinfunction "1_1") (pintype "bidirectional"))
      (node (ref "U5") (pin "A5") (pinfunction "109_A5") (pintype "bidirectional"))
    )
    (net (code "217") (name "Net-(U5A-114)") (class "Default")
      (node (ref "R22") (pin "2") (pinfunction "2_2") (pintype "bidirectional"))
      (node (ref "U5") (pin "J3") (pinfunction "114_J3") (pintype "bidirectional"))
    )
    (net (code "218") (name "Net-(U5B-8)") (class "Default")
      (node (ref "R163") (pin "2") (pinfunction "2_2") (pintype "bidirectional"))
      (node (ref "R164") (pin "1") (pinfunction "1_1") (pintype "bidirectional"))
      (node (ref "U5") (pin "C9") (pinfunction "8_C9") (pintype "bidirectional"))
    )
    (net (code "219") (name "Net-(U5B-9)") (class "Default")
      (node (ref "C31") (pin "1") (pinfunction "1_1") (pintype "bidirectional"))
      (node (ref "C32") (pin "1") (pinfunction "1_1") (pintype "bidirectional"))
      (node (ref "C33") (pin "1") (pinfunction "1_1") (pintype "bidirectional"))
      (node (ref "R27") (pin "2") (pinfunction "2_2") (pintype "bidirectional"))
      (node (ref "U5") (pin "B9") (pinfunction "9_B9") (pintype "bidirectional"))
    )
    (net (code "220") (name "Net-(U5B-18)") (class "Default")
      (node (ref "R159") (pin "2") (pinfunction "2_2") (pintype "bidirectional"))
      (node (ref "U5") (pin "P15") (pinfunction "18_P15") (pintype "bidirectional"))
    )
    (net (code "221") (name "Net-(U5B-22)") (class "Default")
      (node (ref "R49") (pin "2") (pinfunction "2_2") (pintype "bidirectional"))
      (node (ref "U5") (pin "P17") (pinfunction "22_P17") (pintype "bidirectional"))
    )
    (net (code "222") (name "Net-(U5B-25)") (class "Default")
      (node (ref "FB8") (pin "1") (pinfunction "1_1") (pintype "bidirectional"))
      (node (ref "U5") (pin "T18") (pinfunction "25_T18") (pintype "bidirectional"))
    )
    (net (code "223") (name "Net-(U5B-42)") (class "Default")
      (node (ref "R28") (pin "1") (pinfunction "1_1") (pintype "bidirectional"))
      (node (ref "U5") (pin "H18") (pinfunction "42_H18") (pintype "bidirectional"))
    )
    (net (code "224") (name "Net-(U5B-67)") (class "Default")
      (node (ref "R45") (pin "1") (pinfunction "1_1") (pintype "bidirectional"))
      (node (ref "U5") (pin "V5") (pinfunction "67_V5") (pintype "bidirectional"))
    )
    (net (code "225") (name "Net-(U5B-68)") (class "Default")
      (node (ref "R46") (pin "1") (pinfunction "1_1") (pintype "bidirectional"))
      (node (ref "U5") (pin "U5") (pinfunction "68_U5") (pintype "bidirectional"))
    )
    (net (code "226") (name "Net-(U5B-69)") (class "Default")
      (node (ref "R47") (pin "1") (pinfunction "1_1") (pintype "bidirectional"))
      (node (ref "U5") (pin "R5") (pinfunction "69_R5") (pintype "bidirectional"))
    )
    (net (code "227") (name "Net-(U5B-70)") (class "Default")
      (node (ref "R48") (pin "1") (pinfunction "1_1") (pintype "bidirectional"))
      (node (ref "U5") (pin "R6") (pinfunction "70_R6") (pintype "bidirectional"))
    )
    (net (code "228") (name "Net-(U5B-83)") (class "Default")
      (node (ref "R51") (pin "2") (pinfunction "2_2") (pintype "bidirectional"))
      (node (ref "U5") (pin "B12") (pinfunction "83_B12") (pintype "bidirectional"))
    )
    (net (code "229") (name "Net-(U5B-86)") (class "Default")
      (node (ref "R50") (pin "2") (pinfunction "2_2") (pintype "bidirectional"))
      (node (ref "U5") (pin "C18") (pinfunction "86_C18") (pintype "bidirectional"))
    )
    (net (code "230") (name "Net-(U5C-68)") (class "Default")
      (node (ref "C89") (pin "1") (pinfunction "1_1") (pintype "bidirectional"))
      (node (ref "U5") (pin "D9") (pinfunction "68_D9") (pintype "bidirectional"))
    )
    (net (code "231") (name "Net-(U5C-73)") (class "Default")
      (node (ref "C104") (pin "1") (pinfunction "1_1") (pintype "bidirectional"))
      (node (ref "U5") (pin "D6") (pinfunction "73_D6") (pintype "bidirectional"))
    )
    (net (code "232") (name "Net-(U5C-76)") (class "Default")
      (node (ref "C91") (pin "1") (pinfunction "1_1") (pintype "bidirectional"))
      (node (ref "U5") (pin "C10") (pinfunction "76_C10") (pintype "bidirectional"))
    )
    (net (code "233") (name "Net-(U5C-77)") (class "Default")
      (node (ref "C90") (pin "1") (pinfunction "1_1") (pintype "bidirectional"))
      (node (ref "U5") (pin "D11") (pinfunction "77_D11") (pintype "bidirectional"))
    )
    (net (code "234") (name "Net-(U5C-99)") (class "Default")
      (node (ref "R54") (pin "2") (pinfunction "2_2") (pintype "bidirectional"))
      (node (ref "U5") (pin "B4") (pinfunction "99_B4") (pintype "bidirectional"))
    )
    (net (code "235") (name "Net-(U5C-100)") (class "Default")
      (node (ref "TP3") (pin "1") (pinfunction "1_1") (pintype "bidirectional"))
      (node (ref "U5") (pin "A3") (pinfunction "100_A3") (pintype "bidirectional"))
    )
    (net (code "236") (name "Net-(U5C-121)") (class "Default")
      (node (ref "TP2") (pin "1") (pinfunction "1_1") (pintype "bidirectional"))
      (node (ref "U5") (pin "A2") (pinfunction "121_A2") (pintype "bidirectional"))
    )
    (net (code "237") (name "Net-(U6-Pad2)") (class "Default")
      (node (ref "U6") (pin "2") (pinfunction "2_2") (pintype "bidirectional"))
      (node (ref "U6") (pin "3") (pinfunction "3_3") (pintype "bidirectional"))
    )
    (net (code "238") (name "Net-(U8-5)") (class "Default")
      (node (ref "C35") (pin "1") (pinfunction "1_1") (pintype "bidirectional"))
      (node (ref "FB7") (pin "1") (pinfunction "1_1") (pintype "bidirectional"))
      (node (ref "FB8") (pin "2") (pinfunction "2_2") (pintype "bidirectional"))
      (node (ref "U8") (pin "6") (pinfunction "5_6") (pintype "bidirectional"))
      (node (ref "U8") (pin "7") (pinfunction "6_7") (pintype "bidirectional"))
      (node (ref "U8") (pin "8") (pinfunction "7_8") (pintype "bidirectional"))
      (node (ref "U9") (pin "6") (pinfunction "3_6") (pintype "bidirectional"))
    )
    (net (code "239") (name "Net-(U11-47)") (class "Default")
      (node (ref "R148") (pin "1") (pinfunction "1_1") (pintype "bidirectional"))
      (node (ref "U11") (pin "34") (pinfunction "47_34") (pintype "bidirectional"))
    )
    (net (code "240") (name "Net-(U11-51)") (class "Default")
      (node (ref "R149") (pin "1") (pinfunction "1_1") (pintype "bidirectional"))
      (node (ref "U11") (pin "49") (pinfunction "51_49") (pintype "bidirectional"))
    )
    (net (code "241") (name "Net-(U12-81)") (class "Default")
      (node (ref "R99") (pin "2") (pinfunction "2_2") (pintype "bidirectional"))
      (node (ref "U12") (pin "L8") (pinfunction "81_L8") (pintype "bidirectional"))
    )
    (net (code "242") (name "Net-(U13-30)") (class "Default")
      (node (ref "C125") (pin "1") (pinfunction "1_1") (pintype "bidirectional"))
      (node (ref "U13") (pin "C2") (pinfunction "30_C2") (pintype "bidirectional"))
    )
    (net (code "243") (name "Net-(U14-7)") (class "Default")
      (node (ref "R129") (pin "2") (pinfunction "2_2") (pintype "bidirectional"))
      (node (ref "U14") (pin "26") (pinfunction "7_26") (pintype "bidirectional"))
    )
    (net (code "244") (name "Net-(U14-10)") (class "Default")
      (node (ref "R134") (pin "2") (pinfunction "2_2") (pintype "bidirectional"))
      (node (ref "U14") (pin "20") (pinfunction "10_20") (pintype "bidirectional"))
    )
    (net (code "245") (name "Net-(U14-17)") (class "Default")
      (node (ref "R139") (pin "2") (pinfunction "2_2") (pintype "bidirectional"))
      (node (ref "U14") (pin "14") (pinfunction "17_14") (pintype "bidirectional"))
    )
    (net (code "246") (name "Net-(U14-19)") (class "Default")
      (node (ref "R140") (pin "2") (pinfunction "2_2") (pintype "bidirectional"))
      (node (ref "R142") (pin "2") (pinfunction "2_2") (pintype "bidirectional"))
      (node (ref "U14") (pin "5") (pinfunction "19_5") (pintype "bidirectional"))
    )
    (net (code "247") (name "Net-(U14-20)") (class "Default")
      (node (ref "R141") (pin "1") (pinfunction "1_1") (pintype "bidirectional"))
      (node (ref "R143") (pin "1") (pinfunction "1_1") (pintype "bidirectional"))
      (node (ref "U14") (pin "4") (pinfunction "20_4") (pintype "bidirectional"))
    )
    (net (code "248") (name "Net-(U14-22)") (class "Default")
      (node (ref "R144") (pin "1") (pinfunction "1_1") (pintype "bidirectional"))
      (node (ref "U14") (pin "32") (pinfunction "22_32") (pintype "bidirectional"))
    )
    (net (code "249") (name "Net-(U14-26)") (class "Default")
      (node (ref "C134") (pin "1") (pinfunction "1_1") (pintype "bidirectional"))
      (node (ref "C136") (pin "1") (pinfunction "1_1") (pintype "bidirectional"))
      (node (ref "U14") (pin "6") (pinfunction "26_6") (pintype "bidirectional"))
    )
    (net (code "250") (name "Net-(U14-31)") (class "Default")
      (node (ref "R145") (pin "1") (pinfunction "1_1") (pintype "bidirectional"))
      (node (ref "U14") (pin "18") (pinfunction "31_18") (pintype "bidirectional"))
    )
    (net (code "251") (name "Net-(U15-1)") (class "Default")
      (node (ref "J1") (pin "4") (pinfunction "4_4") (pintype "bidirectional"))
      (node (ref "R165") (pin "1") (pinfunction "1_1") (pintype "bidirectional"))
      (node (ref "U15") (pin "2") (pinfunction "1_2") (pintype "bidirectional"))
    )
    (net (code "252") (name "Net-(U15-6)") (class "Default")
      (node (ref "U15") (pin "5") (pinfunction "6_5") (pintype "bidirectional"))
      (node (ref "U5") (pin "E16") (pinfunction "11_E16") (pintype "bidirectional"))
    )
    (net (code "253") (name "Net-(U15-7)") (class "Default")
      (node (ref "J1") (pin "5") (pinfunction "5_5") (pintype "bidirectional"))
      (node (ref "U15") (pin "3") (pinfunction "7_3") (pintype "bidirectional"))
    )
    (net (code "254") (name "Net-(U15-8)") (class "Default")
      (node (ref "U15") (pin "6") (pinfunction "8_6") (pintype "bidirectional"))
      (node (ref "U5") (pin "E15") (pinfunction "12_E15") (pintype "bidirectional"))
    )
    (net (code "255") (name "Net-(Y4-4)") (class "Default")
      (node (ref "R167") (pin "1") (pinfunction "1_1") (pintype "bidirectional"))
      (node (ref "Y4") (pin "3") (pinfunction "4_3") (pintype "bidirectional"))
    )
    (net (code "256") (name "PMIC_INT") (class "Default")
      (node (ref "R1") (pin "2") (pinfunction "2_2") (pintype "bidirectional"))
      (node (ref "U2") (pin "45") (pinfunction "28_45") (pintype "bidirectional"))
      (node (ref "U5") (pin "B18") (pinfunction "52_B18") (pintype "bidirectional"))
    )
    (net (code "257") (name "PMIC_PGOOD") (class "Default")
      (node (ref "U2") (pin "26") (pinfunction "25_26") (pintype "bidirectional"))
      (node (ref "U5") (pin "B15") (pinfunction "50_B15") (pintype "bidirectional"))
    )
    (net (code "258") (name "PMIC_POWR_EN") (class "Default")
      (node (ref "U2") (pin "9") (pinfunction "13_9") (pintype "bidirectional"))
      (node (ref "U5") (pin "C6") (pinfunction "76_C6") (pintype "bidirectional"))
    )
    (net (code "259") (name "PWR_BUT") (class "Default")
      (node (ref "P9") (pin "9") (pinfunction "28_9") (pintype "bidirectional"))
      (node (ref "S3") (pin "2") (pinfunction "2_2") (pintype "bidirectional"))
      (node (ref "S3") (pin "4") (pinfunction "4_4") (pintype "bidirectional"))
      (node (ref "U2") (pin "25") (pinfunction "15_25") (pintype "bidirectional"))
    )
    (net (code "260") (name "REFCLKO") (class "Default")
      (node (ref "R118") (pin "1") (pinfunction "1_1") (pintype "bidirectional"))
      (node (ref "R124") (pin "2") (pinfunction "2_2") (pintype "bidirectional"))
      (node (ref "R131") (pin "2") (pinfunction "2_2") (pintype "bidirectional"))
      (node (ref "U14") (pin "7") (pinfunction "8_7") (pintype "bidirectional"))
    )
    (net (code "261") (name "RXD0\\MODE0\\") (class "Default")
      (node (ref "R112") (pin "1") (pinfunction "1_1") (pintype "bidirectional"))
      (node (ref "R128") (pin "2") (pinfunction "2_2") (pintype "bidirectional"))
      (node (ref "U14") (pin "11") (pinfunction "6_11") (pintype "bidirectional"))
    )
    (net (code "262") (name "RXD1\\MODE1\\") (class "Default")
      (node (ref "R114") (pin "1") (pinfunction "1_1") (pintype "bidirectional"))
      (node (ref "R127") (pin "2") (pinfunction "2_2") (pintype "bidirectional"))
      (node (ref "U14") (pin "10") (pinfunction "5_10") (pintype "bidirectional"))
    )
    (net (code "263") (name "RXD2\\RMIISEL\\") (class "Default")
      (node (ref "R117") (pin "1") (pinfunction "1_1") (pintype "bidirectional"))
      (node (ref "R126") (pin "2") (pinfunction "2_2") (pintype "bidirectional"))
      (node (ref "U14") (pin "9") (pinfunction "4_9") (pintype "bidirectional"))
    )
    (net (code "264") (name "RXD3\\PHYAD2\\") (class "Default")
      (node (ref "R116") (pin "1") (pinfunction "1_1") (pintype "bidirectional"))
      (node (ref "R125") (pin "2") (pinfunction "2_2") (pintype "bidirectional"))
      (node (ref "U14") (pin "8") (pinfunction "3_8") (pintype "bidirectional"))
    )
    (net (code "265") (name "RXER\\PHYAD0\\") (class "Default")
      (node (ref "R115") (pin "1") (pinfunction "1_1") (pintype "bidirectional"))
      (node (ref "R133") (pin "2") (pinfunction "2_2") (pintype "bidirectional"))
      (node (ref "U14") (pin "13") (pinfunction "9_13") (pintype "bidirectional"))
    )
    (net (code "266") (name "SPI1_CS0") (class "Default")
      (node (ref "P9") (pin "28") (pinfunction "14_28") (pintype "bidirectional"))
      (node (ref "U11") (pin "25") (pinfunction "46_25") (pintype "bidirectional"))
      (node (ref "U5") (pin "C12") (pinfunction "82_C12") (pintype "bidirectional"))
    )
    (net (code "267") (name "SPI1_D0") (class "Default")
      (node (ref "P9") (pin "29") (pinfunction "38_29") (pintype "bidirectional"))
      (node (ref "U11") (pin "24") (pinfunction "45_24") (pintype "bidirectional"))
      (node (ref "U5") (pin "B13") (pinfunction "80_B13") (pintype "bidirectional"))
    )
    (net (code "268") (name "SPI1_D1") (class "Default")
      (node (ref "P9") (pin "30") (pinfunction "15_30") (pintype "bidirectional"))
      (node (ref "U5") (pin "D12") (pinfunction "81_D12") (pintype "bidirectional"))
    )
    (net (code "269") (name "SPI1_SCLK") (class "Default")
      (node (ref "P9") (pin "31") (pinfunction "39_31") (pintype "bidirectional"))
      (node (ref "U11") (pin "23") (pinfunction "44_23") (pintype "bidirectional"))
      (node (ref "U5") (pin "A13") (pinfunction "79_A13") (pintype "bidirectional"))
    )
    (net (code "270") (name "SYS_5V") (class "Default")
      (node (ref "C10") (pin "2") (pinfunction "2_2") (pintype "bidirectional"))
      (node (ref "C13") (pin "2") (pinfunction "2_2") (pintype "bidirectional"))
      (node (ref "C17") (pin "1") (pinfunction "1_1") (pintype "bidirectional"))
      (node (ref "C34") (pin "1") (pinfunction "1_1") (pintype "bidirectional"))
      (node (ref "C7") (pin "2") (pinfunction "2_2") (pintype "bidirectional"))
      (node (ref "C8") (pin "2") (pinfunction "2_2") (pintype "bidirectional"))
      (node (ref "P9") (pin "7") (pinfunction "27_7") (pintype "bidirectional"))
      (node (ref "P9") (pin "8") (pinfunction "4_8") (pintype "bidirectional"))
      (node (ref "R71") (pin "1") (pinfunction "1_1") (pintype "bidirectional"))
      (node (ref "R72") (pin "1") (pinfunction "1_1") (pintype "bidirectional"))
      (node (ref "R73") (pin "1") (pinfunction "1_1") (pintype "bidirectional"))
      (node (ref "R74") (pin "1") (pinfunction "1_1") (pintype "bidirectional"))
      (node (ref "RT1") (pin "1") (pinfunction "1_1") (pintype "bidirectional"))
      (node (ref "U2") (pin "2") (pinfunction "42_2") (pintype "bidirectional"))
      (node (ref "U2") (pin "21") (pinfunction "29_21") (pintype "bidirectional"))
      (node (ref "U2") (pin "22") (pinfunction "32_22") (pintype "bidirectional"))
      (node (ref "U2") (pin "32") (pinfunction "35_32") (pintype "bidirectional"))
      (node (ref "U2") (pin "39") (pinfunction "40_39") (pintype "bidirectional"))
      (node (ref "U2") (pin "42") (pinfunction "41_42") (pintype "bidirectional"))
      (node (ref "U2") (pin "7") (pinfunction "3_7") (pintype "bidirectional"))
      (node (ref "U2") (pin "8") (pinfunction "4_8") (pintype "bidirectional"))
      (node (ref "U4") (pin "2") (pinfunction "1_2") (pintype "bidirectional"))
      (node (ref "U8") (pin "2") (pinfunction "2_2") (pintype "bidirectional"))
      (node (ref "U8") (pin "3") (pinfunction "3_3") (pintype "bidirectional"))
    )
    (net (code "271") (name "SYS_RESETN") (class "Default")
      (node (ref "C24") (pin "1") (pinfunction "1_1") (pintype "bidirectional"))
      (node (ref "C30") (pin "1") (pinfunction "1_1") (pintype "bidirectional"))
      (node (ref "P2") (pin "15") (pinfunction "8_15") (pintype "bidirectional"))
      (node (ref "P9") (pin "10") (pinfunction "5_10") (pintype "bidirectional"))
      (node (ref "R14") (pin "2") (pinfunction "2_2") (pintype "bidirectional"))
      (node (ref "S1") (pin "2") (pinfunction "2_2") (pintype "bidirectional"))
      (node (ref "S1") (pin "4") (pinfunction "4_4") (pintype "bidirectional"))
      (node (ref "U14") (pin "19") (pinfunction "18_19") (pintype "bidirectional"))
      (node (ref "U5") (pin "A10") (pinfunction "51_A10") (pintype "bidirectional"))
    )
    (net (code "272") (name "TIMER4") (class "Default")
      (node (ref "P8") (pin "7") (pinfunction "27_7") (pintype "bidirectional"))
      (node (ref "U5") (pin "R7") (pinfunction "12_R7") (pintype "bidirectional"))
    )
    (net (code "273") (name "TIMER5") (class "Default")
      (node (ref "P8") (pin "9") (pinfunction "28_9") (pintype "bidirectional"))
      (node (ref "U5") (pin "T6") (pinfunction "13_T6") (pintype "bidirectional"))
    )
    (net (code "274") (name "TIMER6") (class "Default")
      (node (ref "P8") (pin "10") (pinfunction "5_10") (pintype "bidirectional"))
      (node (ref "U5") (pin "U6") (pinfunction "9_U6") (pintype "bidirectional"))
    )
    (net (code "275") (name "TIMER7") (class "Default")
      (node (ref "P8") (pin "8") (pinfunction "4_8") (pintype "bidirectional"))
      (node (ref "U5") (pin "T7") (pinfunction "10_T7") (pintype "bidirectional"))
    )
    (net (code "276") (name "UART1_RXD") (class "Default")
      (node (ref "P9") (pin "26") (pinfunction "13_26") (pintype "bidirectional"))
      (node (ref "U5") (pin "D16") (pinfunction "46_D16") (pintype "bidirectional"))
    )
    (net (code "277") (name "UART1_TXD") (class "Default")
      (node (ref "P9") (pin "24") (pinfunction "12_24") (pintype "bidirectional"))
      (node (ref "U5") (pin "D15") (pinfunction "45_D15") (pintype "bidirectional"))
    )
    (net (code "278") (name "UART2_RXD") (class "Default")
      (node (ref "P9") (pin "22") (pinfunction "11_22") (pintype "bidirectional"))
      (node (ref "U5") (pin "A17") (pinfunction "71_A17") (pintype "bidirectional"))
    )
    (net (code "279") (name "UART2_TXD") (class "Default")
      (node (ref "P9") (pin "21") (pinfunction "34_21") (pintype "bidirectional"))
      (node (ref "U5") (pin "B17") (pinfunction "72_B17") (pintype "bidirectional"))
    )
    (net (code "280") (name "UART4_RXD") (class "Default")
      (node (ref "P9") (pin "11") (pinfunction "29_11") (pintype "bidirectional"))
      (node (ref "U5") (pin "T17") (pinfunction "15_T17") (pintype "bidirectional"))
    )
    (net (code "281") (name "UART4_TXD") (class "Default")
      (node (ref "P9") (pin "13") (pinfunction "30_13") (pintype "bidirectional"))
      (node (ref "U5") (pin "U17") (pinfunction "111_U17") (pintype "bidirectional"))
    )
    (net (code "282") (name "USB0_DM") (class "Default")
      (node (ref "P4") (pin "2") (pinfunction "1_2") (pintype "bidirectional"))
      (node (ref "U10") (pin "2") (pinfunction "2_2") (pintype "bidirectional"))
      (node (ref "U5") (pin "N18") (pinfunction "16_N18") (pintype "bidirectional"))
    )
    (net (code "283") (name "USB0_DP") (class "Default")
      (node (ref "P4") (pin "3") (pinfunction "2_3") (pintype "bidirectional"))
      (node (ref "U10") (pin "1") (pinfunction "1_1") (pintype "bidirectional"))
      (node (ref "U5") (pin "N17") (pinfunction "15_N17") (pintype "bidirectional"))
    )
    (net (code "284") (name "USB0_ID") (class "Default")
      (node (ref "P4") (pin "4") (pinfunction "4_4") (pintype "bidirectional"))
      (node (ref "U10") (pin "3") (pinfunction "6_3") (pintype "bidirectional"))
      (node (ref "U5") (pin "P16") (pinfunction "23_P16") (pintype "bidirectional"))
    )
    (net (code "285") (name "USB1_DM") (class "Default")
      (node (ref "P3") (pin "2") (pinfunction "3_2") (pintype "bidirectional"))
      (node (ref "U5") (pin "R18") (pinfunction "21_R18") (pintype "bidirectional"))
      (node (ref "U9") (pin "2") (pinfunction "2_2") (pintype "bidirectional"))
    )
    (net (code "286") (name "USB1_DP") (class "Default")
      (node (ref "P3") (pin "3") (pinfunction "2_3") (pintype "bidirectional"))
      (node (ref "U5") (pin "R17") (pinfunction "20_R17") (pintype "bidirectional"))
      (node (ref "U9") (pin "1") (pinfunction "1_1") (pintype "bidirectional"))
    )
    (net (code "287") (name "USB1_DRVVBUS") (class "Default")
      (node (ref "R53") (pin "1") (pinfunction "1_1") (pintype "bidirectional"))
      (node (ref "U5") (pin "F15") (pinfunction "26_F15") (pintype "bidirectional"))
      (node (ref "U8") (pin "4") (pinfunction "4_4") (pintype "bidirectional"))
    )
    (net (code "288") (name "USB1_OCN") (class "Default")
      (node (ref "R52") (pin "2") (pinfunction "2_2") (pintype "bidirectional"))
      (node (ref "U5") (pin "T16") (pinfunction "42_T16") (pintype "bidirectional"))
      (node (ref "U8") (pin "5") (pinfunction "8_5") (pintype "bidirectional"))
    )
    (net (code "289") (name "USB_DC") (class "Default")
      (node (ref "C1") (pin "2") (pinfunction "2_2") (pintype "bidirectional"))
      (node (ref "C36") (pin "1") (pinfunction "1_1") (pintype "bidirectional"))
      (node (ref "P4") (pin "1") (pinfunction "3_1") (pintype "bidirectional"))
      (node (ref "R159") (pin "1") (pinfunction "1_1") (pintype "bidirectional"))
      (node (ref "U10") (pin "6") (pinfunction "3_6") (pintype "bidirectional"))
      (node (ref "U2") (pin "12") (pinfunction "2_12") (pintype "bidirectional"))
    )
    (net (code "290") (name "USR0") (class "Default")
      (node (ref "Q1") (pin "2") (pinfunction "3_2") (pintype "bidirectional"))
      (node (ref "R76") (pin "1") (pinfunction "1_1") (pintype "bidirectional"))
      (node (ref "U5") (pin "V15") (pinfunction "37_V15") (pintype "bidirectional"))
    )
    (net (code "291") (name "USR1") (class "Default")
      (node (ref "Q1") (pin "5") (pinfunction "3_5") (pintype "bidirectional"))
      (node (ref "R77") (pin "1") (pinfunction "1_1") (pintype "bidirectional"))
      (node (ref "U5") (pin "U15") (pinfunction "38_U15") (pintype "bidirectional"))
    )
    (net (code "292") (name "USR2") (class "Default")
      (node (ref "Q2") (pin "2") (pinfunction "3_2") (pintype "bidirectional"))
      (node (ref "R78") (pin "1") (pinfunction "1_1") (pintype "bidirectional"))
      (node (ref "U5") (pin "T15") (pinfunction "39_T15") (pintype "bidirectional"))
    )
    (net (code "293") (name "USR3") (class "Default")
      (node (ref "Q2") (pin "5") (pinfunction "3_5") (pintype "bidirectional"))
      (node (ref "R79") (pin "1") (pinfunction "1_1") (pintype "bidirectional"))
      (node (ref "U5") (pin "V16") (pinfunction "40_V16") (pintype "bidirectional"))
    )
    (net (code "294") (name "VCC_BAR_HDMI_1V8") (class "Default")
      (node (ref "C144") (pin "1") (pinfunction "1_1") (pintype "bidirectional"))
      (node (ref "C145") (pin "1") (pinfunction "1_1") (pintype "bidirectional"))
      (node (ref "C146") (pin "1") (pinfunction "1_1") (pintype "bidirectional"))
      (node (ref "C147") (pin "1") (pinfunction "1_1") (pintype "bidirectional"))
      (node (ref "C148") (pin "1") (pinfunction "1_1") (pintype "bidirectional"))
      (node (ref "C149") (pin "1") (pinfunction "1_1") (pintype "bidirectional"))
      (node (ref "C150") (pin "1") (pinfunction "1_1") (pintype "bidirectional"))
      (node (ref "C151") (pin "1") (pinfunction "1_1") (pintype "bidirectional"))
      (node (ref "FB5") (pin "1") (pinfunction "1_1") (pintype "bidirectional"))
      (node (ref "U11") (pin "14") (pinfunction "49_14") (pintype "bidirectional"))
      (node (ref "U11") (pin "29") (pinfunction "56_29") (pintype "bidirectional"))
      (node (ref "U11") (pin "35") (pinfunction "53_35") (pintype "bidirectional"))
      (node (ref "U11") (pin "36") (pinfunction "54_36") (pintype "bidirectional"))
      (node (ref "U11") (pin "41") (pinfunction "61_41") (pintype "bidirectional"))
      (node (ref "U11") (pin "46") (pinfunction "62_46") (pintype "bidirectional"))
      (node (ref "U11") (pin "47") (pinfunction "52_47") (pintype "bidirectional"))
      (node (ref "U11") (pin "48") (pinfunction "63_48") (pintype "bidirectional"))
      (node (ref "U11") (pin "5") (pinfunction "55_5") (pintype "bidirectional"))
      (node (ref "U11") (pin "55") (pinfunction "64_55") (pintype "bidirectional"))
    )
    (net (code "295") (name "VDDS") (class "Default")
      (node (ref "C80") (pin "1") (pinfunction "1_1") (pintype "bidirectional"))
      (node (ref "C81") (pin "1") (pinfunction "1_1") (pintype "bidirectional"))
      (node (ref "C82") (pin "1") (pinfunction "1_1") (pintype "bidirectional"))
      (node (ref "C83") (pin "1") (pinfunction "1_1") (pintype "bidirectional"))
      (node (ref "C84") (pin "1") (pinfunction "1_1") (pintype "bidirectional"))
      (node (ref "C85") (pin "1") (pinfunction "1_1") (pintype "bidirectional"))
      (node (ref "R8") (pin "2") (pinfunction "2_2") (pintype "bidirectional"))
      (node (ref "R9") (pin "1") (pinfunction "1_1") (pintype "bidirectional"))
      (node (ref "U5") (pin "E14") (pinfunction "63_E14") (pintype "bidirectional"))
      (node (ref "U5") (pin "E6") (pinfunction "62_E6") (pintype "bidirectional"))
      (node (ref "U5") (pin "F9") (pinfunction "64_F9") (pintype "bidirectional"))
      (node (ref "U5") (pin "K13") (pinfunction "65_K13") (pintype "bidirectional"))
      (node (ref "U5") (pin "N6") (pinfunction "66_N6") (pintype "bidirectional"))
      (node (ref "U5") (pin "P14") (pinfunction "120_P14") (pintype "bidirectional"))
      (node (ref "U5") (pin "P9") (pinfunction "67_P9") (pintype "bidirectional"))
    )
    (net (code "296") (name "VDDS_DDR") (class "Default")
      (node (ref "C100") (pin "1") (pinfunction "1_1") (pintype "bidirectional"))
      (node (ref "C101") (pin "1") (pinfunction "1_1") (pintype "bidirectional"))
      (node (ref "C102") (pin "1") (pinfunction "1_1") (pintype "bidirectional"))
      (node (ref "C103") (pin "1") (pinfunction "1_1") (pintype "bidirectional"))
      (node (ref "C107") (pin "1") (pinfunction "1_1") (pintype "bidirectional"))
      (node (ref "C108") (pin "1") (pinfunction "1_1") (pintype "bidirectional"))
      (node (ref "C109") (pin "1") (pinfunction "1_1") (pintype "bidirectional"))
      (node (ref "C110") (pin "1") (pinfunction "1_1") (pintype "bidirectional"))
      (node (ref "C111") (pin "1") (pinfunction "1_1") (pintype "bidirectional"))
      (node (ref "C112") (pin "1") (pinfunction "1_1") (pintype "bidirectional"))
      (node (ref "C113") (pin "1") (pinfunction "1_1") (pintype "bidirectional"))
      (node (ref "C114") (pin "1") (pinfunction "1_1") (pintype "bidirectional"))
      (node (ref "C115") (pin "1") (pinfunction "1_1") (pintype "bidirectional"))
      (node (ref "C116") (pin "1") (pinfunction "1_1") (pintype "bidirectional"))
      (node (ref "C117") (pin "1") (pinfunction "1_1") (pintype "bidirectional"))
      (node (ref "C118") (pin "2") (pinfunction "2_2") (pintype "bidirectional"))
      (node (ref "C119") (pin "1") (pinfunction "1_1") (pintype "bidirectional"))
      (node (ref "C120") (pin "1") (pinfunction "1_1") (pintype "bidirectional"))
      (node (ref "C121") (pin "1") (pinfunction "1_1") (pintype "bidirectional"))
      (node (ref "C122") (pin "2") (pinfunction "2_2") (pintype "bidirectional"))
      (node (ref "C9") (pin "2") (pinfunction "2_2") (pintype "bidirectional"))
      (node (ref "C95") (pin "2") (pinfunction "2_2") (pintype "bidirectional"))
      (node (ref "C96") (pin "2") (pinfunction "2_2") (pintype "bidirectional"))
      (node (ref "C97") (pin "1") (pinfunction "1_1") (pintype "bidirectional"))
      (node (ref "C98") (pin "1") (pinfunction "1_1") (pintype "bidirectional"))
      (node (ref "C99") (pin "1") (pinfunction "1_1") (pintype "bidirectional"))
      (node (ref "R6") (pin "2") (pinfunction "2_2") (pintype "bidirectional"))
      (node (ref "R97") (pin "1") (pinfunction "1_1") (pintype "bidirectional"))
      (node (ref "R98") (pin "1") (pinfunction "1_1") (pintype "bidirectional"))
      (node (ref "U12") (pin "A1") (pinfunction "44_A1") (pintype "bidirectional"))
      (node (ref "U12") (pin "A8") (pinfunction "45_A8") (pintype "bidirectional"))
      (node (ref "U12") (pin "B2") (pinfunction "49_B2") (pintype "bidirectional"))
      (node (ref "U12") (pin "C1") (pinfunction "46_C1") (pintype "bidirectional"))
      (node (ref "U12") (pin "C9") (pinfunction "47_C9") (pintype "bidirectional"))
      (node (ref "U12") (pin "D2") (pinfunction "48_D2") (pintype "bidirectional"))
      (node (ref "U12") (pin "D9") (pinfunction "64_D9") (pintype "bidirectional"))
      (node (ref "U12") (pin "E9") (pinfunction "66_E9") (pintype "bidirectional"))
      (node (ref "U12") (pin "F1") (pinfunction "67_F1") (pintype "bidirectional"))
      (node (ref "U12") (pin "G7") (pinfunction "50_G7") (pintype "bidirectional"))
      (node (ref "U12") (pin "H2") (pinfunction "72_H2") (pintype "bidirectional"))
      (node (ref "U12") (pin "H9") (pinfunction "73_H9") (pintype "bidirectional"))
      (node (ref "U12") (pin "K2") (pinfunction "78_K2") (pintype "bidirectional"))
      (node (ref "U12") (pin "K8") (pinfunction "79_K8") (pintype "bidirectional"))
      (node (ref "U12") (pin "N1") (pinfunction "87_N1") (pintype "bidirectional"))
      (node (ref "U12") (pin "N9") (pinfunction "88_N9") (pintype "bidirectional"))
      (node (ref "U12") (pin "R1") (pinfunction "91_R1") (pintype "bidirectional"))
      (node (ref "U12") (pin "R9") (pinfunction "92_R9") (pintype "bidirectional"))
      (node (ref "U5") (pin "E5") (pinfunction "90_E5") (pintype "bidirectional"))
      (node (ref "U5") (pin "F5") (pinfunction "91_F5") (pintype "bidirectional"))
      (node (ref "U5") (pin "G5") (pinfunction "92_G5") (pintype "bidirectional"))
      (node (ref "U5") (pin "H5") (pinfunction "93_H5") (pintype "bidirectional"))
      (node (ref "U5") (pin "J5") (pinfunction "89_J5") (pintype "bidirectional"))
      (node (ref "U5") (pin "K5") (pinfunction "94_K5") (pintype "bidirectional"))
      (node (ref "U5") (pin "L5") (pinfunction "95_L5") (pintype "bidirectional"))
    )
    (net (code "297") (name "VDD_1V8") (class "Default")
      (node (ref "C14") (pin "2") (pinfunction "2_2") (pintype "bidirectional"))
      (node (ref "C78") (pin "1") (pinfunction "1_1") (pintype "bidirectional"))
      (node (ref "C86") (pin "1") (pinfunction "1_1") (pintype "bidirectional"))
      (node (ref "C88") (pin "1") (pinfunction "1_1") (pintype "bidirectional"))
      (node (ref "FB1") (pin "1") (pinfunction "1_1") (pintype "bidirectional"))
      (node (ref "FB2") (pin "2") (pinfunction "2_2") (pintype "bidirectional"))
      (node (ref "FB5") (pin "2") (pinfunction "2_2") (pintype "bidirectional"))
      (node (ref "R9") (pin "2") (pinfunction "2_2") (pintype "bidirectional"))
      (node (ref "U2") (pin "40") (pinfunction "38_40") (pintype "bidirectional"))
      (node (ref "U5") (pin "D10") (pinfunction "75_D10") (pintype "bidirectional"))
      (node (ref "U5") (pin "E9") (pinfunction "69_E9") (pintype "bidirectional"))
      (node (ref "U5") (pin "N16") (pinfunction "84_N16") (pintype "bidirectional"))
      (node (ref "U5") (pin "R16") (pinfunction "81_R16") (pintype "bidirectional"))
    )
    (net (code "298") (name "VDD_3V3A") (class "Default")
      (node (ref "C15") (pin "2") (pinfunction "2_2") (pintype "bidirectional"))
      (node (ref "C152") (pin "1") (pinfunction "1_1") (pintype "bidirectional"))
      (node (ref "C158") (pin "1") (pinfunction "1_1") (pintype "bidirectional"))
      (node (ref "C159") (pin "1") (pinfunction "1_1") (pintype "bidirectional"))
      (node (ref "C27") (pin "1") (pinfunction "1_1") (pintype "bidirectional"))
      (node (ref "C37") (pin "1") (pinfunction "1_1") (pintype "bidirectional"))
      (node (ref "C38") (pin "1") (pinfunction "1_1") (pintype "bidirectional"))
      (node (ref "C56") (pin "2") (pinfunction "2_2") (pintype "bidirectional"))
      (node (ref "C57") (pin "2") (pinfunction "2_2") (pintype "bidirectional"))
      (node (ref "C58") (pin "1") (pinfunction "1_1") (pintype "bidirectional"))
      (node (ref "C59") (pin "1") (pinfunction "1_1") (pintype "bidirectional"))
      (node (ref "C60") (pin "2") (pinfunction "2_2") (pintype "bidirectional"))
      (node (ref "C61") (pin "2") (pinfunction "2_2") (pintype "bidirectional"))
      (node (ref "C66") (pin "1") (pinfunction "1_1") (pintype "bidirectional"))
      (node (ref "C67") (pin "1") (pinfunction "1_1") (pintype "bidirectional"))
      (node (ref "C68") (pin "2") (pinfunction "2_2") (pintype "bidirectional"))
      (node (ref "C69") (pin "2") (pinfunction "2_2") (pintype "bidirectional"))
      (node (ref "C70") (pin "2") (pinfunction "2_2") (pintype "bidirectional"))
      (node (ref "C71") (pin "2") (pinfunction "2_2") (pintype "bidirectional"))
      (node (ref "C72") (pin "2") (pinfunction "2_2") (pintype "bidirectional"))
      (node (ref "C73") (pin "2") (pinfunction "2_2") (pintype "bidirectional"))
      (node (ref "C74") (pin "2") (pinfunction "2_2") (pintype "bidirectional"))
      (node (ref "C75") (pin "2") (pinfunction "2_2") (pintype "bidirectional"))
      (node (ref "C76") (pin "2") (pinfunction "2_2") (pintype "bidirectional"))
      (node (ref "C77") (pin "1") (pinfunction "1_1") (pintype "bidirectional"))
      (node (ref "C87") (pin "1") (pinfunction "1_1") (pintype "bidirectional"))
      (node (ref "R1") (pin "1") (pinfunction "1_1") (pintype "bidirectional"))
      (node (ref "R14") (pin "1") (pinfunction "1_1") (pintype "bidirectional"))
      (node (ref "R156") (pin "1") (pinfunction "1_1") (pintype "bidirectional"))
      (node (ref "R3") (pin "1") (pinfunction "1_1") (pintype "bidirectional"))
      (node (ref "R4") (pin "1") (pinfunction "1_1") (pintype "bidirectional"))
      (node (ref "R52") (pin "1") (pinfunction "1_1") (pintype "bidirectional"))
      (node (ref "R55") (pin "1") (pinfunction "1_1") (pintype "bidirectional"))
      (node (ref "R56") (pin "1") (pinfunction "1_1") (pintype "bidirectional"))
      (node (ref "R57") (pin "1") (pinfunction "1_1") (pintype "bidirectional"))
      (node (ref "R58") (pin "1") (pinfunction "1_1") (pintype "bidirectional"))
      (node (ref "R59") (pin "1") (pinfunction "1_1") (pintype "bidirectional"))
      (node (ref "R60") (pin "1") (pinfunction "1_1") (pintype "bidirectional"))
      (node (ref "R61") (pin "1") (pinfunction "1_1") (pintype "bidirectional"))
      (node (ref "R62") (pin "1") (pinfunction "1_1") (pintype "bidirectional"))
      (node (ref "R63") (pin "1") (pinfunction "1_1") (pintype "bidirectional"))
      (node (ref "R64") (pin "1") (pinfunction "1_1") (pintype "bidirectional"))
      (node (ref "R65") (pin "1") (pinfunction "1_1") (pintype "bidirectional"))
      (node (ref "R66") (pin "1") (pinfunction "1_1") (pintype "bidirectional"))
      (node (ref "R67") (pin "1") (pinfunction "1_1") (pintype "bidirectional"))
      (node (ref "R68") (pin "1") (pinfunction "1_1") (pintype "bidirectional"))
      (node (ref "R69") (pin "1") (pinfunction "1_1") (pintype "bidirectional"))
      (node (ref "R70") (pin "1") (pinfunction "1_1") (pintype "bidirectional"))
      (node (ref "U2") (pin "43") (pinfunction "39_43") (pintype "bidirectional"))
      (node (ref "U3") (pin "5") (pinfunction "4_5") (pintype "bidirectional"))
      (node (ref "U5") (pin "E10") (pinfunction "111_E10") (pintype "bidirectional"))
      (node (ref "U5") (pin "E11") (pinfunction "112_E11") (pintype "bidirectional"))
      (node (ref "U5") (pin "E12") (pinfunction "113_E12") (pintype "bidirectional"))
      (node (ref "U5") (pin "E13") (pinfunction "114_E13") (pintype "bidirectional"))
      (node (ref "U5") (pin "F14") (pinfunction "115_F14") (pintype "bidirectional"))
      (node (ref "U5") (pin "G14") (pinfunction "116_G14") (pintype "bidirectional"))
      (node (ref "U5") (pin "H14") (pinfunction "59_H14") (pintype "bidirectional"))
      (node (ref "U5") (pin "J14") (pinfunction "58_J14") (pintype "bidirectional"))
      (node (ref "U5") (pin "K14") (pinfunction "60_K14") (pintype "bidirectional"))
      (node (ref "U5") (pin "L14") (pinfunction "61_L14") (pintype "bidirectional"))
      (node (ref "U5") (pin "N15") (pinfunction "83_N15") (pintype "bidirectional"))
      (node (ref "U5") (pin "N5") (pinfunction "117_N5") (pintype "bidirectional"))
      (node (ref "U5") (pin "P10") (pinfunction "55_P10") (pintype "bidirectional"))
      (node (ref "U5") (pin "P11") (pinfunction "96_P11") (pintype "bidirectional"))
      (node (ref "U5") (pin "P12") (pinfunction "56_P12") (pintype "bidirectional"))
      (node (ref "U5") (pin "P13") (pinfunction "57_P13") (pintype "bidirectional"))
      (node (ref "U5") (pin "P5") (pinfunction "118_P5") (pintype "bidirectional"))
      (node (ref "U5") (pin "P6") (pinfunction "119_P6") (pintype "bidirectional"))
      (node (ref "U5") (pin "P7") (pinfunction "53_P7") (pintype "bidirectional"))
      (node (ref "U5") (pin "P8") (pinfunction "54_P8") (pintype "bidirectional"))
      (node (ref "U5") (pin "R15") (pinfunction "80_R15") (pintype "bidirectional"))
      (node (ref "U6") (pin "6") (pinfunction "6_6") (pintype "bidirectional"))
      (node (ref "U6") (pin "7") (pinfunction "7_7") (pintype "bidirectional"))
      (node (ref "U6") (pin "8") (pinfunction "8_8") (pintype "bidirectional"))
      (node (ref "U7") (pin "4") (pinfunction "3_4") (pintype "bidirectional"))
      (node (ref "Y4") (pin "4") (pinfunction "3_4") (pintype "bidirectional"))
    )
    (net (code "299") (name "VDD_3V3AUX") (class "Default")
      (node (ref "C18") (pin "1") (pinfunction "1_1") (pintype "bidirectional"))
      (node (ref "D1") (pin "2") (pinfunction "2_2") (pintype "bidirectional"))
      (node (ref "U2") (pin "1") (pinfunction "44_1") (pintype "bidirectional"))
      (node (ref "U4") (pin "1") (pinfunction "4_1") (pintype "bidirectional"))
    )
    (net (code "300") (name "VDD_3V3B") (class "Default")
      (node (ref "C126") (pin "2") (pinfunction "2_2") (pintype "bidirectional"))
      (node (ref "C127") (pin "1") (pinfunction "1_1") (pintype "bidirectional"))
      (node (ref "C128") (pin "1") (pinfunction "1_1") (pintype "bidirectional"))
      (node (ref "C129") (pin "1") (pinfunction "1_1") (pintype "bidirectional"))
      (node (ref "C130") (pin "1") (pinfunction "1_1") (pintype "bidirectional"))
      (node (ref "C135") (pin "1") (pinfunction "1_1") (pintype "bidirectional"))
      (node (ref "C153") (pin "1") (pinfunction "1_1") (pintype "bidirectional"))
      (node (ref "C154") (pin "1") (pinfunction "1_1") (pintype "bidirectional"))
      (node (ref "C155") (pin "2") (pinfunction "2_2") (pintype "bidirectional"))
      (node (ref "C20") (pin "1") (pinfunction "1_1") (pintype "bidirectional"))
      (node (ref "C29") (pin "1") (pinfunction "1_1") (pintype "bidirectional"))
      (node (ref "FB4") (pin "1") (pinfunction "1_1") (pintype "bidirectional"))
      (node (ref "P10") (pin "4") (pinfunction "4_4") (pintype "bidirectional"))
      (node (ref "P2") (pin "5") (pinfunction "3_5") (pintype "bidirectional"))
      (node (ref "P9") (pin "3") (pinfunction "25_3") (pintype "bidirectional"))
      (node (ref "P9") (pin "4") (pinfunction "2_4") (pintype "bidirectional"))
      (node (ref "R101") (pin "1") (pinfunction "1_1") (pintype "bidirectional"))
      (node (ref "R102") (pin "1") (pinfunction "1_1") (pintype "bidirectional"))
      (node (ref "R103") (pin "1") (pinfunction "1_1") (pintype "bidirectional"))
      (node (ref "R104") (pin "1") (pinfunction "1_1") (pintype "bidirectional"))
      (node (ref "R105") (pin "1") (pinfunction "1_1") (pintype "bidirectional"))
      (node (ref "R106") (pin "1") (pinfunction "1_1") (pintype "bidirectional"))
      (node (ref "R107") (pin "1") (pinfunction "1_1") (pintype "bidirectional"))
      (node (ref "R108") (pin "1") (pinfunction "1_1") (pintype "bidirectional"))
      (node (ref "R109") (pin "1") (pinfunction "1_1") (pintype "bidirectional"))
      (node (ref "R11") (pin "1") (pinfunction "1_1") (pintype "bidirectional"))
      (node (ref "R110") (pin "1") (pinfunction "1_1") (pintype "bidirectional"))
      (node (ref "R111") (pin "1") (pinfunction "1_1") (pintype "bidirectional"))
      (node (ref "R112") (pin "2") (pinfunction "2_2") (pintype "bidirectional"))
      (node (ref "R113") (pin "2") (pinfunction "2_2") (pintype "bidirectional"))
      (node (ref "R114") (pin "2") (pinfunction "2_2") (pintype "bidirectional"))
      (node (ref "R119") (pin "1") (pinfunction "1_1") (pintype "bidirectional"))
      (node (ref "R150") (pin "1") (pinfunction "1_1") (pintype "bidirectional"))
      (node (ref "R151") (pin "1") (pinfunction "1_1") (pintype "bidirectional"))
      (node (ref "R152") (pin "1") (pinfunction "1_1") (pintype "bidirectional"))
      (node (ref "R153") (pin "1") (pinfunction "1_1") (pintype "bidirectional"))
      (node (ref "R154") (pin "1") (pinfunction "1_1") (pintype "bidirectional"))
      (node (ref "R155") (pin "1") (pinfunction "1_1") (pintype "bidirectional"))
      (node (ref "R157") (pin "2") (pinfunction "2_2") (pintype "bidirectional"))
      (node (ref "R158") (pin "1") (pinfunction "1_1") (pintype "bidirectional"))
      (node (ref "R163") (pin "1") (pinfunction "1_1") (pintype "bidirectional"))
      (node (ref "R166") (pin "2") (pinfunction "2_2") (pintype "bidirectional"))
      (node (ref "R23") (pin "1") (pinfunction "1_1") (pintype "bidirectional"))
      (node (ref "R24") (pin "1") (pinfunction "1_1") (pintype "bidirectional"))
      (node (ref "U13") (pin "C6") (pinfunction "34_C6") (pintype "bidirectional"))
      (node (ref "U13") (pin "E6") (pinfunction "53_E6") (pintype "bidirectional"))
      (node (ref "U13") (pin "F5") (pinfunction "65_F5") (pintype "bidirectional"))
      (node (ref "U13") (pin "J10") (pinfunction "150_J10") (pintype "bidirectional"))
      (node (ref "U13") (pin "K9") (pinfunction "97_K9") (pintype "bidirectional"))
      (node (ref "U13") (pin "M4") (pinfunction "111_M4") (pintype "bidirectional"))
      (node (ref "U13") (pin "N4") (pinfunction "125_N4") (pintype "bidirectional"))
      (node (ref "U13") (pin "P3") (pinfunction "137_P3") (pintype "bidirectional"))
      (node (ref "U13") (pin "P5") (pinfunction "139_P5") (pintype "bidirectional"))
      (node (ref "U14") (pin "12") (pinfunction "23_12") (pintype "bidirectional"))
      (node (ref "U15") (pin "7") (pinfunction "2_7") (pintype "bidirectional"))
      (node (ref "U15") (pin "8") (pinfunction "4_8") (pintype "bidirectional"))
      (node (ref "U4") (pin "3") (pinfunction "2_3") (pintype "bidirectional"))
    )
    (net (code "301") (name "VDD_5V") (class "Default")
      (node (ref "C2") (pin "2") (pinfunction "2_2") (pintype "bidirectional"))
      (node (ref "P1") (pin "1") (pinfunction "1_1") (pintype "bidirectional"))
      (node (ref "P9") (pin "5") (pinfunction "26_5") (pintype "bidirectional"))
      (node (ref "P9") (pin "6") (pinfunction "3_6") (pintype "bidirectional"))
      (node (ref "U2") (pin "10") (pinfunction "1_10") (pintype "bidirectional"))
    )
    (net (code "302") (name "VDD_ADC") (class "Default")
      (node (ref "C93") (pin "1") (pinfunction "1_1") (pintype "bidirectional"))
      (node (ref "FB2") (pin "1") (pinfunction "1_1") (pintype "bidirectional"))
      (node (ref "P9") (pin "32") (pinfunction "16_32") (pintype "bidirectional"))
      (node (ref "R27") (pin "1") (pinfunction "1_1") (pintype "bidirectional"))
      (node (ref "U5") (pin "D8") (pinfunction "72_D8") (pintype "bidirectional"))
    )
    (net (code "303") (name "VDD_CORE") (class "Default")
      (node (ref "C11") (pin "2") (pinfunction "2_2") (pintype "bidirectional"))
      (node (ref "C39") (pin "2") (pinfunction "2_2") (pintype "bidirectional"))
      (node (ref "C40") (pin "2") (pinfunction "2_2") (pintype "bidirectional"))
      (node (ref "C41") (pin "1") (pinfunction "1_1") (pintype "bidirectional"))
      (node (ref "C42") (pin "1") (pinfunction "1_1") (pintype "bidirectional"))
      (node (ref "C43") (pin "1") (pinfunction "1_1") (pintype "bidirectional"))
      (node (ref "C44") (pin "1") (pinfunction "1_1") (pintype "bidirectional"))
      (node (ref "C45") (pin "1") (pinfunction "1_1") (pintype "bidirectional"))
      (node (ref "C46") (pin "1") (pinfunction "1_1") (pintype "bidirectional"))
      (node (ref "C47") (pin "1") (pinfunction "1_1") (pintype "bidirectional"))
      (node (ref "C48") (pin "1") (pinfunction "1_1") (pintype "bidirectional"))
      (node (ref "C49") (pin "1") (pinfunction "1_1") (pintype "bidirectional"))
      (node (ref "C50") (pin "1") (pinfunction "1_1") (pintype "bidirectional"))
      (node (ref "C51") (pin "1") (pinfunction "1_1") (pintype "bidirectional"))
      (node (ref "C52") (pin "1") (pinfunction "1_1") (pintype "bidirectional"))
      (node (ref "C53") (pin "1") (pinfunction "1_1") (pintype "bidirectional"))
      (node (ref "C54") (pin "1") (pinfunction "1_1") (pintype "bidirectional"))
      (node (ref "C55") (pin "2") (pinfunction "2_2") (pintype "bidirectional"))
      (node (ref "L3") (pin "2") (pinfunction "2_2") (pintype "bidirectional"))
      (node (ref "U2") (pin "29") (pinfunction "37_29") (pintype "bidirectional"))
      (node (ref "U5") (pin "F6") (pinfunction "38_F6") (pintype "bidirectional"))
      (node (ref "U5") (pin "F7") (pinfunction "39_F7") (pintype "bidirectional"))
      (node (ref "U5") (pin "G10") (pinfunction "43_G10") (pintype "bidirectional"))
      (node (ref "U5") (pin "G6") (pinfunction "40_G6") (pintype "bidirectional"))
      (node (ref "U5") (pin "G7") (pinfunction "42_G7") (pintype "bidirectional"))
      (node (ref "U5") (pin "H11") (pinfunction "45_H11") (pintype "bidirectional"))
      (node (ref "U5") (pin "J12") (pinfunction "46_J12") (pintype "bidirectional"))
      (node (ref "U5") (pin "K12") (pinfunction "49_K12") (pintype "bidirectional"))
      (node (ref "U5") (pin "K6") (pinfunction "47_K6") (pintype "bidirectional"))
      (node (ref "U5") (pin "K8") (pinfunction "97_K8") (pintype "bidirectional"))
      (node (ref "U5") (pin "L6") (pinfunction "50_L6") (pintype "bidirectional"))
      (node (ref "U5") (pin "L7") (pinfunction "51_L7") (pintype "bidirectional"))
      (node (ref "U5") (pin "L8") (pinfunction "52_L8") (pintype "bidirectional"))
      (node (ref "U5") (pin "L9") (pinfunction "98_L9") (pintype "bidirectional"))
      (node (ref "U5") (pin "M11") (pinfunction "102_M11") (pintype "bidirectional"))
      (node (ref "U5") (pin "M13") (pinfunction "103_M13") (pintype "bidirectional"))
      (node (ref "U5") (pin "N12") (pinfunction "106_N12") (pintype "bidirectional"))
      (node (ref "U5") (pin "N13") (pinfunction "107_N13") (pintype "bidirectional"))
      (node (ref "U5") (pin "N8") (pinfunction "104_N8") (pintype "bidirectional"))
      (node (ref "U5") (pin "N9") (pinfunction "105_N9") (pintype "bidirectional"))
    )
    (net (code "304") (name "VDD_MPU") (class "Default")
      (node (ref "C12") (pin "2") (pinfunction "2_2") (pintype "bidirectional"))
      (node (ref "C62") (pin "2") (pinfunction "2_2") (pintype "bidirectional"))
      (node (ref "C63") (pin "1") (pinfunction "1_1") (pintype "bidirectional"))
      (node (ref "C64") (pin "1") (pinfunction "1_1") (pintype "bidirectional"))
      (node (ref "C65") (pin "1") (pinfunction "1_1") (pintype "bidirectional"))
      (node (ref "L2") (pin "2") (pinfunction "2_2") (pintype "bidirectional"))
      (node (ref "U2") (pin "24") (pinfunction "34_24") (pintype "bidirectional"))
      (node (ref "U5") (pin "F10") (pinfunction "41_F10") (pintype "bidirectional"))
      (node (ref "U5") (pin "F11") (pinfunction "44_F11") (pintype "bidirectional"))
      (node (ref "U5") (pin "F12") (pinfunction "48_F12") (pintype "bidirectional"))
      (node (ref "U5") (pin "F13") (pinfunction "88_F13") (pintype "bidirectional"))
      (node (ref "U5") (pin "G13") (pinfunction "108_G13") (pintype "bidirectional"))
      (node (ref "U5") (pin "H13") (pinfunction "109_H13") (pintype "bidirectional"))
      (node (ref "U5") (pin "J13") (pinfunction "110_J13") (pintype "bidirectional"))
    )
    (net (code "305") (name "VDD_PHYA") (class "Default")
      (node (ref "C131") (pin "1") (pinfunction "1_1") (pintype "bidirectional"))
      (node (ref "C132") (pin "1") (pinfunction "1_1") (pintype "bidirectional"))
      (node (ref "C133") (pin "2") (pinfunction "2_2") (pintype "bidirectional"))
      (node (ref "FB4") (pin "2") (pinfunction "2_2") (pintype "bidirectional"))
      (node (ref "R120") (pin "2") (pinfunction "2_2") (pintype "bidirectional"))
      (node (ref "R121") (pin "2") (pinfunction "2_2") (pintype "bidirectional"))
      (node (ref "R122") (pin "2") (pinfunction "2_2") (pintype "bidirectional"))
      (node (ref "R123") (pin "2") (pinfunction "2_2") (pintype "bidirectional"))
      (node (ref "R137") (pin "2") (pinfunction "2_2") (pintype "bidirectional"))
      (node (ref "U14") (pin "1") (pinfunction "25_1") (pintype "bidirectional"))
      (node (ref "U14") (pin "27") (pinfunction "24_27") (pintype "bidirectional"))
    )
    (net (code "306") (name "VDD_PLL") (class "Default")
      (node (ref "C106") (pin "1") (pinfunction "1_1") (pintype "bidirectional"))
      (node (ref "C79") (pin "1") (pinfunction "1_1") (pintype "bidirectional"))
      (node (ref "C92") (pin "1") (pinfunction "1_1") (pintype "bidirectional"))
      (node (ref "C94") (pin "1") (pinfunction "1_1") (pintype "bidirectional"))
      (node (ref "FB1") (pin "2") (pinfunction "2_2") (pintype "bidirectional"))
      (node (ref "U5") (pin "E7") (pinfunction "86_E7") (pintype "bidirectional"))
      (node (ref "U5") (pin "H15") (pinfunction "79_H15") (pintype "bidirectional"))
      (node (ref "U5") (pin "R10") (pinfunction "71_R10") (pintype "bidirectional"))
      (node (ref "U5") (pin "R11") (pinfunction "70_R11") (pintype "bidirectional"))
    )
    (net (code "307") (name "VIO") (class "Default")
      (node (ref "R7") (pin "2") (pinfunction "2_2") (pintype "bidirectional"))
      (node (ref "U2") (pin "18") (pinfunction "24_18") (pintype "bidirectional"))
    )
    (net (code "308") (name "VRTC") (class "Default")
      (node (ref "C105") (pin "1") (pinfunction "1_1") (pintype "bidirectional"))
      (node (ref "C16") (pin "1") (pinfunction "1_1") (pintype "bidirectional"))
      (node (ref "R26") (pin "1") (pinfunction "1_1") (pintype "bidirectional"))
      (node (ref "R5") (pin "2") (pinfunction "2_2") (pintype "bidirectional"))
      (node (ref "U5") (pin "D7") (pinfunction "74_D7") (pintype "bidirectional"))
    )
    (net (code "309") (name "WAKEUP") (class "Default")
      (node (ref "R26") (pin "2") (pinfunction "2_2") (pintype "bidirectional"))
      (node (ref "U2") (pin "13") (pinfunction "27_13") (pintype "bidirectional"))
      (node (ref "U5") (pin "C5") (pinfunction "77_C5") (pintype "bidirectional"))
    )
    (net (code "310") (name "XDMA_EVENT_INTR0") (class "Default")
      (node (ref "P2") (pin "17") (pinfunction "9_17") (pintype "bidirectional"))
      (node (ref "R18") (pin "2") (pinfunction "2_2") (pintype "bidirectional"))
      (node (ref "U6") (pin "1") (pinfunction "1_1") (pintype "bidirectional"))
    )
    (net (code "311") (name "unconnected-(D6-7-Pad10)") (class "Default")
      (node (ref "D6") (pin "10") (pinfunction "7_10") (pintype "bidirectional"))
    )
    (net (code "312") (name "unconnected-(D6-8-Pad7)") (class "Default")
      (node (ref "D6") (pin "7") (pinfunction "8_7") (pintype "bidirectional"))
    )
    (net (code "313") (name "unconnected-(D6-9-Pad6)") (class "Default")
      (node (ref "D6") (pin "6") (pinfunction "9_6") (pintype "bidirectional"))
    )
    (net (code "314") (name "unconnected-(D6-10-Pad9)") (class "Default")
      (node (ref "D6") (pin "9") (pinfunction "10_9") (pintype "bidirectional"))
    )
    (net (code "315") (name "unconnected-(D7-7-Pad10)") (class "Default")
      (node (ref "D7") (pin "10") (pinfunction "7_10") (pintype "bidirectional"))
    )
    (net (code "316") (name "unconnected-(D7-8-Pad7)") (class "Default")
      (node (ref "D7") (pin "7") (pinfunction "8_7") (pintype "bidirectional"))
    )
    (net (code "317") (name "unconnected-(D7-9-Pad6)") (class "Default")
      (node (ref "D7") (pin "6") (pinfunction "9_6") (pintype "bidirectional"))
    )
    (net (code "318") (name "unconnected-(D7-10-Pad9)") (class "Default")
      (node (ref "D7") (pin "9") (pinfunction "10_9") (pintype "bidirectional"))
    )
    (net (code "319") (name "unconnected-(J1-Pad2)") (class "Default")
      (node (ref "J1") (pin "2") (pinfunction "2_2") (pintype "bidirectional"))
    )
    (net (code "320") (name "unconnected-(J1-Pad3)") (class "Default")
      (node (ref "J1") (pin "3") (pinfunction "3_3") (pintype "bidirectional"))
    )
    (net (code "321") (name "unconnected-(J1-Pad6)") (class "Default")
      (node (ref "J1") (pin "6") (pinfunction "6_6") (pintype "bidirectional"))
    )
    (net (code "322") (name "unconnected-(P1-2-Pad3)") (class "Default")
      (node (ref "P1") (pin "3") (pinfunction "2_3") (pintype "bidirectional"))
    )
    (net (code "323") (name "unconnected-(P2-13-Pad6)") (class "Default")
      (node (ref "P2") (pin "6") (pinfunction "13_6") (pintype "bidirectional"))
    )
    (net (code "324") (name "unconnected-(P5-14-Pad7)") (class "Default")
      (node (ref "P5") (pin "7") (pinfunction "14_7") (pintype "bidirectional"))
    )
    (net (code "325") (name "unconnected-(P6-14-Pad2)") (class "Default")
      (node (ref "P6") (pin "2") (pinfunction "14_2") (pintype "bidirectional"))
    )
    (net (code "326") (name "unconnected-(U2-9-Pad16)") (class "Default")
      (node (ref "U2") (pin "16") (pinfunction "9_16") (pintype "bidirectional"))
    )
    (net (code "327") (name "unconnected-(U2-10-Pad14)") (class "Default")
      (node (ref "U2") (pin "14") (pinfunction "10_14") (pintype "bidirectional"))
    )
    (net (code "328") (name "unconnected-(U2-14-Pad44)") (class "Default")
      (node (ref "U2") (pin "44") (pinfunction "14_44") (pintype "bidirectional"))
    )
    (net (code "329") (name "unconnected-(U2-18-Pad37)") (class "Default")
      (node (ref "U2") (pin "37") (pinfunction "18_37") (pintype "bidirectional"))
    )
    (net (code "330") (name "unconnected-(U2-19-Pad38)") (class "Default")
      (node (ref "U2") (pin "38") (pinfunction "19_38") (pintype "bidirectional"))
    )
    (net (code "331") (name "unconnected-(U2-20-Pad34)") (class "Default")
      (node (ref "U2") (pin "34") (pinfunction "20_34") (pintype "bidirectional"))
    )
    (net (code "332") (name "unconnected-(U2-21-Pad33)") (class "Default")
      (node (ref "U2") (pin "33") (pinfunction "21_33") (pintype "bidirectional"))
    )
    (net (code "333") (name "unconnected-(U2-22-Pad35)") (class "Default")
      (node (ref "U2") (pin "35") (pinfunction "22_35") (pintype "bidirectional"))
    )
    (net (code "334") (name "unconnected-(U2-23-Pad36)") (class "Default")
      (node (ref "U2") (pin "36") (pinfunction "23_36") (pintype "bidirectional"))
    )
    (net (code "335") (name "unconnected-(U2-47-Pad15)") (class "Default")
      (node (ref "U2") (pin "15") (pinfunction "47_15") (pintype "bidirectional"))
    )
    (net (code "336") (name "unconnected-(U2-48-Pad17)") (class "Default")
      (node (ref "U2") (pin "17") (pinfunction "48_17") (pintype "bidirectional"))
    )
    (net (code "337") (name "unconnected-(U3-5-Pad1)") (class "Default")
      (node (ref "U3") (pin "1") (pinfunction "5_1") (pintype "bidirectional"))
    )
    (net (code "338") (name "unconnected-(U5B-13-PadE18)") (class "Default")
      (node (ref "U5") (pin "E18") (pinfunction "13_E18") (pintype "bidirectional"))
    )
    (net (code "339") (name "unconnected-(U5B-14-PadE17)") (class "Default")
      (node (ref "U5") (pin "E17") (pinfunction "14_E17") (pintype "bidirectional"))
    )
    (net (code "340") (name "unconnected-(U5B-17-PadM15)") (class "Default")
      (node (ref "U5") (pin "M15") (pinfunction "17_M15") (pintype "bidirectional"))
    )
    (net (code "341") (name "unconnected-(U5B-19-PadF16)") (class "Default")
      (node (ref "U5") (pin "F16") (pinfunction "19_F16") (pintype "bidirectional"))
    )
    (net (code "342") (name "unconnected-(U5B-24-PadP18)") (class "Default")
      (node (ref "U5") (pin "P18") (pinfunction "24_P18") (pintype "bidirectional"))
    )
    (net (code "343") (name "unconnected-(U5C-78-PadM5)") (class "Default")
      (node (ref "U5") (pin "M5") (pinfunction "78_M5") (pintype "bidirectional"))
    )
    (net (code "344") (name "unconnected-(U9-6-Pad3)") (class "Default")
      (node (ref "U9") (pin "3") (pinfunction "6_3") (pintype "bidirectional"))
    )
    (net (code "345") (name "unconnected-(U9-Pad5)") (class "Default")
      (node (ref "U9") (pin "5") (pinfunction "5_5") (pintype "bidirectional"))
    )
    (net (code "346") (name "unconnected-(U10-Pad5)") (class "Default")
      (node (ref "U10") (pin "5") (pinfunction "5_5") (pintype "bidirectional"))
    )
    (net (code "347") (name "unconnected-(U11-48-Pad26)") (class "Default")
      (node (ref "U11") (pin "26") (pinfunction "48_26") (pintype "bidirectional"))
    )
    (net (code "348") (name "unconnected-(U11-60-Pad28)") (class "Default")
      (node (ref "U11") (pin "28") (pinfunction "60_28") (pintype "bidirectional"))
    )
    (net (code "349") (name "unconnected-(U12-74-PadJ1)") (class "Default")
      (node (ref "U12") (pin "J1") (pinfunction "74_J1") (pintype "bidirectional"))
    )
    (net (code "350") (name "unconnected-(U12-75-PadJ9)") (class "Default")
      (node (ref "U12") (pin "J9") (pinfunction "75_J9") (pintype "bidirectional"))
    )
    (net (code "351") (name "unconnected-(U12-80-PadL1)") (class "Default")
      (node (ref "U12") (pin "L1") (pinfunction "80_L1") (pintype "bidirectional"))
    )
    (net (code "352") (name "unconnected-(U12-82-PadL9)") (class "Default")
      (node (ref "U12") (pin "L9") (pinfunction "82_L9") (pintype "bidirectional"))
    )
    (net (code "353") (name "unconnected-(U13-1-PadA1)") (class "Default")
      (node (ref "U13") (pin "A1") (pinfunction "1_A1") (pintype "bidirectional"))
    )
    (net (code "354") (name "unconnected-(U13-2-PadA2)") (class "Default")
      (node (ref "U13") (pin "A2") (pinfunction "2_A2") (pintype "bidirectional"))
    )
    (net (code "355") (name "unconnected-(U13-6-PadA6)") (class "Default")
      (node (ref "U13") (pin "A6") (pinfunction "6_A6") (pintype "bidirectional"))
    )
    (net (code "356") (name "unconnected-(U13-7-PadA7)") (class "Default")
      (node (ref "U13") (pin "A7") (pinfunction "7_A7") (pintype "bidirectional"))
    )
    (net (code "357") (name "unconnected-(U13-8-PadA8)") (class "Default")
      (node (ref "U13") (pin "A8") (pinfunction "8_A8") (pintype "bidirectional"))
    )
    (net (code "358") (name "unconnected-(U13-9-PadA9)") (class "Default")
      (node (ref "U13") (pin "A9") (pinfunction "9_A9") (pintype "bidirectional"))
    )
    (net (code "359") (name "unconnected-(U13-10-PadA10)") (class "Default")
      (node (ref "U13") (pin "A10") (pinfunction "10_A10") (pintype "bidirectional"))
    )
    (net (code "360") (name "unconnected-(U13-11-PadA11)") (class "Default")
      (node (ref "U13") (pin "A11") (pinfunction "11_A11") (pintype "bidirectional"))
    )
    (net (code "361") (name "unconnected-(U13-12-PadA12)") (class "Default")
      (node (ref "U13") (pin "A12") (pinfunction "12_A12") (pintype "bidirectional"))
    )
    (net (code "362") (name "unconnected-(U13-13-PadA13)") (class "Default")
      (node (ref "U13") (pin "A13") (pinfunction "13_A13") (pintype "bidirectional"))
    )
    (net (code "363") (name "unconnected-(U13-14-PadA14)") (class "Default")
      (node (ref "U13") (pin "A14") (pinfunction "14_A14") (pintype "bidirectional"))
    )
    (net (code "364") (name "unconnected-(U13-15-PadB1)") (class "Default")
      (node (ref "U13") (pin "B1") (pinfunction "15_B1") (pintype "bidirectional"))
    )
    (net (code "365") (name "unconnected-(U13-21-PadB7)") (class "Default")
      (node (ref "U13") (pin "B7") (pinfunction "21_B7") (pintype "bidirectional"))
    )
    (net (code "366") (name "unconnected-(U13-22-PadB8)") (class "Default")
      (node (ref "U13") (pin "B8") (pinfunction "22_B8") (pintype "bidirectional"))
    )
    (net (code "367") (name "unconnected-(U13-23-PadB9)") (class "Default")
      (node (ref "U13") (pin "B9") (pinfunction "23_B9") (pintype "bidirectional"))
    )
    (net (code "368") (name "unconnected-(U13-24-PadB10)") (class "Default")
      (node (ref "U13") (pin "B10") (pinfunction "24_B10") (pintype "bidirectional"))
    )
    (net (code "369") (name "unconnected-(U13-25-PadB11)") (class "Default")
      (node (ref "U13") (pin "B11") (pinfunction "25_B11") (pintype "bidirectional"))
    )
    (net (code "370") (name "unconnected-(U13-26-PadB12)") (class "Default")
      (node (ref "U13") (pin "B12") (pinfunction "26_B12") (pintype "bidirectional"))
    )
    (net (code "371") (name "unconnected-(U13-27-PadB13)") (class "Default")
      (node (ref "U13") (pin "B13") (pinfunction "27_B13") (pintype "bidirectional"))
    )
    (net (code "372") (name "unconnected-(U13-28-PadB14)") (class "Default")
      (node (ref "U13") (pin "B14") (pinfunction "28_B14") (pintype "bidirectional"))
    )
    (net (code "373") (name "unconnected-(U13-29-PadC1)") (class "Default")
      (node (ref "U13") (pin "C1") (pinfunction "29_C1") (pintype "bidirectional"))
    )
    (net (code "374") (name "unconnected-(U13-31-PadC3)") (class "Default")
      (node (ref "U13") (pin "C3") (pinfunction "31_C3") (pintype "bidirectional"))
    )
    (net (code "375") (name "unconnected-(U13-33-PadC5)") (class "Default")
      (node (ref "U13") (pin "C5") (pinfunction "33_C5") (pintype "bidirectional"))
    )
    (net (code "376") (name "unconnected-(U13-35-PadC7)") (class "Default")
      (node (ref "U13") (pin "C7") (pinfunction "35_C7") (pintype "bidirectional"))
    )
    (net (code "377") (name "unconnected-(U13-36-PadC8)") (class "Default")
      (node (ref "U13") (pin "C8") (pinfunction "36_C8") (pintype "bidirectional"))
    )
    (net (code "378") (name "unconnected-(U13-37-PadC9)") (class "Default")
      (node (ref "U13") (pin "C9") (pinfunction "37_C9") (pintype "bidirectional"))
    )
    (net (code "379") (name "unconnected-(U13-38-PadC10)") (class "Default")
      (node (ref "U13") (pin "C10") (pinfunction "38_C10") (pintype "bidirectional"))
    )
    (net (code "380") (name "unconnected-(U13-39-PadC11)") (class "Default")
      (node (ref "U13") (pin "C11") (pinfunction "39_C11") (pintype "bidirectional"))
    )
    (net (code "381") (name "unconnected-(U13-40-PadC12)") (class "Default")
      (node (ref "U13") (pin "C12") (pinfunction "40_C12") (pintype "bidirectional"))
    )
    (net (code "382") (name "unconnected-(U13-41-PadC13)") (class "Default")
      (node (ref "U13") (pin "C13") (pinfunction "41_C13") (pintype "bidirectional"))
    )
    (net (code "383") (name "unconnected-(U13-42-PadC14)") (class "Default")
      (node (ref "U13") (pin "C14") (pinfunction "42_C14") (pintype "bidirectional"))
    )
    (net (code "384") (name "unconnected-(U13-43-PadD1)") (class "Default")
      (node (ref "U13") (pin "D1") (pinfunction "43_D1") (pintype "bidirectional"))
    )
    (net (code "385") (name "unconnected-(U13-44-PadD2)") (class "Default")
      (node (ref "U13") (pin "D2") (pinfunction "44_D2") (pintype "bidirectional"))
    )
    (net (code "386") (name "unconnected-(U13-45-PadD3)") (class "Default")
      (node (ref "U13") (pin "D3") (pinfunction "45_D3") (pintype "bidirectional"))
    )
    (net (code "387") (name "unconnected-(U13-46-PadD4)") (class "Default")
      (node (ref "U13") (pin "D4") (pinfunction "46_D4") (pintype "bidirectional"))
    )
    (net (code "388") (name "unconnected-(U13-47-PadD12)") (class "Default")
      (node (ref "U13") (pin "D12") (pinfunction "47_D12") (pintype "bidirectional"))
    )
    (net (code "389") (name "unconnected-(U13-48-PadD13)") (class "Default")
      (node (ref "U13") (pin "D13") (pinfunction "48_D13") (pintype "bidirectional"))
    )
    (net (code "390") (name "unconnected-(U13-49-PadD14)") (class "Default")
      (node (ref "U13") (pin "D14") (pinfunction "49_D14") (pintype "bidirectional"))
    )
    (net (code "391") (name "unconnected-(U13-50-PadE1)") (class "Default")
      (node (ref "U13") (pin "E1") (pinfunction "50_E1") (pintype "bidirectional"))
    )
    (net (code "392") (name "unconnected-(U13-51-PadE2)") (class "Default")
      (node (ref "U13") (pin "E2") (pinfunction "51_E2") (pintype "bidirectional"))
    )
    (net (code "393") (name "unconnected-(U13-52-PadE3)") (class "Default")
      (node (ref "U13") (pin "E3") (pinfunction "52_E3") (pintype "bidirectional"))
    )
    (net (code "394") (name "unconnected-(U13-56-PadE8)") (class "Default")
      (node (ref "U13") (pin "E8") (pinfunction "56_E8") (pintype "bidirectional"))
    )
    (net (code "395") (name "unconnected-(U13-57-PadE9)") (class "Default")
      (node (ref "U13") (pin "E9") (pinfunction "57_E9") (pintype "bidirectional"))
    )
    (net (code "396") (name "unconnected-(U13-58-PadE10)") (class "Default")
      (node (ref "U13") (pin "E10") (pinfunction "58_E10") (pintype "bidirectional"))
    )
    (net (code "397") (name "unconnected-(U13-59-PadE12)") (class "Default")
      (node (ref "U13") (pin "E12") (pinfunction "59_E12") (pintype "bidirectional"))
    )
    (net (code "398") (name "unconnected-(U13-60-PadE13)") (class "Default")
      (node (ref "U13") (pin "E13") (pinfunction "60_E13") (pintype "bidirectional"))
    )
    (net (code "399") (name "unconnected-(U13-61-PadE14)") (class "Default")
      (node (ref "U13") (pin "E14") (pinfunction "61_E14") (pintype "bidirectional"))
    )
    (net (code "400") (name "unconnected-(U13-62-PadF1)") (class "Default")
      (node (ref "U13") (pin "F1") (pinfunction "62_F1") (pintype "bidirectional"))
    )
    (net (code "401") (name "unconnected-(U13-63-PadF2)") (class "Default")
      (node (ref "U13") (pin "F2") (pinfunction "63_F2") (pintype "bidirectional"))
    )
    (net (code "402") (name "unconnected-(U13-64-PadF3)") (class "Default")
      (node (ref "U13") (pin "F3") (pinfunction "64_F3") (pintype "bidirectional"))
    )
    (net (code "403") (name "unconnected-(U13-66-PadF10)") (class "Default")
      (node (ref "U13") (pin "F10") (pinfunction "66_F10") (pintype "bidirectional"))
    )
    (net (code "404") (name "unconnected-(U13-67-PadF12)") (class "Default")
      (node (ref "U13") (pin "F12") (pinfunction "67_F12") (pintype "bidirectional"))
    )
    (net (code "405") (name "unconnected-(U13-68-PadF13)") (class "Default")
      (node (ref "U13") (pin "F13") (pinfunction "68_F13") (pintype "bidirectional"))
    )
    (net (code "406") (name "unconnected-(U13-69-PadF14)") (class "Default")
      (node (ref "U13") (pin "F14") (pinfunction "69_F14") (pintype "bidirectional"))
    )
    (net (code "407") (name "unconnected-(U13-70-PadG1)") (class "Default")
      (node (ref "U13") (pin "G1") (pinfunction "70_G1") (pintype "bidirectional"))
    )
    (net (code "408") (name "unconnected-(U13-71-PadG2)") (class "Default")
      (node (ref "U13") (pin "G2") (pinfunction "71_G2") (pintype "bidirectional"))
    )
    (net (code "409") (name "unconnected-(U13-73-PadG10)") (class "Default")
      (node (ref "U13") (pin "G10") (pinfunction "73_G10") (pintype "bidirectional"))
    )
    (net (code "410") (name "unconnected-(U13-74-PadG12)") (class "Default")
      (node (ref "U13") (pin "G12") (pinfunction "74_G12") (pintype "bidirectional"))
    )
    (net (code "411") (name "unconnected-(U13-75-PadG13)") (class "Default")
      (node (ref "U13") (pin "G13") (pinfunction "75_G13") (pintype "bidirectional"))
    )
    (net (code "412") (name "unconnected-(U13-76-PadG14)") (class "Default")
      (node (ref "U13") (pin "G14") (pinfunction "76_G14") (pintype "bidirectional"))
    )
    (net (code "413") (name "unconnected-(U13-77-PadG3)") (class "Default")
      (node (ref "U13") (pin "G3") (pinfunction "77_G3") (pintype "bidirectional"))
    )
    (net (code "414") (name "unconnected-(U13-78-PadH1)") (class "Default")
      (node (ref "U13") (pin "H1") (pinfunction "78_H1") (pintype "bidirectional"))
    )
    (net (code "415") (name "unconnected-(U13-79-PadH2)") (class "Default")
      (node (ref "U13") (pin "H2") (pinfunction "79_H2") (pintype "bidirectional"))
    )
    (net (code "416") (name "unconnected-(U13-80-PadH3)") (class "Default")
      (node (ref "U13") (pin "H3") (pinfunction "80_H3") (pintype "bidirectional"))
    )
    (net (code "417") (name "unconnected-(U13-82-PadH12)") (class "Default")
      (node (ref "U13") (pin "H12") (pinfunction "82_H12") (pintype "bidirectional"))
    )
    (net (code "418") (name "unconnected-(U13-83-PadH13)") (class "Default")
      (node (ref "U13") (pin "H13") (pinfunction "83_H13") (pintype "bidirectional"))
    )
    (net (code "419") (name "unconnected-(U13-84-PadH14)") (class "Default")
      (node (ref "U13") (pin "H14") (pinfunction "84_H14") (pintype "bidirectional"))
    )
    (net (code "420") (name "unconnected-(U13-85-PadH5)") (class "Default")
      (node (ref "U13") (pin "H5") (pinfunction "85_H5") (pintype "bidirectional"))
    )
    (net (code "421") (name "unconnected-(U13-86-PadJ1)") (class "Default")
      (node (ref "U13") (pin "J1") (pinfunction "86_J1") (pintype "bidirectional"))
    )
    (net (code "422") (name "unconnected-(U13-87-PadJ2)") (class "Default")
      (node (ref "U13") (pin "J2") (pinfunction "87_J2") (pintype "bidirectional"))
    )
    (net (code "423") (name "unconnected-(U13-88-PadJ3)") (class "Default")
      (node (ref "U13") (pin "J3") (pinfunction "88_J3") (pintype "bidirectional"))
    )
    (net (code "424") (name "unconnected-(U13-89-PadJ5)") (class "Default")
      (node (ref "U13") (pin "J5") (pinfunction "89_J5") (pintype "bidirectional"))
    )
    (net (code "425") (name "unconnected-(U13-90-PadJ13)") (class "Default")
      (node (ref "U13") (pin "J13") (pinfunction "90_J13") (pintype "bidirectional"))
    )
    (net (code "426") (name "unconnected-(U13-91-PadJ14)") (class "Default")
      (node (ref "U13") (pin "J14") (pinfunction "91_J14") (pintype "bidirectional"))
    )
    (net (code "427") (name "unconnected-(U13-92-PadK1)") (class "Default")
      (node (ref "U13") (pin "K1") (pinfunction "92_K1") (pintype "bidirectional"))
    )
    (net (code "428") (name "unconnected-(U13-93-PadK2)") (class "Default")
      (node (ref "U13") (pin "K2") (pinfunction "93_K2") (pintype "bidirectional"))
    )
    (net (code "429") (name "unconnected-(U13-94-PadK3)") (class "Default")
      (node (ref "U13") (pin "K3") (pinfunction "94_K3") (pintype "bidirectional"))
    )
    (net (code "430") (name "unconnected-(U13-95-PadK7)") (class "Default")
      (node (ref "U13") (pin "K7") (pinfunction "95_K7") (pintype "bidirectional"))
    )
    (net (code "431") (name "unconnected-(U13-98-PadK10)") (class "Default")
      (node (ref "U13") (pin "K10") (pinfunction "98_K10") (pintype "bidirectional"))
    )
    (net (code "432") (name "unconnected-(U13-99-PadK12)") (class "Default")
      (node (ref "U13") (pin "K12") (pinfunction "99_K12") (pintype "bidirectional"))
    )
    (net (code "433") (name "unconnected-(U13-100-PadK13)") (class "Default")
      (node (ref "U13") (pin "K13") (pinfunction "100_K13") (pintype "bidirectional"))
    )
    (net (code "434") (name "unconnected-(U13-101-PadK14)") (class "Default")
      (node (ref "U13") (pin "K14") (pinfunction "101_K14") (pintype "bidirectional"))
    )
    (net (code "435") (name "unconnected-(U13-102-PadL1)") (class "Default")
      (node (ref "U13") (pin "L1") (pinfunction "102_L1") (pintype "bidirectional"))
    )
    (net (code "436") (name "unconnected-(U13-103-PadL2)") (class "Default")
      (node (ref "U13") (pin "L2") (pinfunction "103_L2") (pintype "bidirectional"))
    )
    (net (code "437") (name "unconnected-(U13-104-PadL3)") (class "Default")
      (node (ref "U13") (pin "L3") (pinfunction "104_L3") (pintype "bidirectional"))
    )
    (net (code "438") (name "unconnected-(U13-105-PadL12)") (class "Default")
      (node (ref "U13") (pin "L12") (pinfunction "105_L12") (pintype "bidirectional"))
    )
    (net (code "439") (name "unconnected-(U13-106-PadL13)") (class "Default")
      (node (ref "U13") (pin "L13") (pinfunction "106_L13") (pintype "bidirectional"))
    )
    (net (code "440") (name "unconnected-(U13-107-PadL14)") (class "Default")
      (node (ref "U13") (pin "L14") (pinfunction "107_L14") (pintype "bidirectional"))
    )
    (net (code "441") (name "unconnected-(U13-108-PadM1)") (class "Default")
      (node (ref "U13") (pin "M1") (pinfunction "108_M1") (pintype "bidirectional"))
    )
    (net (code "442") (name "unconnected-(U13-109-PadM2)") (class "Default")
      (node (ref "U13") (pin "M2") (pinfunction "109_M2") (pintype "bidirectional"))
    )
    (net (code "443") (name "unconnected-(U13-110-PadM3)") (class "Default")
      (node (ref "U13") (pin "M3") (pinfunction "110_M3") (pintype "bidirectional"))
    )
    (net (code "444") (name "unconnected-(U13-114-PadM7)") (class "Default")
      (node (ref "U13") (pin "M7") (pinfunction "114_M7") (pintype "bidirectional"))
    )
    (net (code "445") (name "unconnected-(U13-115-PadM8)") (class "Default")
      (node (ref "U13") (pin "M8") (pinfunction "115_M8") (pintype "bidirectional"))
    )
    (net (code "446") (name "unconnected-(U13-116-PadM9)") (class "Default")
      (node (ref "U13") (pin "M9") (pinfunction "116_M9") (pintype "bidirectional"))
    )
    (net (code "447") (name "unconnected-(U13-117-PadM10)") (class "Default")
      (node (ref "U13") (pin "M10") (pinfunction "117_M10") (pintype "bidirectional"))
    )
    (net (code "448") (name "unconnected-(U13-118-PadM11)") (class "Default")
      (node (ref "U13") (pin "M11") (pinfunction "118_M11") (pintype "bidirectional"))
    )
    (net (code "449") (name "unconnected-(U13-119-PadM12)") (class "Default")
      (node (ref "U13") (pin "M12") (pinfunction "119_M12") (pintype "bidirectional"))
    )
    (net (code "450") (name "unconnected-(U13-120-PadM13)") (class "Default")
      (node (ref "U13") (pin "M13") (pinfunction "120_M13") (pintype "bidirectional"))
    )
    (net (code "451") (name "unconnected-(U13-121-PadM14)") (class "Default")
      (node (ref "U13") (pin "M14") (pinfunction "121_M14") (pintype "bidirectional"))
    )
    (net (code "452") (name "unconnected-(U13-122-PadN1)") (class "Default")
      (node (ref "U13") (pin "N1") (pinfunction "122_N1") (pintype "bidirectional"))
    )
    (net (code "453") (name "unconnected-(U13-124-PadN3)") (class "Default")
      (node (ref "U13") (pin "N3") (pinfunction "124_N3") (pintype "bidirectional"))
    )
    (net (code "454") (name "unconnected-(U13-126-PadJ12)") (class "Default")
      (node (ref "U13") (pin "J12") (pinfunction "126_J12") (pintype "bidirectional"))
    )
    (net (code "455") (name "unconnected-(U13-127-PadN7)") (class "Default")
      (node (ref "U13") (pin "N7") (pinfunction "127_N7") (pintype "bidirectional"))
    )
    (net (code "456") (name "unconnected-(U13-128-PadN8)") (class "Default")
      (node (ref "U13") (pin "N8") (pinfunction "128_N8") (pintype "bidirectional"))
    )
    (net (code "457") (name "unconnected-(U13-129-PadN9)") (class "Default")
      (node (ref "U13") (pin "N9") (pinfunction "129_N9") (pintype "bidirectional"))
    )
    (net (code "458") (name "unconnected-(U13-130-PadN10)") (class "Default")
      (node (ref "U13") (pin "N10") (pinfunction "130_N10") (pintype "bidirectional"))
    )
    (net (code "459") (name "unconnected-(U13-131-PadN11)") (class "Default")
      (node (ref "U13") (pin "N11") (pinfunction "131_N11") (pintype "bidirectional"))
    )
    (net (code "460") (name "unconnected-(U13-132-PadN12)") (class "Default")
      (node (ref "U13") (pin "N12") (pinfunction "132_N12") (pintype "bidirectional"))
    )
    (net (code "461") (name "unconnected-(U13-133-PadN13)") (class "Default")
      (node (ref "U13") (pin "N13") (pinfunction "133_N13") (pintype "bidirectional"))
    )
    (net (code "462") (name "unconnected-(U13-134-PadN14)") (class "Default")
      (node (ref "U13") (pin "N14") (pinfunction "134_N14") (pintype "bidirectional"))
    )
    (net (code "463") (name "unconnected-(U13-135-PadP1)") (class "Default")
      (node (ref "U13") (pin "P1") (pinfunction "135_P1") (pintype "bidirectional"))
    )
    (net (code "464") (name "unconnected-(U13-136-PadP2)") (class "Default")
      (node (ref "U13") (pin "P2") (pinfunction "136_P2") (pintype "bidirectional"))
    )
    (net (code "465") (name "unconnected-(U13-141-PadP7)") (class "Default")
      (node (ref "U13") (pin "P7") (pinfunction "141_P7") (pintype "bidirectional"))
    )
    (net (code "466") (name "unconnected-(U13-142-PadP8)") (class "Default")
      (node (ref "U13") (pin "P8") (pinfunction "142_P8") (pintype "bidirectional"))
    )
    (net (code "467") (name "unconnected-(U13-143-PadP9)") (class "Default")
      (node (ref "U13") (pin "P9") (pinfunction "143_P9") (pintype "bidirectional"))
    )
    (net (code "468") (name "unconnected-(U13-144-PadP10)") (class "Default")
      (node (ref "U13") (pin "P10") (pinfunction "144_P10") (pintype "bidirectional"))
    )
    (net (code "469") (name "unconnected-(U13-145-PadP11)") (class "Default")
      (node (ref "U13") (pin "P11") (pinfunction "145_P11") (pintype "bidirectional"))
    )
    (net (code "470") (name "unconnected-(U13-146-PadP12)") (class "Default")
      (node (ref "U13") (pin "P12") (pinfunction "146_P12") (pintype "bidirectional"))
    )
    (net (code "471") (name "unconnected-(U13-147-PadP13)") (class "Default")
      (node (ref "U13") (pin "P13") (pinfunction "147_P13") (pintype "bidirectional"))
    )
    (net (code "472") (name "unconnected-(U13-148-PadP14)") (class "Default")
      (node (ref "U13") (pin "P14") (pinfunction "148_P14") (pintype "bidirectional"))
    )
    (net (code "473") (name "unconnected-(U13-151-PadE5)") (class "Default")
      (node (ref "U13") (pin "E5") (pinfunction "151_E5") (pintype "bidirectional"))
    )
    (net (code "474") (name "unconnected-(U13-152-PadN6)") (class "Default")
      (node (ref "U13") (pin "N6") (pinfunction "152_N6") (pintype "bidirectional"))
    )
    (net (code "475") (name "unconnected-(U13-153-PadK6)") (class "Default")
      (node (ref "U13") (pin "K6") (pinfunction "153_K6") (pintype "bidirectional"))
    )
    (net (code "476") (name "unconnected-(Y1-4-Pad2)") (class "Default")
      (node (ref "Y1") (pin "2") (pinfunction "4_2") (pintype "bidirectional"))
    )
    (net (code "477") (name "unconnected-(Y1-Pad3)") (class "Default")
      (node (ref "Y1") (pin "3") (pinfunction "3_3") (pintype "bidirectional"))
    )
  )
)
